# QuDAC_V3.net
KiCad netlist of a schematic drawn in EAGLE
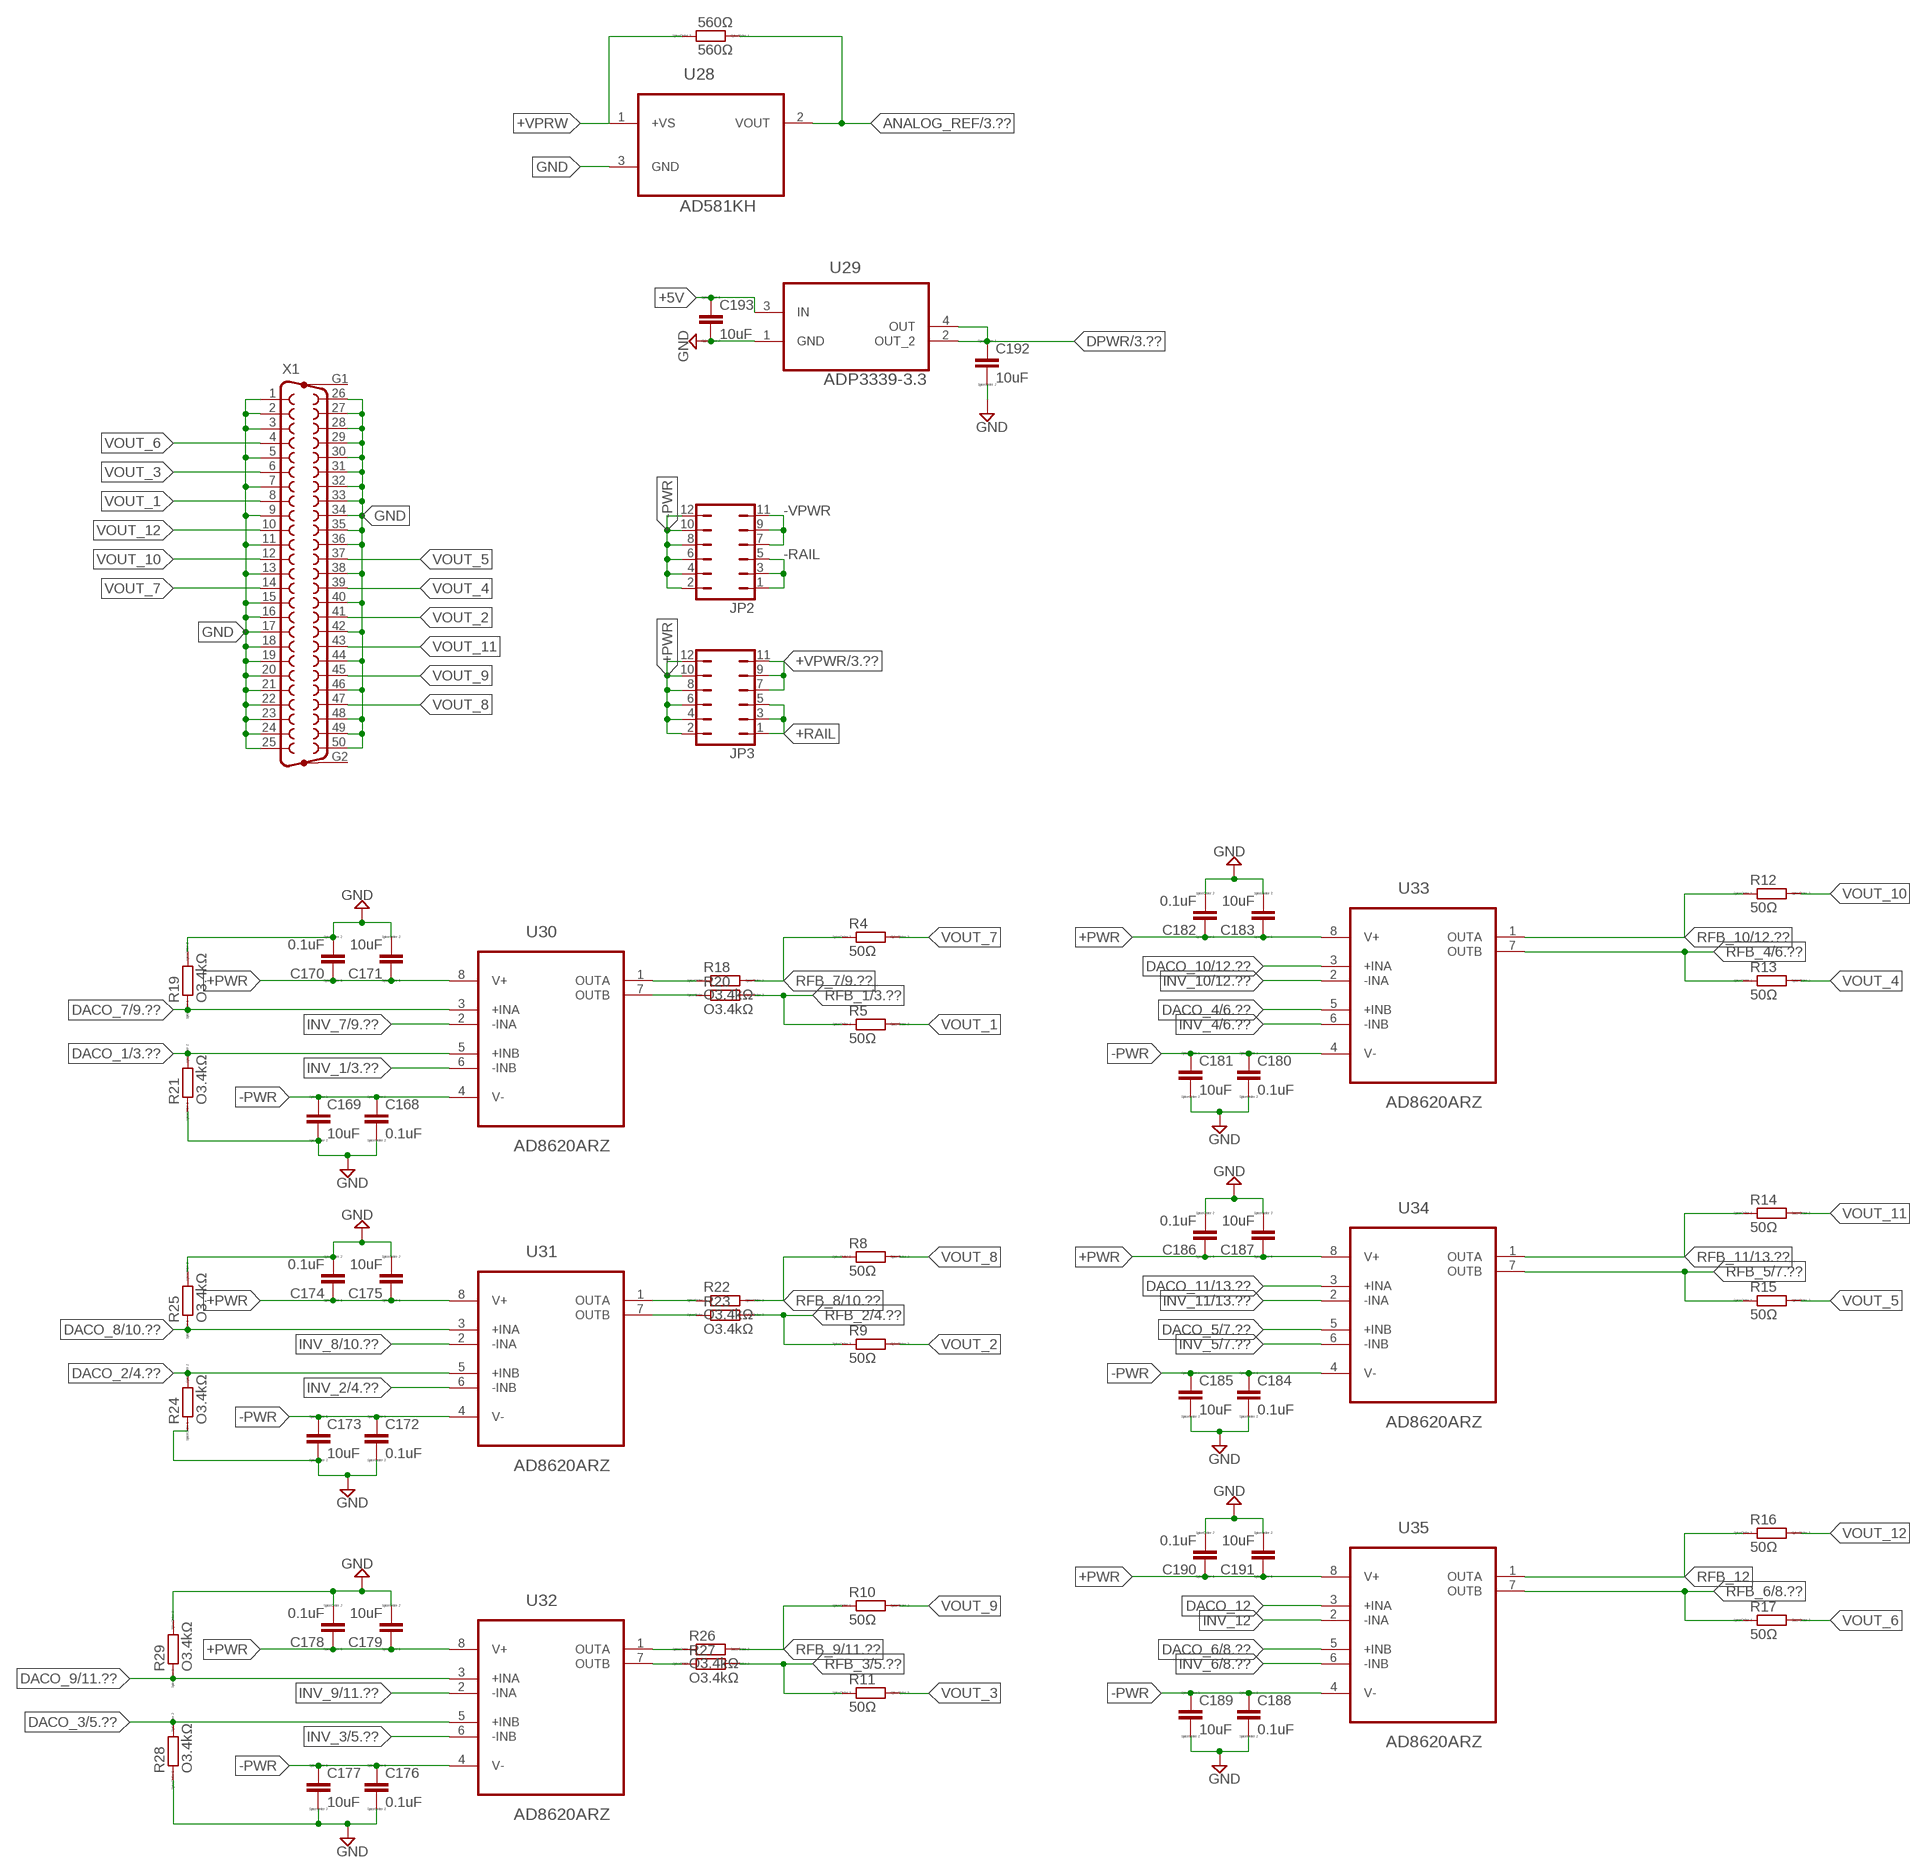
[diagram p0: schematic, sheet 1]
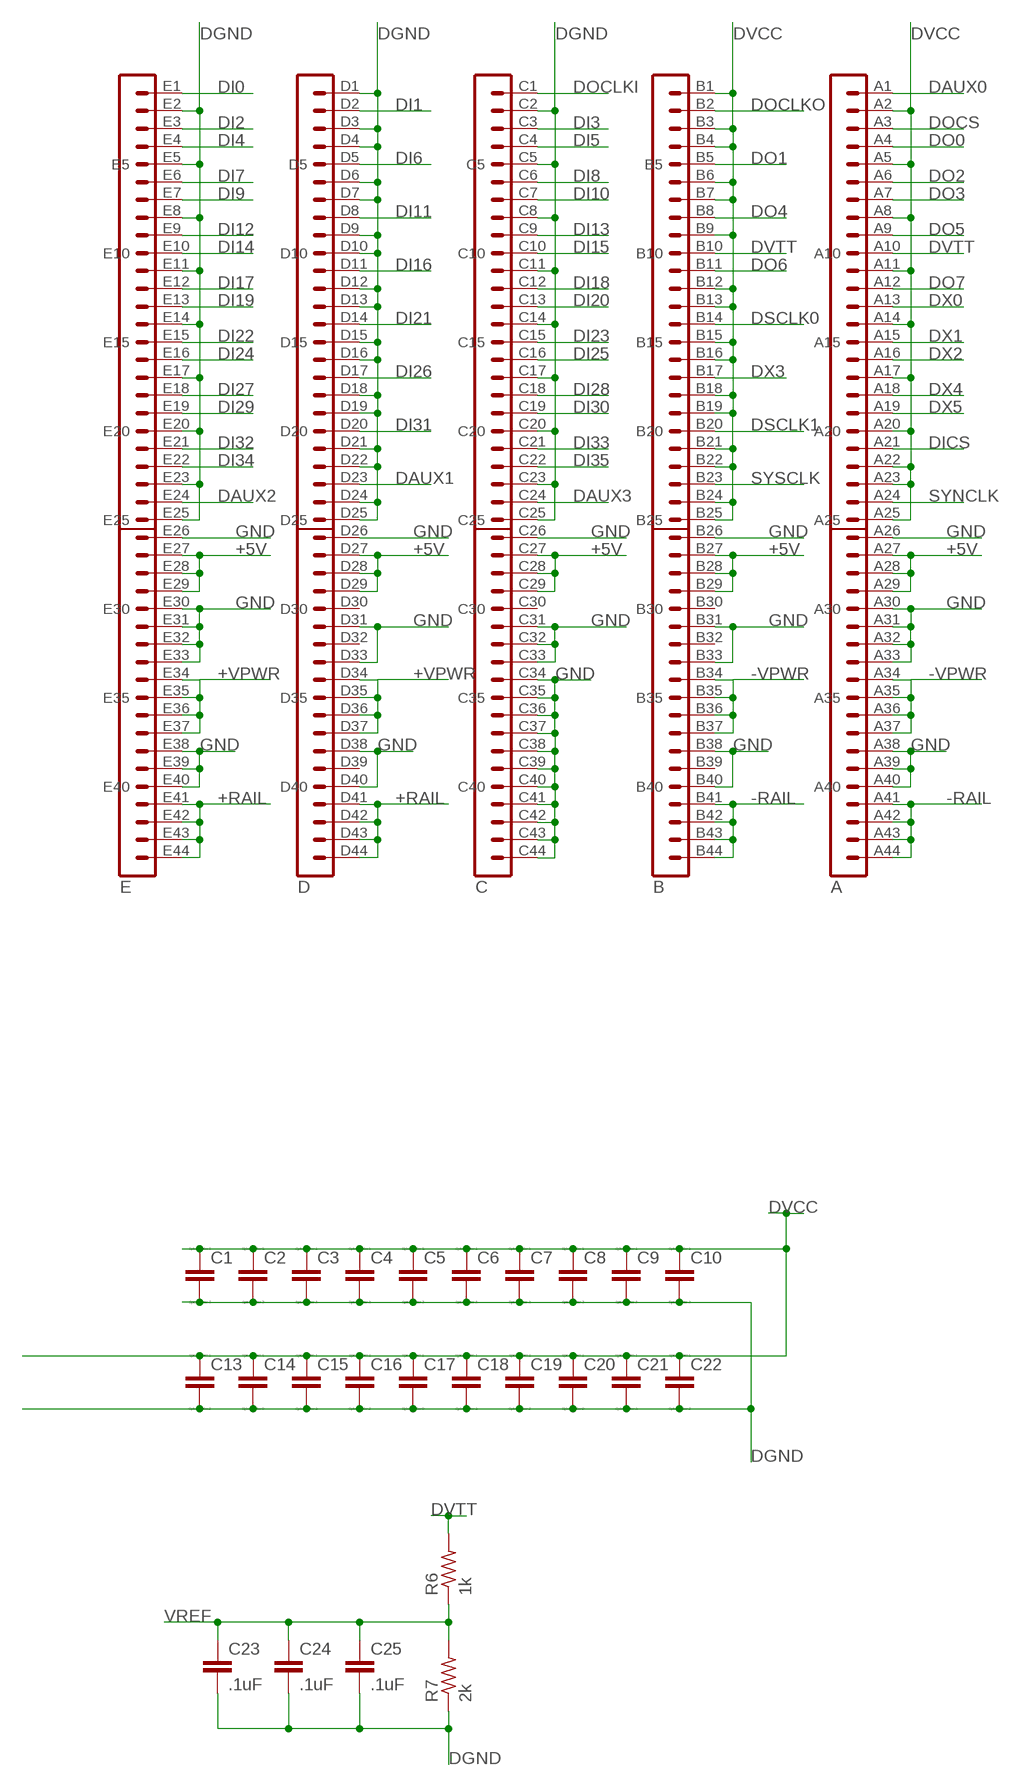
[diagram p1: schematic, sheet 2, part 1 of 2]
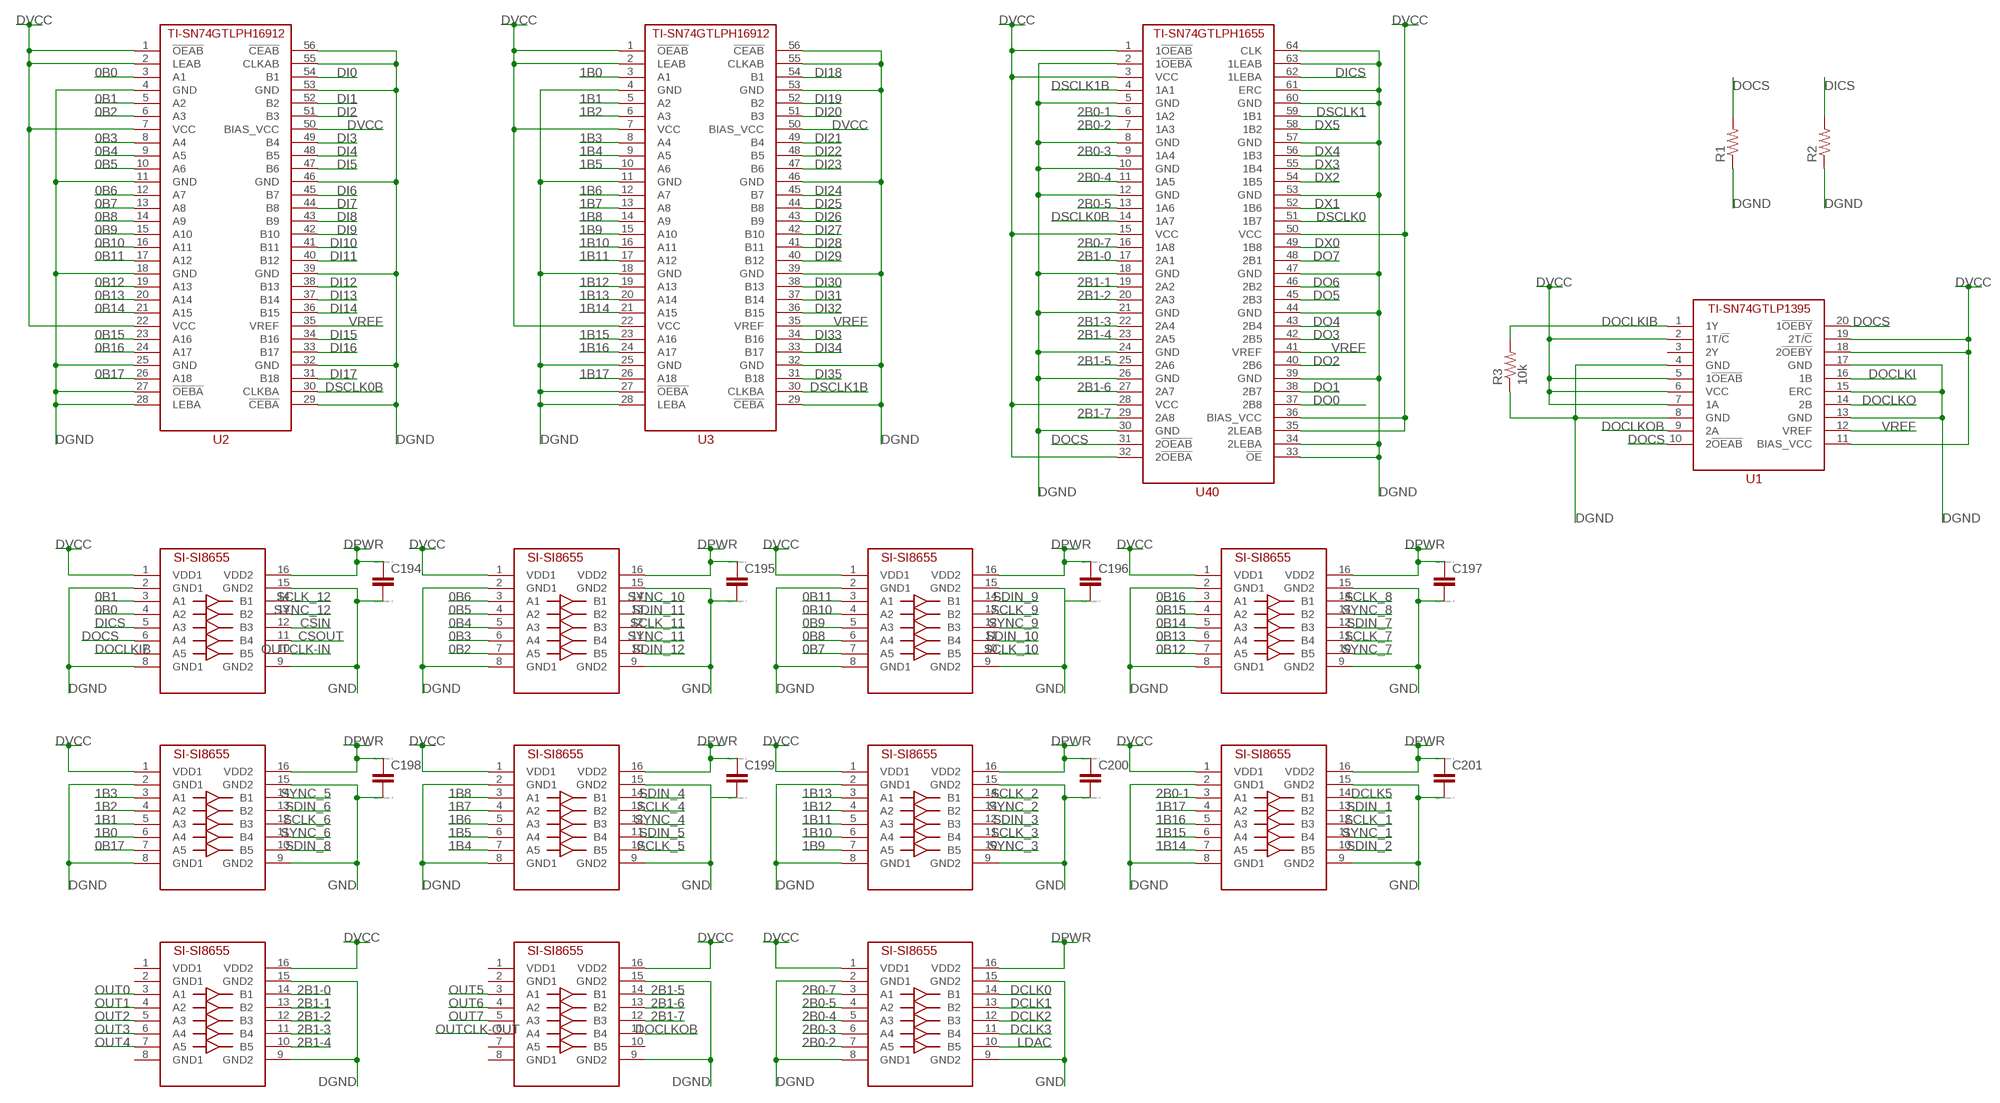
[diagram p2: schematic, sheet 2, part 2 of 2]
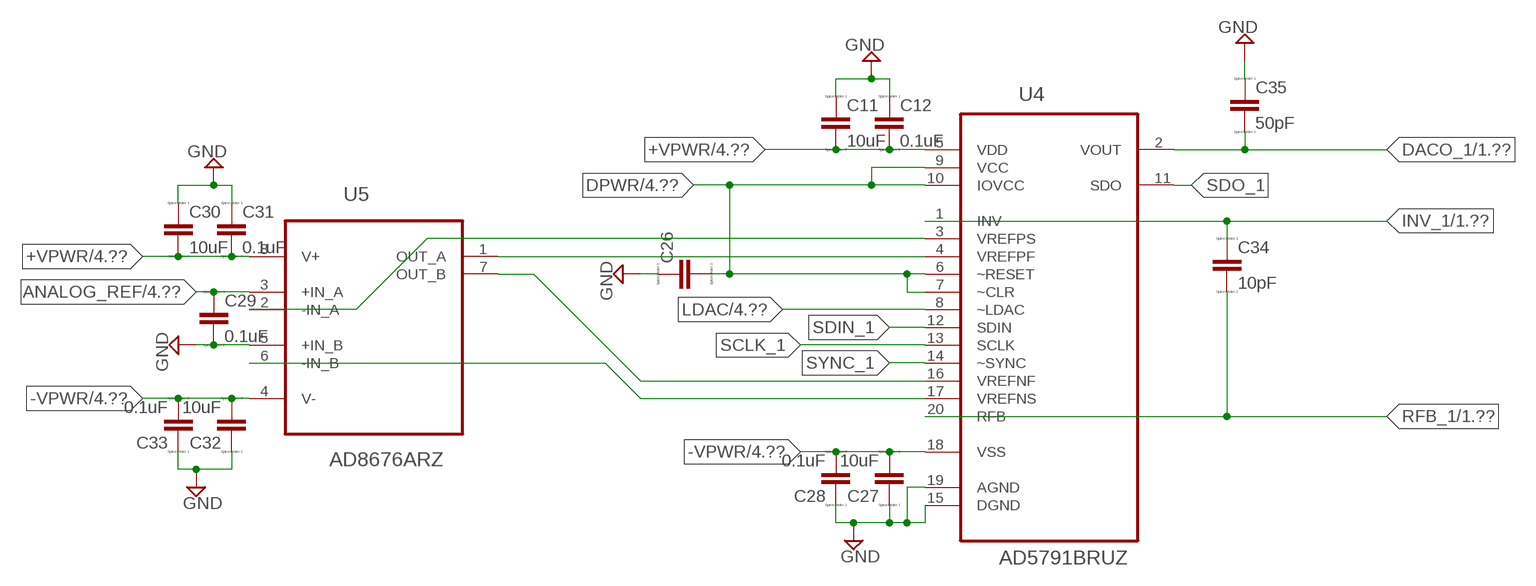
[diagram p3: schematic, sheet 3]
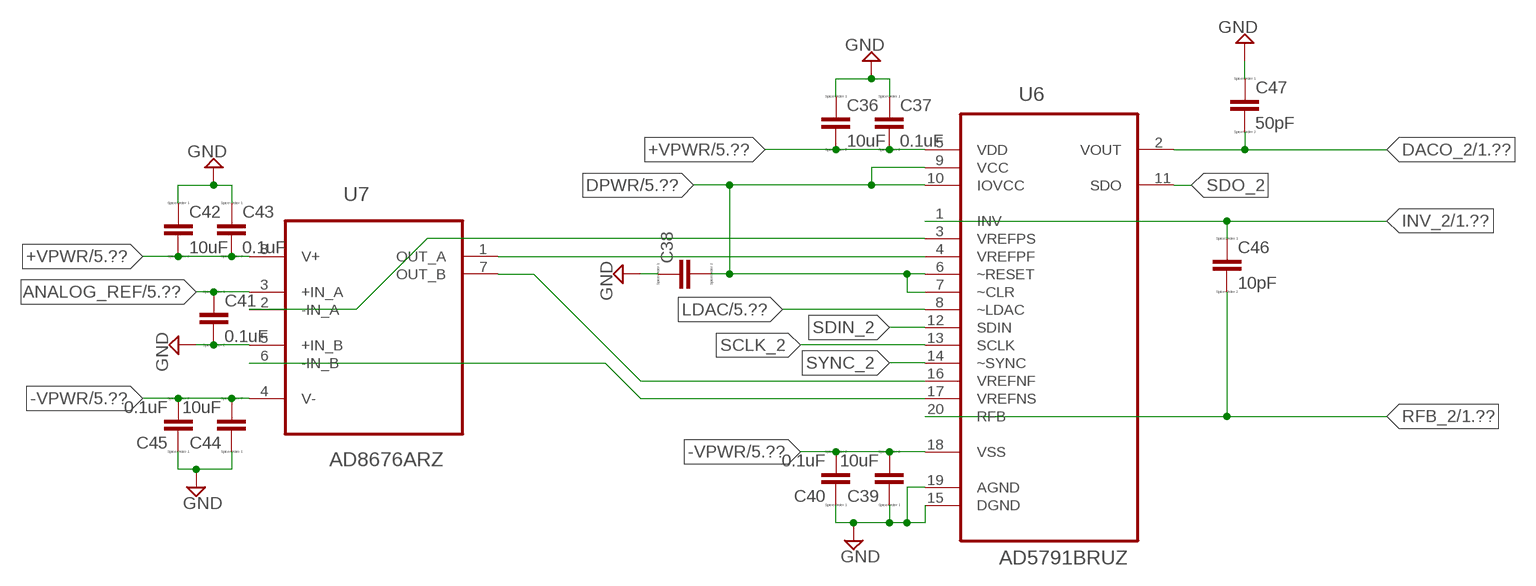
[diagram p4: schematic, sheet 4]
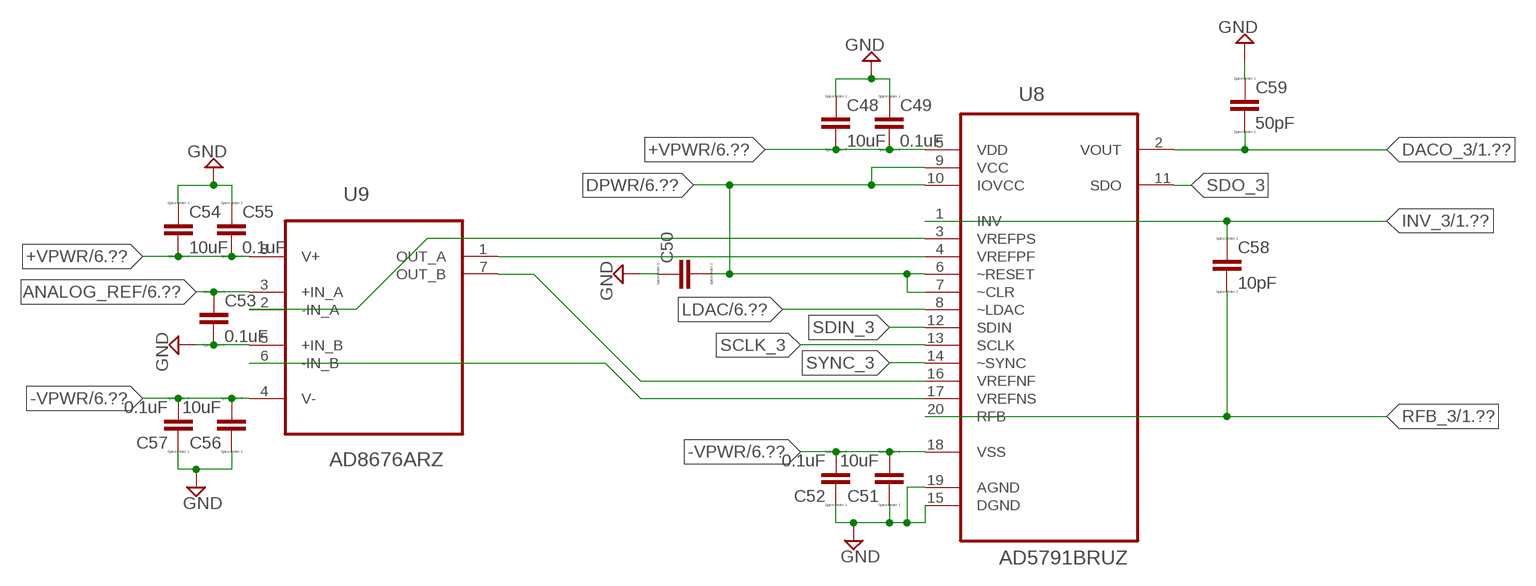
[diagram p5: schematic, sheet 5]
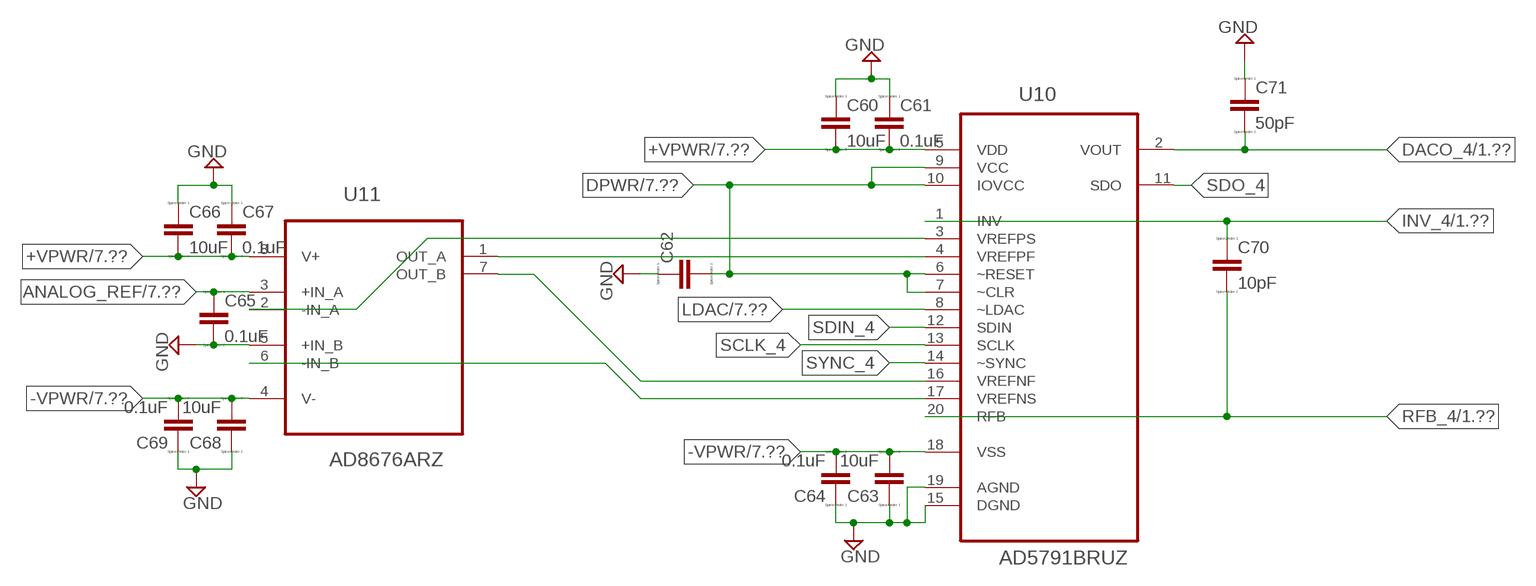
[diagram p6: schematic, sheet 6]
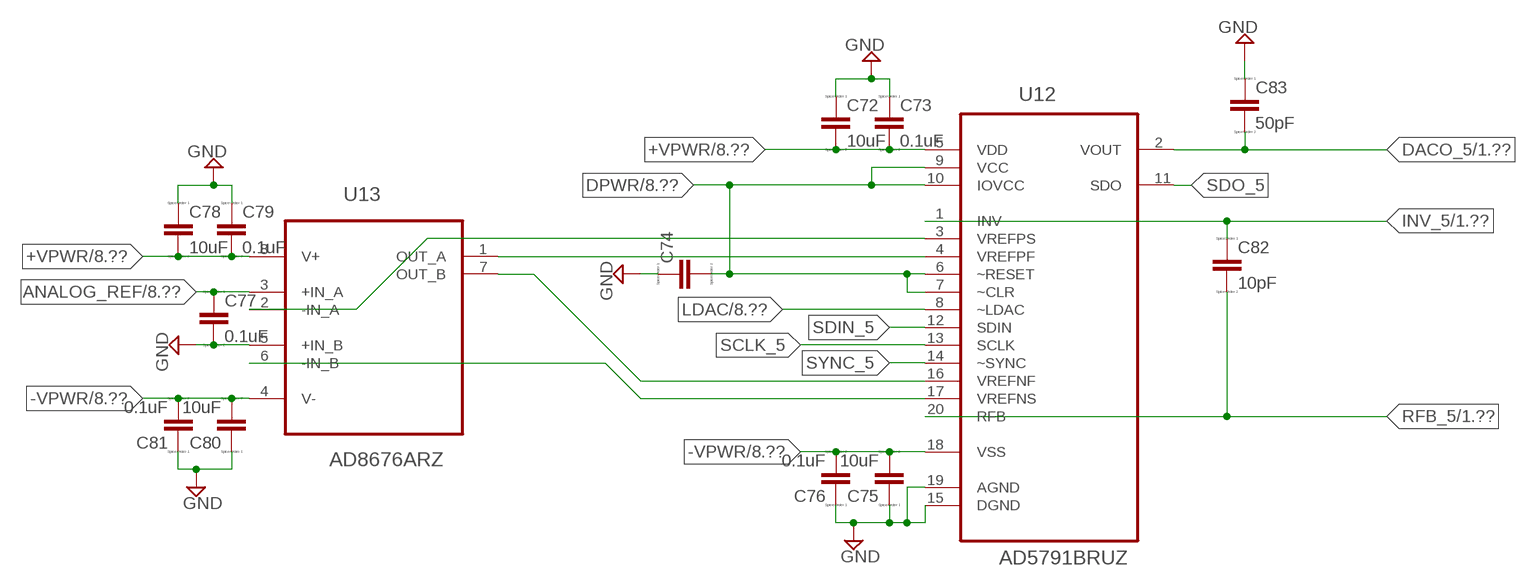
[diagram p7: schematic, sheet 7]
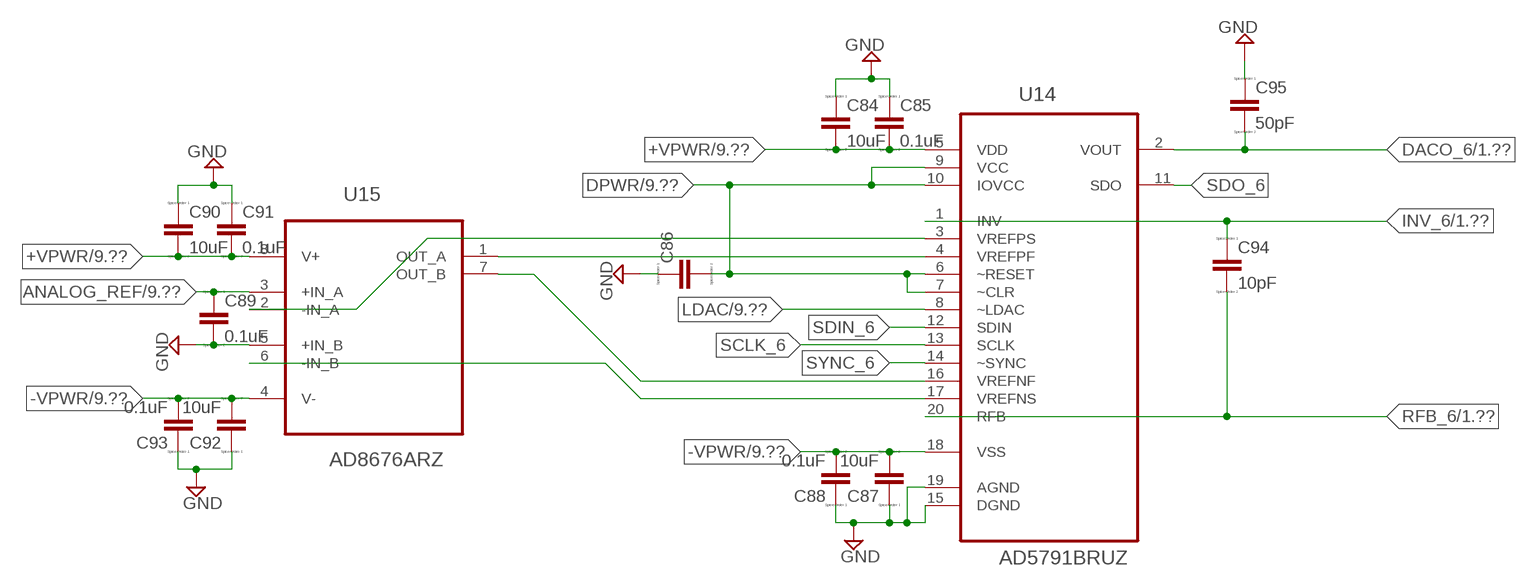
[diagram p8: schematic, sheet 8]
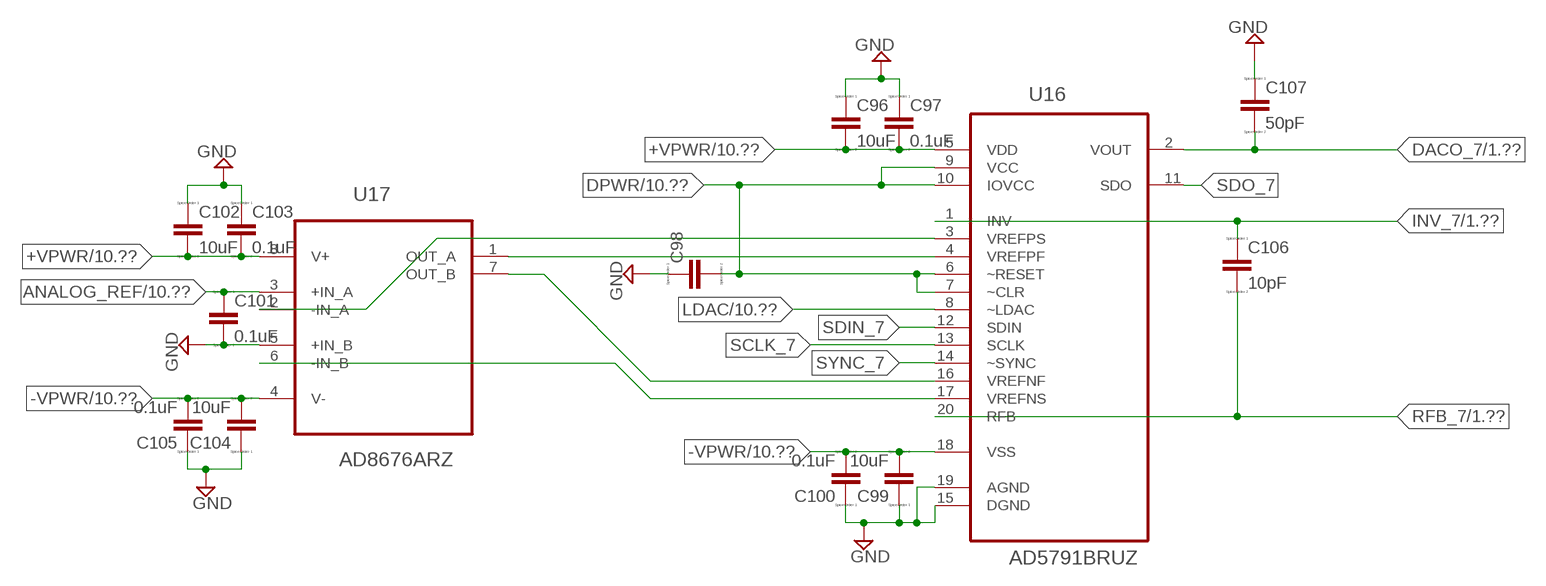
[diagram p9: schematic, sheet 9]
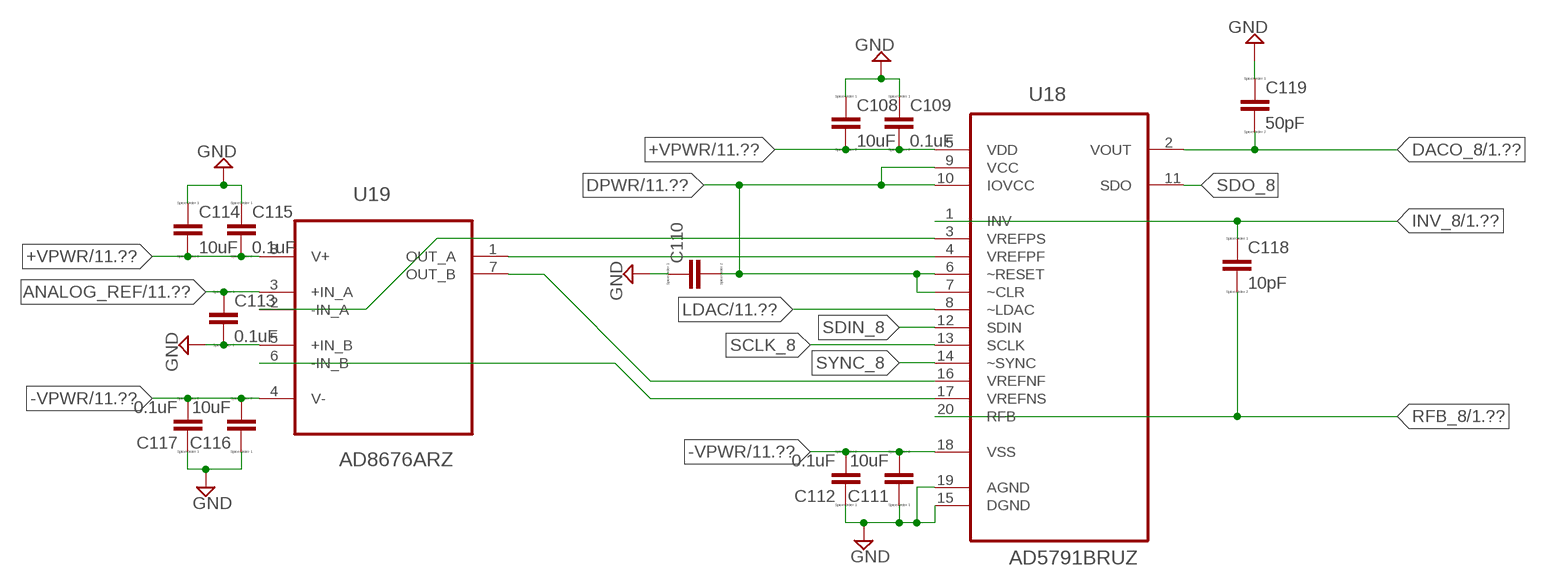
[diagram p10: schematic, sheet 10]
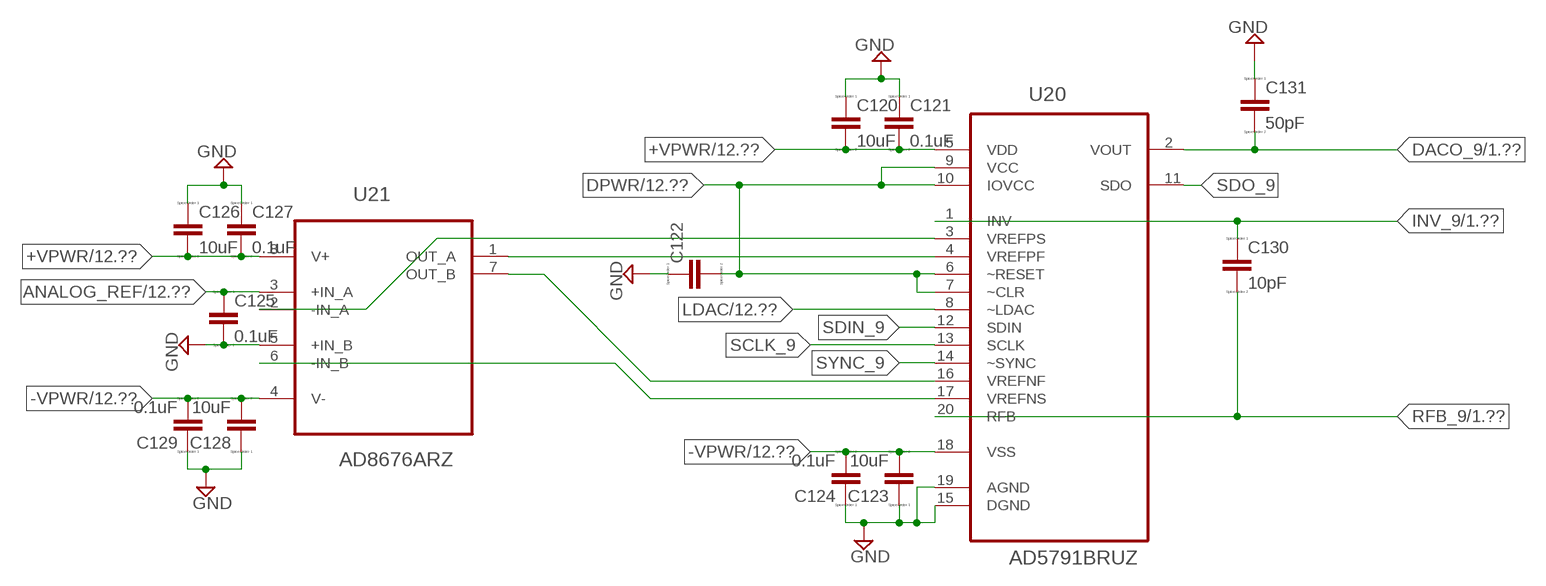
[diagram p11: schematic, sheet 11]
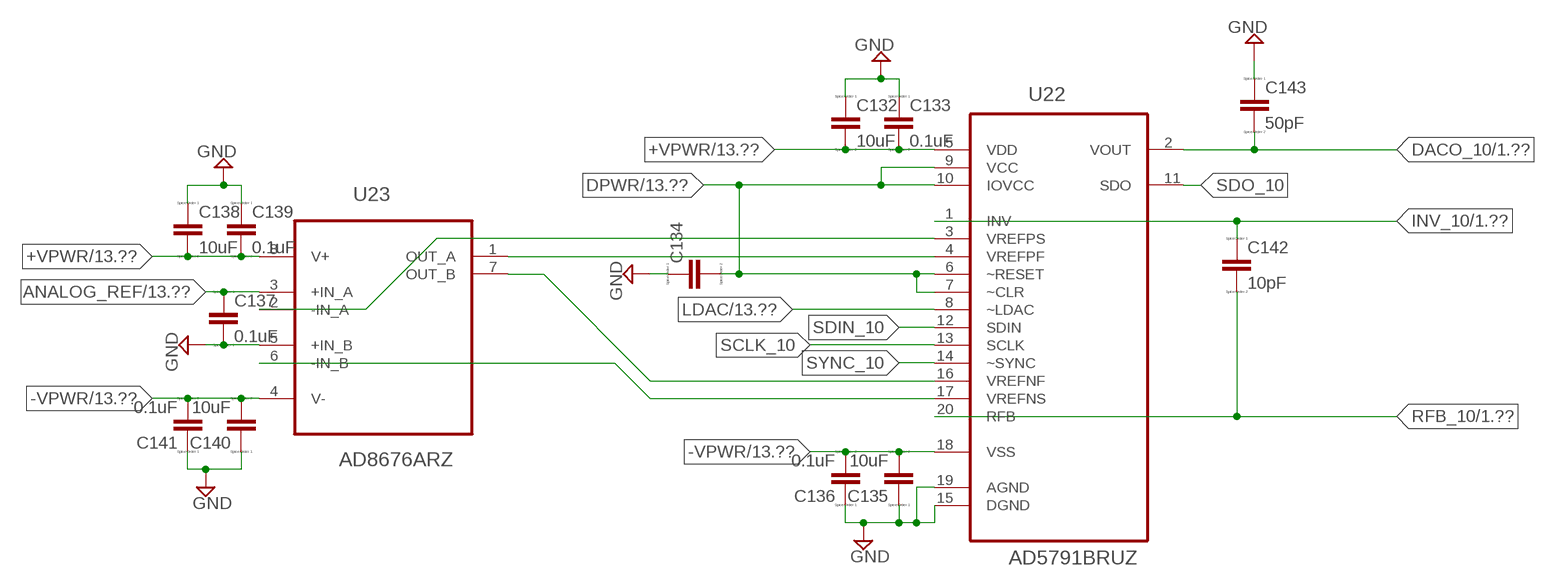
[diagram p12: schematic, sheet 12]
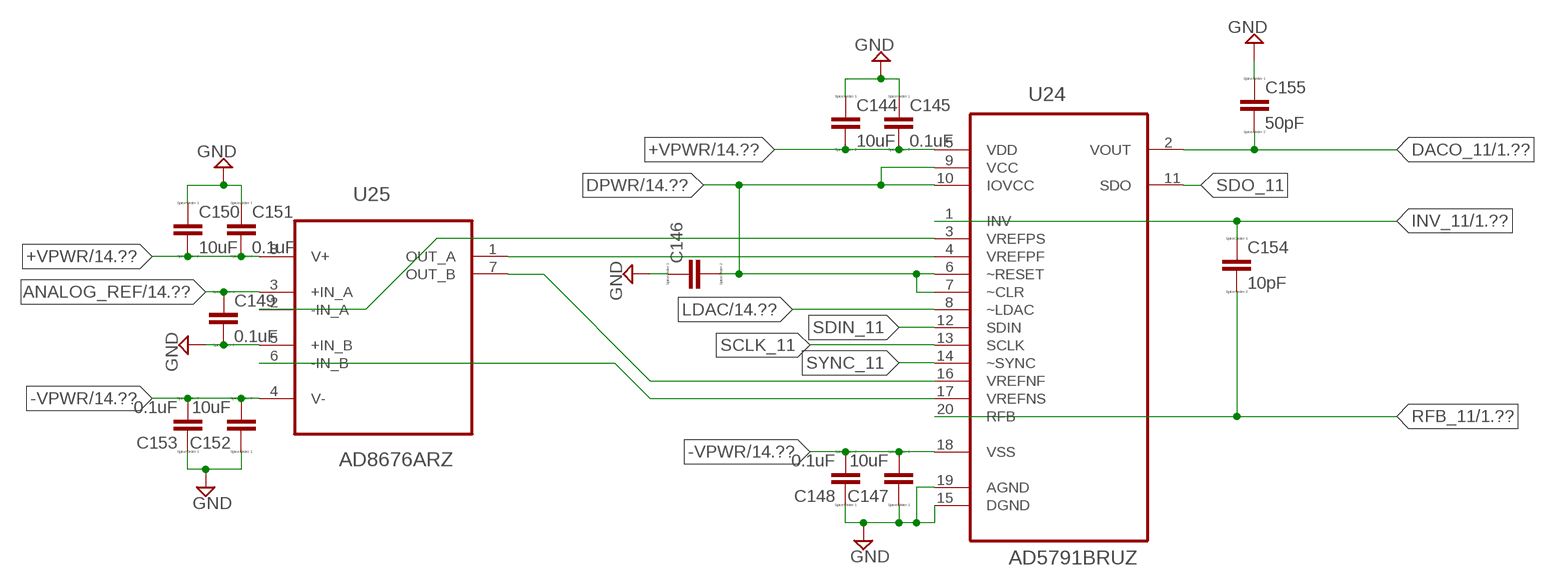
[diagram p13: schematic, sheet 13]
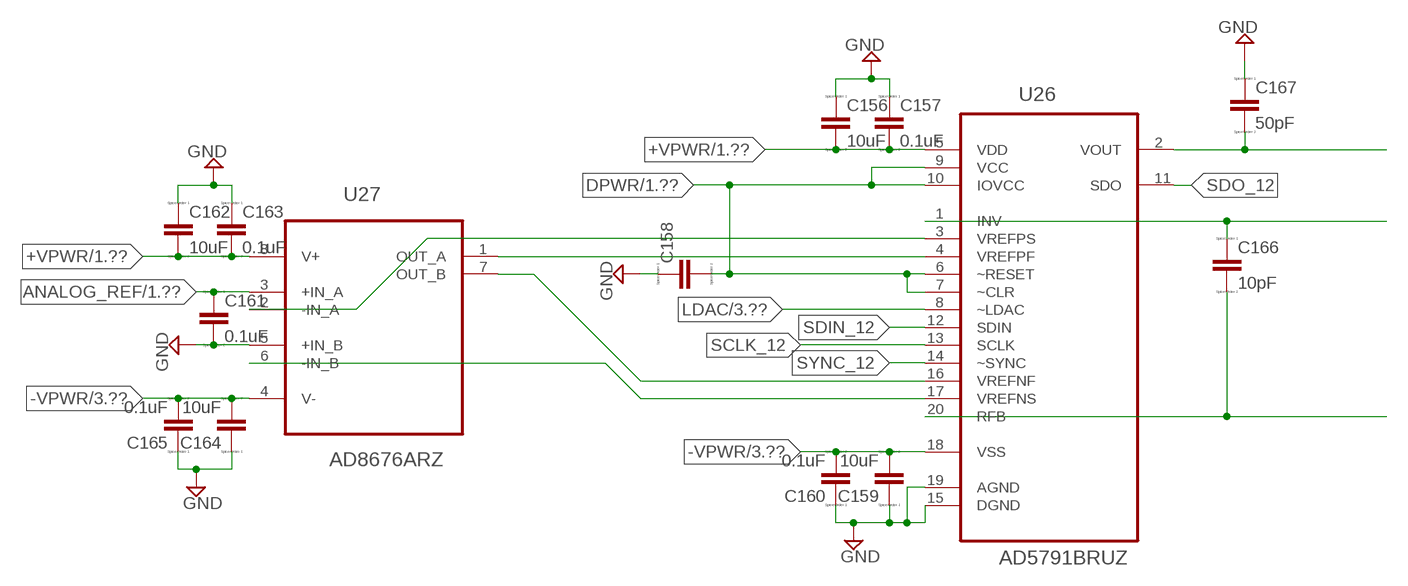
[diagram p14: schematic, sheet 14]

(export (version "E")
  (design (tool "Eeschema 10.0.6"))
  (components
    (comp (ref "560Ω")
      (value "560Ω")
      (footprint "eagle-import:R0603")
      (libsource (lib "eagle-import") (part "RR0603"))
    )
    (comp (ref "C168")
      (value "0.1uF")
      (footprint "eagle-import:C0603")
      (libsource (lib "eagle-import") (part "CC0603"))
    )
    (comp (ref "C169")
      (value "10uF")
      (footprint "eagle-import:C0805")
      (libsource (lib "eagle-import") (part "C"))
    )
    (comp (ref "C170")
      (value "0.1uF")
      (footprint "eagle-import:C0603")
      (libsource (lib "eagle-import") (part "CC0603"))
    )
    (comp (ref "C171")
      (value "10uF")
      (footprint "eagle-import:C0805")
      (libsource (lib "eagle-import") (part "C"))
    )
    (comp (ref "C172")
      (value "0.1uF")
      (footprint "eagle-import:C0603")
      (libsource (lib "eagle-import") (part "CC0603"))
    )
    (comp (ref "C173")
      (value "10uF")
      (footprint "eagle-import:C0805")
      (libsource (lib "eagle-import") (part "C"))
    )
    (comp (ref "C174")
      (value "0.1uF")
      (footprint "eagle-import:C0603")
      (libsource (lib "eagle-import") (part "CC0603"))
    )
    (comp (ref "C175")
      (value "10uF")
      (footprint "eagle-import:C0805")
      (libsource (lib "eagle-import") (part "C"))
    )
    (comp (ref "C176")
      (value "0.1uF")
      (footprint "eagle-import:C0603")
      (libsource (lib "eagle-import") (part "CC0603"))
    )
    (comp (ref "C177")
      (value "10uF")
      (footprint "eagle-import:C0805")
      (libsource (lib "eagle-import") (part "C"))
    )
    (comp (ref "C178")
      (value "0.1uF")
      (footprint "eagle-import:C0603")
      (libsource (lib "eagle-import") (part "CC0603"))
    )
    (comp (ref "C179")
      (value "10uF")
      (footprint "eagle-import:C0805")
      (libsource (lib "eagle-import") (part "C"))
    )
    (comp (ref "C180")
      (value "0.1uF")
      (footprint "eagle-import:C0603")
      (libsource (lib "eagle-import") (part "CC0603"))
    )
    (comp (ref "C181")
      (value "10uF")
      (footprint "eagle-import:C0805")
      (libsource (lib "eagle-import") (part "C"))
    )
    (comp (ref "C182")
      (value "0.1uF")
      (footprint "eagle-import:C0603")
      (libsource (lib "eagle-import") (part "CC0603"))
    )
    (comp (ref "C183")
      (value "10uF")
      (footprint "eagle-import:C0805")
      (libsource (lib "eagle-import") (part "C"))
    )
    (comp (ref "C184")
      (value "0.1uF")
      (footprint "eagle-import:C0603")
      (libsource (lib "eagle-import") (part "CC0603"))
    )
    (comp (ref "C185")
      (value "10uF")
      (footprint "eagle-import:C0805")
      (libsource (lib "eagle-import") (part "C"))
    )
    (comp (ref "C186")
      (value "0.1uF")
      (footprint "eagle-import:C0603")
      (libsource (lib "eagle-import") (part "CC0603"))
    )
    (comp (ref "C187")
      (value "10uF")
      (footprint "eagle-import:C0805")
      (libsource (lib "eagle-import") (part "C"))
    )
    (comp (ref "C188")
      (value "0.1uF")
      (footprint "eagle-import:C0603")
      (libsource (lib "eagle-import") (part "CC0603"))
    )
    (comp (ref "C189")
      (value "10uF")
      (footprint "eagle-import:C0805")
      (libsource (lib "eagle-import") (part "C"))
    )
    (comp (ref "C190")
      (value "0.1uF")
      (footprint "eagle-import:C0603")
      (libsource (lib "eagle-import") (part "CC0603"))
    )
    (comp (ref "C191")
      (value "10uF")
      (footprint "eagle-import:C0805")
      (libsource (lib "eagle-import") (part "C"))
    )
    (comp (ref "C192")
      (value "10uF")
      (footprint "eagle-import:C0805")
      (libsource (lib "eagle-import") (part "C"))
    )
    (comp (ref "C193")
      (value "10uF")
      (footprint "eagle-import:C0805")
      (libsource (lib "eagle-import") (part "C"))
    )
    (comp (ref "JP2")
      (value "JP6Q")
      (footprint "eagle-import:JP6Q")
      (libsource (lib "eagle-import") (part "JP6Q"))
    )
    (comp (ref "JP3")
      (value "JP6Q")
      (footprint "eagle-import:JP6Q")
      (libsource (lib "eagle-import") (part "JP6Q"))
    )
    (comp (ref "R4")
      (value "50Ω")
      (footprint "eagle-import:R0603")
      (libsource (lib "eagle-import") (part "RR0603"))
    )
    (comp (ref "R5")
      (value "50Ω")
      (footprint "eagle-import:R0603")
      (libsource (lib "eagle-import") (part "RR0603"))
    )
    (comp (ref "R8")
      (value "50Ω")
      (footprint "eagle-import:R0603")
      (libsource (lib "eagle-import") (part "RR0603"))
    )
    (comp (ref "R9")
      (value "50Ω")
      (footprint "eagle-import:R0603")
      (libsource (lib "eagle-import") (part "RR0603"))
    )
    (comp (ref "R10")
      (value "50Ω")
      (footprint "eagle-import:R0603")
      (libsource (lib "eagle-import") (part "RR0603"))
    )
    (comp (ref "R11")
      (value "50Ω")
      (footprint "eagle-import:R0603")
      (libsource (lib "eagle-import") (part "RR0603"))
    )
    (comp (ref "R12")
      (value "50Ω")
      (footprint "eagle-import:R0603")
      (libsource (lib "eagle-import") (part "RR0603"))
    )
    (comp (ref "R13")
      (value "50Ω")
      (footprint "eagle-import:R0603")
      (libsource (lib "eagle-import") (part "RR0603"))
    )
    (comp (ref "R14")
      (value "50Ω")
      (footprint "eagle-import:R0603")
      (libsource (lib "eagle-import") (part "RR0603"))
    )
    (comp (ref "R15")
      (value "50Ω")
      (footprint "eagle-import:R0603")
      (libsource (lib "eagle-import") (part "RR0603"))
    )
    (comp (ref "R16")
      (value "50Ω")
      (footprint "eagle-import:R0603")
      (libsource (lib "eagle-import") (part "RR0603"))
    )
    (comp (ref "R17")
      (value "50Ω")
      (footprint "eagle-import:R0603")
      (libsource (lib "eagle-import") (part "RR0603"))
    )
    (comp (ref "R18")
      (value "O3.4kΩ")
      (footprint "eagle-import:R0603")
      (libsource (lib "eagle-import") (part "RR0603"))
    )
    (comp (ref "R19")
      (value "O3.4kΩ")
      (footprint "eagle-import:R0603")
      (libsource (lib "eagle-import") (part "RR0603"))
    )
    (comp (ref "R20")
      (value "O3.4kΩ")
      (footprint "eagle-import:R0603")
      (libsource (lib "eagle-import") (part "RR0603"))
    )
    (comp (ref "R21")
      (value "O3.4kΩ")
      (footprint "eagle-import:R0603")
      (libsource (lib "eagle-import") (part "RR0603"))
    )
    (comp (ref "R22")
      (value "O3.4kΩ")
      (footprint "eagle-import:R0603")
      (libsource (lib "eagle-import") (part "RR0603"))
    )
    (comp (ref "R23")
      (value "O3.4kΩ")
      (footprint "eagle-import:R0603")
      (libsource (lib "eagle-import") (part "RR0603"))
    )
    (comp (ref "R24")
      (value "O3.4kΩ")
      (footprint "eagle-import:R0603")
      (libsource (lib "eagle-import") (part "RR0603"))
    )
    (comp (ref "R25")
      (value "O3.4kΩ")
      (footprint "eagle-import:R0603")
      (libsource (lib "eagle-import") (part "RR0603"))
    )
    (comp (ref "R26")
      (value "O3.4kΩ")
      (footprint "eagle-import:R0603")
      (libsource (lib "eagle-import") (part "RR0603"))
    )
    (comp (ref "R27")
      (value "O3.4kΩ")
      (footprint "eagle-import:R0603")
      (libsource (lib "eagle-import") (part "RR0603"))
    )
    (comp (ref "R28")
      (value "O3.4kΩ")
      (footprint "eagle-import:R0603")
      (libsource (lib "eagle-import") (part "RR0603"))
    )
    (comp (ref "R29")
      (value "O3.4kΩ")
      (footprint "eagle-import:R0603")
      (libsource (lib "eagle-import") (part "RR0603"))
    )
    (comp (ref "U28")
      (value "AD581KH")
      (footprint "eagle-import:TO254P939X470-3P")
      (libsource (lib "eagle-import") (part "AD581KH"))
    )
    (comp (ref "U29")
      (value "ADP3339-3.3")
      (footprint "eagle-import:SOT230P700X180-4N")
      (fields (field (name "MPN") "ADP3339AKCZ-3.3-R7"))
      (libsource (lib "eagle-import") (part "ADP3339AKCZ-3.3-R7"))
    )
    (comp (ref "U30")
      (value "AD8620ARZ")
      (footprint "eagle-import:SOIC127P600X175-8N")
      (libsource (lib "eagle-import") (part "AD8620ARZ"))
    )
    (comp (ref "U31")
      (value "AD8620ARZ")
      (footprint "eagle-import:SOIC127P600X175-8N")
      (libsource (lib "eagle-import") (part "AD8620ARZ"))
    )
    (comp (ref "U32")
      (value "AD8620ARZ")
      (footprint "eagle-import:SOIC127P600X175-8N")
      (libsource (lib "eagle-import") (part "AD8620ARZ"))
    )
    (comp (ref "U33")
      (value "AD8620ARZ")
      (footprint "eagle-import:SOIC127P600X175-8N")
      (libsource (lib "eagle-import") (part "AD8620ARZ"))
    )
    (comp (ref "U34")
      (value "AD8620ARZ")
      (footprint "eagle-import:SOIC127P600X175-8N")
      (libsource (lib "eagle-import") (part "AD8620ARZ"))
    )
    (comp (ref "U35")
      (value "AD8620ARZ")
      (footprint "eagle-import:SOIC127P600X175-8N")
      (libsource (lib "eagle-import") (part "AD8620ARZ"))
    )
    (comp (ref "X1")
      (value "F50HP")
      (footprint "eagle-import:F50HP")
      (libsource (lib "eagle-import") (part "F50HP"))
    )
    (comp (ref "C96")
      (value "10uF")
      (footprint "eagle-import:C0805")
      (libsource (lib "eagle-import") (part "C"))
    )
    (comp (ref "C97")
      (value "0.1uF")
      (footprint "eagle-import:C0603")
      (libsource (lib "eagle-import") (part "CC0603"))
    )
    (comp (ref "C98")
      (value "CC0603")
      (footprint "eagle-import:C0603")
      (libsource (lib "eagle-import") (part "CC0603"))
    )
    (comp (ref "C99")
      (value "10uF")
      (footprint "eagle-import:C0805")
      (libsource (lib "eagle-import") (part "C"))
    )
    (comp (ref "C100")
      (value "0.1uF")
      (footprint "eagle-import:C0603")
      (libsource (lib "eagle-import") (part "CC0603"))
    )
    (comp (ref "C101")
      (value "0.1uF")
      (footprint "eagle-import:C0603")
      (libsource (lib "eagle-import") (part "CC0603"))
    )
    (comp (ref "C102")
      (value "10uF")
      (footprint "eagle-import:C0805")
      (libsource (lib "eagle-import") (part "C"))
    )
    (comp (ref "C103")
      (value "0.1uF")
      (footprint "eagle-import:C0603")
      (libsource (lib "eagle-import") (part "CC0603"))
    )
    (comp (ref "C104")
      (value "10uF")
      (footprint "eagle-import:C0805")
      (libsource (lib "eagle-import") (part "C"))
    )
    (comp (ref "C105")
      (value "0.1uF")
      (footprint "eagle-import:C0603")
      (libsource (lib "eagle-import") (part "CC0603"))
    )
    (comp (ref "C106")
      (value "10pF")
      (footprint "eagle-import:C0603")
      (libsource (lib "eagle-import") (part "CC0603"))
    )
    (comp (ref "C107")
      (value "50pF")
      (footprint "eagle-import:C0603")
      (libsource (lib "eagle-import") (part "CC0603"))
    )
    (comp (ref "U16")
      (value "AD5791BRUZ")
      (footprint "eagle-import:SOP65P640X120-20N")
      (libsource (lib "eagle-import") (part "AD5791BRUZ"))
    )
    (comp (ref "U17")
      (value "AD8676ARZ")
      (footprint "eagle-import:SOIC127P600X175-8N")
      (libsource (lib "eagle-import") (part "AD8676ARZ"))
    )
    (comp (ref "C60")
      (value "10uF")
      (footprint "eagle-import:C0805")
      (libsource (lib "eagle-import") (part "C"))
    )
    (comp (ref "C61")
      (value "0.1uF")
      (footprint "eagle-import:C0603")
      (libsource (lib "eagle-import") (part "CC0603"))
    )
    (comp (ref "C62")
      (value "CC0603")
      (footprint "eagle-import:C0603")
      (libsource (lib "eagle-import") (part "CC0603"))
    )
    (comp (ref "C63")
      (value "10uF")
      (footprint "eagle-import:C0805")
      (libsource (lib "eagle-import") (part "C"))
    )
    (comp (ref "C64")
      (value "0.1uF")
      (footprint "eagle-import:C0603")
      (libsource (lib "eagle-import") (part "CC0603"))
    )
    (comp (ref "C65")
      (value "0.1uF")
      (footprint "eagle-import:C0603")
      (libsource (lib "eagle-import") (part "CC0603"))
    )
    (comp (ref "C66")
      (value "10uF")
      (footprint "eagle-import:C0805")
      (libsource (lib "eagle-import") (part "C"))
    )
    (comp (ref "C67")
      (value "0.1uF")
      (footprint "eagle-import:C0603")
      (libsource (lib "eagle-import") (part "CC0603"))
    )
    (comp (ref "C68")
      (value "10uF")
      (footprint "eagle-import:C0805")
      (libsource (lib "eagle-import") (part "C"))
    )
    (comp (ref "C69")
      (value "0.1uF")
      (footprint "eagle-import:C0603")
      (libsource (lib "eagle-import") (part "CC0603"))
    )
    (comp (ref "C70")
      (value "10pF")
      (footprint "eagle-import:C0603")
      (libsource (lib "eagle-import") (part "CC0603"))
    )
    (comp (ref "C71")
      (value "50pF")
      (footprint "eagle-import:C0603")
      (libsource (lib "eagle-import") (part "CC0603"))
    )
    (comp (ref "U10")
      (value "AD5791BRUZ")
      (footprint "eagle-import:SOP65P640X120-20N")
      (libsource (lib "eagle-import") (part "AD5791BRUZ"))
    )
    (comp (ref "U11")
      (value "AD8676ARZ")
      (footprint "eagle-import:SOIC127P600X175-8N")
      (libsource (lib "eagle-import") (part "AD8676ARZ"))
    )
    (comp (ref "C11")
      (value "10uF")
      (footprint "eagle-import:C0805")
      (libsource (lib "eagle-import") (part "C"))
    )
    (comp (ref "C12")
      (value "0.1uF")
      (footprint "eagle-import:C0603")
      (libsource (lib "eagle-import") (part "CC0603"))
    )
    (comp (ref "C26")
      (value "CC0603")
      (footprint "eagle-import:C0603")
      (libsource (lib "eagle-import") (part "CC0603"))
    )
    (comp (ref "C27")
      (value "10uF")
      (footprint "eagle-import:C0805")
      (libsource (lib "eagle-import") (part "C"))
    )
    (comp (ref "C28")
      (value "0.1uF")
      (footprint "eagle-import:C0603")
      (libsource (lib "eagle-import") (part "CC0603"))
    )
    (comp (ref "C29")
      (value "0.1uF")
      (footprint "eagle-import:C0603")
      (libsource (lib "eagle-import") (part "CC0603"))
    )
    (comp (ref "C30")
      (value "10uF")
      (footprint "eagle-import:C0805")
      (libsource (lib "eagle-import") (part "C"))
    )
    (comp (ref "C31")
      (value "0.1uF")
      (footprint "eagle-import:C0603")
      (libsource (lib "eagle-import") (part "CC0603"))
    )
    (comp (ref "C32")
      (value "10uF")
      (footprint "eagle-import:C0805")
      (libsource (lib "eagle-import") (part "C"))
    )
    (comp (ref "C33")
      (value "0.1uF")
      (footprint "eagle-import:C0603")
      (libsource (lib "eagle-import") (part "CC0603"))
    )
    (comp (ref "C34")
      (value "10pF")
      (footprint "eagle-import:C0603")
      (libsource (lib "eagle-import") (part "CC0603"))
    )
    (comp (ref "C35")
      (value "50pF")
      (footprint "eagle-import:C0603")
      (libsource (lib "eagle-import") (part "CC0603"))
    )
    (comp (ref "U4")
      (value "AD5791BRUZ")
      (footprint "eagle-import:SOP65P640X120-20N")
      (libsource (lib "eagle-import") (part "AD5791BRUZ"))
    )
    (comp (ref "U5")
      (value "AD8676ARZ")
      (footprint "eagle-import:SOIC127P600X175-8N")
      (libsource (lib "eagle-import") (part "AD8676ARZ"))
    )
    (comp (ref "C108")
      (value "10uF")
      (footprint "eagle-import:C0805")
      (libsource (lib "eagle-import") (part "C"))
    )
    (comp (ref "C109")
      (value "0.1uF")
      (footprint "eagle-import:C0603")
      (libsource (lib "eagle-import") (part "CC0603"))
    )
    (comp (ref "C110")
      (value "CC0603")
      (footprint "eagle-import:C0603")
      (libsource (lib "eagle-import") (part "CC0603"))
    )
    (comp (ref "C111")
      (value "10uF")
      (footprint "eagle-import:C0805")
      (libsource (lib "eagle-import") (part "C"))
    )
    (comp (ref "C112")
      (value "0.1uF")
      (footprint "eagle-import:C0603")
      (libsource (lib "eagle-import") (part "CC0603"))
    )
    (comp (ref "C113")
      (value "0.1uF")
      (footprint "eagle-import:C0603")
      (libsource (lib "eagle-import") (part "CC0603"))
    )
    (comp (ref "C114")
      (value "10uF")
      (footprint "eagle-import:C0805")
      (libsource (lib "eagle-import") (part "C"))
    )
    (comp (ref "C115")
      (value "0.1uF")
      (footprint "eagle-import:C0603")
      (libsource (lib "eagle-import") (part "CC0603"))
    )
    (comp (ref "C116")
      (value "10uF")
      (footprint "eagle-import:C0805")
      (libsource (lib "eagle-import") (part "C"))
    )
    (comp (ref "C117")
      (value "0.1uF")
      (footprint "eagle-import:C0603")
      (libsource (lib "eagle-import") (part "CC0603"))
    )
    (comp (ref "C118")
      (value "10pF")
      (footprint "eagle-import:C0603")
      (libsource (lib "eagle-import") (part "CC0603"))
    )
    (comp (ref "C119")
      (value "50pF")
      (footprint "eagle-import:C0603")
      (libsource (lib "eagle-import") (part "CC0603"))
    )
    (comp (ref "U18")
      (value "AD5791BRUZ")
      (footprint "eagle-import:SOP65P640X120-20N")
      (libsource (lib "eagle-import") (part "AD5791BRUZ"))
    )
    (comp (ref "U19")
      (value "AD8676ARZ")
      (footprint "eagle-import:SOIC127P600X175-8N")
      (libsource (lib "eagle-import") (part "AD8676ARZ"))
    )
    (comp (ref "C72")
      (value "10uF")
      (footprint "eagle-import:C0805")
      (libsource (lib "eagle-import") (part "C"))
    )
    (comp (ref "C73")
      (value "0.1uF")
      (footprint "eagle-import:C0603")
      (libsource (lib "eagle-import") (part "CC0603"))
    )
    (comp (ref "C74")
      (value "CC0603")
      (footprint "eagle-import:C0603")
      (libsource (lib "eagle-import") (part "CC0603"))
    )
    (comp (ref "C75")
      (value "10uF")
      (footprint "eagle-import:C0805")
      (libsource (lib "eagle-import") (part "C"))
    )
    (comp (ref "C76")
      (value "0.1uF")
      (footprint "eagle-import:C0603")
      (libsource (lib "eagle-import") (part "CC0603"))
    )
    (comp (ref "C77")
      (value "0.1uF")
      (footprint "eagle-import:C0603")
      (libsource (lib "eagle-import") (part "CC0603"))
    )
    (comp (ref "C78")
      (value "10uF")
      (footprint "eagle-import:C0805")
      (libsource (lib "eagle-import") (part "C"))
    )
    (comp (ref "C79")
      (value "0.1uF")
      (footprint "eagle-import:C0603")
      (libsource (lib "eagle-import") (part "CC0603"))
    )
    (comp (ref "C80")
      (value "10uF")
      (footprint "eagle-import:C0805")
      (libsource (lib "eagle-import") (part "C"))
    )
    (comp (ref "C81")
      (value "0.1uF")
      (footprint "eagle-import:C0603")
      (libsource (lib "eagle-import") (part "CC0603"))
    )
    (comp (ref "C82")
      (value "10pF")
      (footprint "eagle-import:C0603")
      (libsource (lib "eagle-import") (part "CC0603"))
    )
    (comp (ref "C83")
      (value "50pF")
      (footprint "eagle-import:C0603")
      (libsource (lib "eagle-import") (part "CC0603"))
    )
    (comp (ref "U12")
      (value "AD5791BRUZ")
      (footprint "eagle-import:SOP65P640X120-20N")
      (libsource (lib "eagle-import") (part "AD5791BRUZ"))
    )
    (comp (ref "U13")
      (value "AD8676ARZ")
      (footprint "eagle-import:SOIC127P600X175-8N")
      (libsource (lib "eagle-import") (part "AD8676ARZ"))
    )
    (comp (ref "C48")
      (value "10uF")
      (footprint "eagle-import:C0805")
      (libsource (lib "eagle-import") (part "C"))
    )
    (comp (ref "C49")
      (value "0.1uF")
      (footprint "eagle-import:C0603")
      (libsource (lib "eagle-import") (part "CC0603"))
    )
    (comp (ref "C50")
      (value "CC0603")
      (footprint "eagle-import:C0603")
      (libsource (lib "eagle-import") (part "CC0603"))
    )
    (comp (ref "C51")
      (value "10uF")
      (footprint "eagle-import:C0805")
      (libsource (lib "eagle-import") (part "C"))
    )
    (comp (ref "C52")
      (value "0.1uF")
      (footprint "eagle-import:C0603")
      (libsource (lib "eagle-import") (part "CC0603"))
    )
    (comp (ref "C53")
      (value "0.1uF")
      (footprint "eagle-import:C0603")
      (libsource (lib "eagle-import") (part "CC0603"))
    )
    (comp (ref "C54")
      (value "10uF")
      (footprint "eagle-import:C0805")
      (libsource (lib "eagle-import") (part "C"))
    )
    (comp (ref "C55")
      (value "0.1uF")
      (footprint "eagle-import:C0603")
      (libsource (lib "eagle-import") (part "CC0603"))
    )
    (comp (ref "C56")
      (value "10uF")
      (footprint "eagle-import:C0805")
      (libsource (lib "eagle-import") (part "C"))
    )
    (comp (ref "C57")
      (value "0.1uF")
      (footprint "eagle-import:C0603")
      (libsource (lib "eagle-import") (part "CC0603"))
    )
    (comp (ref "C58")
      (value "10pF")
      (footprint "eagle-import:C0603")
      (libsource (lib "eagle-import") (part "CC0603"))
    )
    (comp (ref "C59")
      (value "50pF")
      (footprint "eagle-import:C0603")
      (libsource (lib "eagle-import") (part "CC0603"))
    )
    (comp (ref "U8")
      (value "AD5791BRUZ")
      (footprint "eagle-import:SOP65P640X120-20N")
      (libsource (lib "eagle-import") (part "AD5791BRUZ"))
    )
    (comp (ref "U9")
      (value "AD8676ARZ")
      (footprint "eagle-import:SOIC127P600X175-8N")
      (libsource (lib "eagle-import") (part "AD8676ARZ"))
    )
    (comp (ref "C84")
      (value "10uF")
      (footprint "eagle-import:C0805")
      (libsource (lib "eagle-import") (part "C"))
    )
    (comp (ref "C85")
      (value "0.1uF")
      (footprint "eagle-import:C0603")
      (libsource (lib "eagle-import") (part "CC0603"))
    )
    (comp (ref "C86")
      (value "CC0603")
      (footprint "eagle-import:C0603")
      (libsource (lib "eagle-import") (part "CC0603"))
    )
    (comp (ref "C87")
      (value "10uF")
      (footprint "eagle-import:C0805")
      (libsource (lib "eagle-import") (part "C"))
    )
    (comp (ref "C88")
      (value "0.1uF")
      (footprint "eagle-import:C0603")
      (libsource (lib "eagle-import") (part "CC0603"))
    )
    (comp (ref "C89")
      (value "0.1uF")
      (footprint "eagle-import:C0603")
      (libsource (lib "eagle-import") (part "CC0603"))
    )
    (comp (ref "C90")
      (value "10uF")
      (footprint "eagle-import:C0805")
      (libsource (lib "eagle-import") (part "C"))
    )
    (comp (ref "C91")
      (value "0.1uF")
      (footprint "eagle-import:C0603")
      (libsource (lib "eagle-import") (part "CC0603"))
    )
    (comp (ref "C92")
      (value "10uF")
      (footprint "eagle-import:C0805")
      (libsource (lib "eagle-import") (part "C"))
    )
    (comp (ref "C93")
      (value "0.1uF")
      (footprint "eagle-import:C0603")
      (libsource (lib "eagle-import") (part "CC0603"))
    )
    (comp (ref "C94")
      (value "10pF")
      (footprint "eagle-import:C0603")
      (libsource (lib "eagle-import") (part "CC0603"))
    )
    (comp (ref "C95")
      (value "50pF")
      (footprint "eagle-import:C0603")
      (libsource (lib "eagle-import") (part "CC0603"))
    )
    (comp (ref "U14")
      (value "AD5791BRUZ")
      (footprint "eagle-import:SOP65P640X120-20N")
      (libsource (lib "eagle-import") (part "AD5791BRUZ"))
    )
    (comp (ref "U15")
      (value "AD8676ARZ")
      (footprint "eagle-import:SOIC127P600X175-8N")
      (libsource (lib "eagle-import") (part "AD8676ARZ"))
    )
    (comp (ref "C156")
      (value "10uF")
      (footprint "eagle-import:C0805")
      (libsource (lib "eagle-import") (part "C"))
    )
    (comp (ref "C157")
      (value "0.1uF")
      (footprint "eagle-import:C0603")
      (libsource (lib "eagle-import") (part "CC0603"))
    )
    (comp (ref "C158")
      (value "CC0603")
      (footprint "eagle-import:C0603")
      (libsource (lib "eagle-import") (part "CC0603"))
    )
    (comp (ref "C159")
      (value "10uF")
      (footprint "eagle-import:C0805")
      (libsource (lib "eagle-import") (part "C"))
    )
    (comp (ref "C160")
      (value "0.1uF")
      (footprint "eagle-import:C0603")
      (libsource (lib "eagle-import") (part "CC0603"))
    )
    (comp (ref "C161")
      (value "0.1uF")
      (footprint "eagle-import:C0603")
      (libsource (lib "eagle-import") (part "CC0603"))
    )
    (comp (ref "C162")
      (value "10uF")
      (footprint "eagle-import:C0805")
      (libsource (lib "eagle-import") (part "C"))
    )
    (comp (ref "C163")
      (value "0.1uF")
      (footprint "eagle-import:C0603")
      (libsource (lib "eagle-import") (part "CC0603"))
    )
    (comp (ref "C164")
      (value "10uF")
      (footprint "eagle-import:C0805")
      (libsource (lib "eagle-import") (part "C"))
    )
    (comp (ref "C165")
      (value "0.1uF")
      (footprint "eagle-import:C0603")
      (libsource (lib "eagle-import") (part "CC0603"))
    )
    (comp (ref "C166")
      (value "10pF")
      (footprint "eagle-import:C0603")
      (libsource (lib "eagle-import") (part "CC0603"))
    )
    (comp (ref "C167")
      (value "50pF")
      (footprint "eagle-import:C0603")
      (libsource (lib "eagle-import") (part "CC0603"))
    )
    (comp (ref "U26")
      (value "AD5791BRUZ")
      (footprint "eagle-import:SOP65P640X120-20N")
      (libsource (lib "eagle-import") (part "AD5791BRUZ"))
    )
    (comp (ref "U27")
      (value "AD8676ARZ")
      (footprint "eagle-import:SOIC127P600X175-8N")
      (libsource (lib "eagle-import") (part "AD8676ARZ"))
    )
    (comp (ref "C144")
      (value "10uF")
      (footprint "eagle-import:C0805")
      (libsource (lib "eagle-import") (part "C"))
    )
    (comp (ref "C145")
      (value "0.1uF")
      (footprint "eagle-import:C0603")
      (libsource (lib "eagle-import") (part "CC0603"))
    )
    (comp (ref "C146")
      (value "CC0603")
      (footprint "eagle-import:C0603")
      (libsource (lib "eagle-import") (part "CC0603"))
    )
    (comp (ref "C147")
      (value "10uF")
      (footprint "eagle-import:C0805")
      (libsource (lib "eagle-import") (part "C"))
    )
    (comp (ref "C148")
      (value "0.1uF")
      (footprint "eagle-import:C0603")
      (libsource (lib "eagle-import") (part "CC0603"))
    )
    (comp (ref "C149")
      (value "0.1uF")
      (footprint "eagle-import:C0603")
      (libsource (lib "eagle-import") (part "CC0603"))
    )
    (comp (ref "C150")
      (value "10uF")
      (footprint "eagle-import:C0805")
      (libsource (lib "eagle-import") (part "C"))
    )
    (comp (ref "C151")
      (value "0.1uF")
      (footprint "eagle-import:C0603")
      (libsource (lib "eagle-import") (part "CC0603"))
    )
    (comp (ref "C152")
      (value "10uF")
      (footprint "eagle-import:C0805")
      (libsource (lib "eagle-import") (part "C"))
    )
    (comp (ref "C153")
      (value "0.1uF")
      (footprint "eagle-import:C0603")
      (libsource (lib "eagle-import") (part "CC0603"))
    )
    (comp (ref "C154")
      (value "10pF")
      (footprint "eagle-import:C0603")
      (libsource (lib "eagle-import") (part "CC0603"))
    )
    (comp (ref "C155")
      (value "50pF")
      (footprint "eagle-import:C0603")
      (libsource (lib "eagle-import") (part "CC0603"))
    )
    (comp (ref "U24")
      (value "AD5791BRUZ")
      (footprint "eagle-import:SOP65P640X120-20N")
      (libsource (lib "eagle-import") (part "AD5791BRUZ"))
    )
    (comp (ref "U25")
      (value "AD8676ARZ")
      (footprint "eagle-import:SOIC127P600X175-8N")
      (libsource (lib "eagle-import") (part "AD8676ARZ"))
    )
    (comp (ref "C120")
      (value "10uF")
      (footprint "eagle-import:C0805")
      (libsource (lib "eagle-import") (part "C"))
    )
    (comp (ref "C121")
      (value "0.1uF")
      (footprint "eagle-import:C0603")
      (libsource (lib "eagle-import") (part "CC0603"))
    )
    (comp (ref "C122")
      (value "CC0603")
      (footprint "eagle-import:C0603")
      (libsource (lib "eagle-import") (part "CC0603"))
    )
    (comp (ref "C123")
      (value "10uF")
      (footprint "eagle-import:C0805")
      (libsource (lib "eagle-import") (part "C"))
    )
    (comp (ref "C124")
      (value "0.1uF")
      (footprint "eagle-import:C0603")
      (libsource (lib "eagle-import") (part "CC0603"))
    )
    (comp (ref "C125")
      (value "0.1uF")
      (footprint "eagle-import:C0603")
      (libsource (lib "eagle-import") (part "CC0603"))
    )
    (comp (ref "C126")
      (value "10uF")
      (footprint "eagle-import:C0805")
      (libsource (lib "eagle-import") (part "C"))
    )
    (comp (ref "C127")
      (value "0.1uF")
      (footprint "eagle-import:C0603")
      (libsource (lib "eagle-import") (part "CC0603"))
    )
    (comp (ref "C128")
      (value "10uF")
      (footprint "eagle-import:C0805")
      (libsource (lib "eagle-import") (part "C"))
    )
    (comp (ref "C129")
      (value "0.1uF")
      (footprint "eagle-import:C0603")
      (libsource (lib "eagle-import") (part "CC0603"))
    )
    (comp (ref "C130")
      (value "10pF")
      (footprint "eagle-import:C0603")
      (libsource (lib "eagle-import") (part "CC0603"))
    )
    (comp (ref "C131")
      (value "50pF")
      (footprint "eagle-import:C0603")
      (libsource (lib "eagle-import") (part "CC0603"))
    )
    (comp (ref "U20")
      (value "AD5791BRUZ")
      (footprint "eagle-import:SOP65P640X120-20N")
      (libsource (lib "eagle-import") (part "AD5791BRUZ"))
    )
    (comp (ref "U21")
      (value "AD8676ARZ")
      (footprint "eagle-import:SOIC127P600X175-8N")
      (libsource (lib "eagle-import") (part "AD8676ARZ"))
    )
    (comp (ref "C132")
      (value "10uF")
      (footprint "eagle-import:C0805")
      (libsource (lib "eagle-import") (part "C"))
    )
    (comp (ref "C133")
      (value "0.1uF")
      (footprint "eagle-import:C0603")
      (libsource (lib "eagle-import") (part "CC0603"))
    )
    (comp (ref "C134")
      (value "CC0603")
      (footprint "eagle-import:C0603")
      (libsource (lib "eagle-import") (part "CC0603"))
    )
    (comp (ref "C135")
      (value "10uF")
      (footprint "eagle-import:C0805")
      (libsource (lib "eagle-import") (part "C"))
    )
    (comp (ref "C136")
      (value "0.1uF")
      (footprint "eagle-import:C0603")
      (libsource (lib "eagle-import") (part "CC0603"))
    )
    (comp (ref "C137")
      (value "0.1uF")
      (footprint "eagle-import:C0603")
      (libsource (lib "eagle-import") (part "CC0603"))
    )
    (comp (ref "C138")
      (value "10uF")
      (footprint "eagle-import:C0805")
      (libsource (lib "eagle-import") (part "C"))
    )
    (comp (ref "C139")
      (value "0.1uF")
      (footprint "eagle-import:C0603")
      (libsource (lib "eagle-import") (part "CC0603"))
    )
    (comp (ref "C140")
      (value "10uF")
      (footprint "eagle-import:C0805")
      (libsource (lib "eagle-import") (part "C"))
    )
    (comp (ref "C141")
      (value "0.1uF")
      (footprint "eagle-import:C0603")
      (libsource (lib "eagle-import") (part "CC0603"))
    )
    (comp (ref "C142")
      (value "10pF")
      (footprint "eagle-import:C0603")
      (libsource (lib "eagle-import") (part "CC0603"))
    )
    (comp (ref "C143")
      (value "50pF")
      (footprint "eagle-import:C0603")
      (libsource (lib "eagle-import") (part "CC0603"))
    )
    (comp (ref "U22")
      (value "AD5791BRUZ")
      (footprint "eagle-import:SOP65P640X120-20N")
      (libsource (lib "eagle-import") (part "AD5791BRUZ"))
    )
    (comp (ref "U23")
      (value "AD8676ARZ")
      (footprint "eagle-import:SOIC127P600X175-8N")
      (libsource (lib "eagle-import") (part "AD8676ARZ"))
    )
    (comp (ref "C36")
      (value "10uF")
      (footprint "eagle-import:C0805")
      (libsource (lib "eagle-import") (part "C"))
    )
    (comp (ref "C37")
      (value "0.1uF")
      (footprint "eagle-import:C0603")
      (libsource (lib "eagle-import") (part "CC0603"))
    )
    (comp (ref "C38")
      (value "CC0603")
      (footprint "eagle-import:C0603")
      (libsource (lib "eagle-import") (part "CC0603"))
    )
    (comp (ref "C39")
      (value "10uF")
      (footprint "eagle-import:C0805")
      (libsource (lib "eagle-import") (part "C"))
    )
    (comp (ref "C40")
      (value "0.1uF")
      (footprint "eagle-import:C0603")
      (libsource (lib "eagle-import") (part "CC0603"))
    )
    (comp (ref "C41")
      (value "0.1uF")
      (footprint "eagle-import:C0603")
      (libsource (lib "eagle-import") (part "CC0603"))
    )
    (comp (ref "C42")
      (value "10uF")
      (footprint "eagle-import:C0805")
      (libsource (lib "eagle-import") (part "C"))
    )
    (comp (ref "C43")
      (value "0.1uF")
      (footprint "eagle-import:C0603")
      (libsource (lib "eagle-import") (part "CC0603"))
    )
    (comp (ref "C44")
      (value "10uF")
      (footprint "eagle-import:C0805")
      (libsource (lib "eagle-import") (part "C"))
    )
    (comp (ref "C45")
      (value "0.1uF")
      (footprint "eagle-import:C0603")
      (libsource (lib "eagle-import") (part "CC0603"))
    )
    (comp (ref "C46")
      (value "10pF")
      (footprint "eagle-import:C0603")
      (libsource (lib "eagle-import") (part "CC0603"))
    )
    (comp (ref "C47")
      (value "50pF")
      (footprint "eagle-import:C0603")
      (libsource (lib "eagle-import") (part "CC0603"))
    )
    (comp (ref "U6")
      (value "AD5791BRUZ")
      (footprint "eagle-import:SOP65P640X120-20N")
      (libsource (lib "eagle-import") (part "AD5791BRUZ"))
    )
    (comp (ref "U7")
      (value "AD8676ARZ")
      (footprint "eagle-import:SOIC127P600X175-8N")
      (libsource (lib "eagle-import") (part "AD8676ARZ"))
    )
    (comp (ref "C1")
      (value "CC0603")
      (footprint "eagle-import:C0603")
      (libsource (lib "eagle-import") (part "CC0603"))
    )
    (comp (ref "C2")
      (value "CC0603")
      (footprint "eagle-import:C0603")
      (libsource (lib "eagle-import") (part "CC0603"))
    )
    (comp (ref "C3")
      (value "CC0603")
      (footprint "eagle-import:C0603")
      (libsource (lib "eagle-import") (part "CC0603"))
    )
    (comp (ref "C4")
      (value "CC0603")
      (footprint "eagle-import:C0603")
      (libsource (lib "eagle-import") (part "CC0603"))
    )
    (comp (ref "C5")
      (value "CC0603")
      (footprint "eagle-import:C0603")
      (libsource (lib "eagle-import") (part "CC0603"))
    )
    (comp (ref "C6")
      (value "CC0603")
      (footprint "eagle-import:C0603")
      (libsource (lib "eagle-import") (part "CC0603"))
    )
    (comp (ref "C7")
      (value "CC0603")
      (footprint "eagle-import:C0603")
      (libsource (lib "eagle-import") (part "CC0603"))
    )
    (comp (ref "C8")
      (value "CC0603")
      (footprint "eagle-import:C0603")
      (libsource (lib "eagle-import") (part "CC0603"))
    )
    (comp (ref "C9")
      (value "CC0603")
      (footprint "eagle-import:C0603")
      (libsource (lib "eagle-import") (part "CC0603"))
    )
    (comp (ref "C10")
      (value "CC0603")
      (footprint "eagle-import:C0603")
      (libsource (lib "eagle-import") (part "CC0603"))
    )
    (comp (ref "C13")
      (value "CC0603")
      (footprint "eagle-import:C0603")
      (libsource (lib "eagle-import") (part "CC0603"))
    )
    (comp (ref "C14")
      (value "CC0603")
      (footprint "eagle-import:C0603")
      (libsource (lib "eagle-import") (part "CC0603"))
    )
    (comp (ref "C15")
      (value "CC0603")
      (footprint "eagle-import:C0603")
      (libsource (lib "eagle-import") (part "CC0603"))
    )
    (comp (ref "C16")
      (value "CC0603")
      (footprint "eagle-import:C0603")
      (libsource (lib "eagle-import") (part "CC0603"))
    )
    (comp (ref "C17")
      (value "CC0603")
      (footprint "eagle-import:C0603")
      (libsource (lib "eagle-import") (part "CC0603"))
    )
    (comp (ref "C18")
      (value "CC0603")
      (footprint "eagle-import:C0603")
      (libsource (lib "eagle-import") (part "CC0603"))
    )
    (comp (ref "C19")
      (value "CC0603")
      (footprint "eagle-import:C0603")
      (libsource (lib "eagle-import") (part "CC0603"))
    )
    (comp (ref "C20")
      (value "CC0603")
      (footprint "eagle-import:C0603")
      (libsource (lib "eagle-import") (part "CC0603"))
    )
    (comp (ref "C21")
      (value "CC0603")
      (footprint "eagle-import:C0603")
      (libsource (lib "eagle-import") (part "CC0603"))
    )
    (comp (ref "C22")
      (value "CC0603")
      (footprint "eagle-import:C0603")
      (libsource (lib "eagle-import") (part "CC0603"))
    )
    (comp (ref "C23")
      (value ".1uF")
      (footprint "eagle-import:C0603")
      (libsource (lib "eagle-import") (part "C-EUC0603"))
    )
    (comp (ref "C24")
      (value ".1uF")
      (footprint "eagle-import:C0603")
      (libsource (lib "eagle-import") (part "C-EUC0603"))
    )
    (comp (ref "C25")
      (value ".1uF")
      (footprint "eagle-import:C0603")
      (libsource (lib "eagle-import") (part "C-EUC0603"))
    )
    (comp (ref "C194")
      (value "CC0603")
      (footprint "eagle-import:C0603")
      (libsource (lib "eagle-import") (part "CC0603"))
    )
    (comp (ref "C195")
      (value "CC0603")
      (footprint "eagle-import:C0603")
      (libsource (lib "eagle-import") (part "CC0603"))
    )
    (comp (ref "C196")
      (value "CC0603")
      (footprint "eagle-import:C0603")
      (libsource (lib "eagle-import") (part "CC0603"))
    )
    (comp (ref "C197")
      (value "CC0603")
      (footprint "eagle-import:C0603")
      (libsource (lib "eagle-import") (part "CC0603"))
    )
    (comp (ref "C198")
      (value "CC0603")
      (footprint "eagle-import:C0603")
      (libsource (lib "eagle-import") (part "CC0603"))
    )
    (comp (ref "C199")
      (value "CC0603")
      (footprint "eagle-import:C0603")
      (libsource (lib "eagle-import") (part "CC0603"))
    )
    (comp (ref "C200")
      (value "CC0603")
      (footprint "eagle-import:C0603")
      (libsource (lib "eagle-import") (part "CC0603"))
    )
    (comp (ref "C201")
      (value "CC0603")
      (footprint "eagle-import:C0603")
      (libsource (lib "eagle-import") (part "CC0603"))
    )
    (comp (ref "ISO1")
      (value "SI-SI8655")
      (footprint "eagle-import:QSOP-16")
      (libsource (lib "eagle-import") (part "SI-SI8655"))
    )
    (comp (ref "ISO2")
      (value "SI-SI8655")
      (footprint "eagle-import:QSOP-16")
      (libsource (lib "eagle-import") (part "SI-SI8655"))
    )
    (comp (ref "ISO3")
      (value "SI-SI8655")
      (footprint "eagle-import:QSOP-16")
      (libsource (lib "eagle-import") (part "SI-SI8655"))
    )
    (comp (ref "ISO4")
      (value "SI-SI8655")
      (footprint "eagle-import:QSOP-16")
      (libsource (lib "eagle-import") (part "SI-SI8655"))
    )
    (comp (ref "ISO5")
      (value "SI-SI8655")
      (footprint "eagle-import:QSOP-16")
      (libsource (lib "eagle-import") (part "SI-SI8655"))
    )
    (comp (ref "ISO6")
      (value "SI-SI8655")
      (footprint "eagle-import:QSOP-16")
      (libsource (lib "eagle-import") (part "SI-SI8655"))
    )
    (comp (ref "ISO7")
      (value "SI-SI8655")
      (footprint "eagle-import:QSOP-16")
      (libsource (lib "eagle-import") (part "SI-SI8655"))
    )
    (comp (ref "ISO8")
      (value "SI-SI8655")
      (footprint "eagle-import:QSOP-16")
      (libsource (lib "eagle-import") (part "SI-SI8655"))
    )
    (comp (ref "ISO9")
      (value "SI-SI8655")
      (footprint "eagle-import:QSOP-16")
      (libsource (lib "eagle-import") (part "SI-SI8655"))
    )
    (comp (ref "ISO10")
      (value "SI-SI8655")
      (footprint "eagle-import:QSOP-16")
      (libsource (lib "eagle-import") (part "SI-SI8655"))
    )
    (comp (ref "ISO11")
      (value "SI-SI8655")
      (footprint "eagle-import:QSOP-16")
      (libsource (lib "eagle-import") (part "SI-SI8655"))
    )
    (comp (ref "J1")
      (value "EUROCARD-CPCI-220EUROCARD-B19+AB25-NOFRONTDIM")
      (footprint "eagle-import:EUROCARD-CPCI-B19+1B25-NOFRONTDIM")
      (libsource (lib "eagle-import") (part "EUROCARD-CPCI-220EUROCARD-B19+AB25-NOFRONTDIM"))
    )
    (comp (ref "R1")
      (value "R-US_R0603")
      (footprint "eagle-import:R0603")
      (libsource (lib "eagle-import") (part "R-US_R0603"))
    )
    (comp (ref "R2")
      (value "R-US_R0603")
      (footprint "eagle-import:R0603")
      (libsource (lib "eagle-import") (part "R-US_R0603"))
    )
    (comp (ref "R3")
      (value "10k")
      (footprint "eagle-import:R0603")
      (libsource (lib "eagle-import") (part "R-US_R0603"))
    )
    (comp (ref "R6")
      (value "1k")
      (footprint "eagle-import:R0805")
      (libsource (lib "eagle-import") (part "R-US_R0805"))
    )
    (comp (ref "R7")
      (value "2k")
      (footprint "eagle-import:R0805")
      (libsource (lib "eagle-import") (part "R-US_R0805"))
    )
    (comp (ref "U1")
      (value "TI-SN74GTLP1395")
      (footprint "eagle-import:TSSOP-20")
      (libsource (lib "eagle-import") (part "TI-SN74GTLP1395"))
    )
    (comp (ref "U2")
      (value "TI-SN74GTLPH16912")
      (footprint "eagle-import:TSSOP-56")
      (libsource (lib "eagle-import") (part "TI-SN74GTLPH16912"))
    )
    (comp (ref "U3")
      (value "TI-SN74GTLPH16912")
      (footprint "eagle-import:TSSOP-56")
      (libsource (lib "eagle-import") (part "TI-SN74GTLPH16912"))
    )
    (comp (ref "U40")
      (value "TI-SN74GTLPH1655")
      (footprint "eagle-import:TSSOP-64")
      (libsource (lib "eagle-import") (part "TI-SN74GTLPH1655"))
    )
  )
  (nets
    (net (code "1") (name "+5V") (class "Default")
      (node (ref "C193") (pin "1") (pinfunction "1_1") (pintype "passive"))
      (node (ref "J1") (pin "A27") (pinfunction "A27_A27") (pintype "passive"))
      (node (ref "J1") (pin "A28") (pinfunction "A28_A28") (pintype "passive"))
      (node (ref "J1") (pin "A29") (pinfunction "A29_A29") (pintype "passive"))
      (node (ref "J1") (pin "B27") (pinfunction "B27_B27") (pintype "passive"))
      (node (ref "J1") (pin "B28") (pinfunction "B28_B28") (pintype "passive"))
      (node (ref "J1") (pin "B29") (pinfunction "B29_B29") (pintype "passive"))
      (node (ref "J1") (pin "C27") (pinfunction "C27_C27") (pintype "passive"))
      (node (ref "J1") (pin "C28") (pinfunction "C28_C28") (pintype "passive"))
      (node (ref "J1") (pin "C29") (pinfunction "C29_C29") (pintype "passive"))
      (node (ref "J1") (pin "D27") (pinfunction "D27_D27") (pintype "passive"))
      (node (ref "J1") (pin "D28") (pinfunction "D28_D28") (pintype "passive"))
      (node (ref "J1") (pin "D29") (pinfunction "D29_D29") (pintype "passive"))
      (node (ref "J1") (pin "E27") (pinfunction "E27_E27") (pintype "passive"))
      (node (ref "J1") (pin "E28") (pinfunction "E28_E28") (pintype "passive"))
      (node (ref "J1") (pin "E29") (pinfunction "E29_E29") (pintype "passive"))
      (node (ref "U29") (pin "3") (pinfunction "IN_3") (pintype "input"))
    )
    (net (code "2") (name "+PWR") (class "Default")
      (node (ref "C170") (pin "1") (pinfunction "1_1") (pintype "passive"))
      (node (ref "C171") (pin "1") (pinfunction "1_1") (pintype "passive"))
      (node (ref "C174") (pin "1") (pinfunction "1_1") (pintype "passive"))
      (node (ref "C175") (pin "1") (pinfunction "1_1") (pintype "passive"))
      (node (ref "C178") (pin "1") (pinfunction "1_1") (pintype "passive"))
      (node (ref "C179") (pin "1") (pinfunction "1_1") (pintype "passive"))
      (node (ref "C182") (pin "1") (pinfunction "1_1") (pintype "passive"))
      (node (ref "C183") (pin "1") (pinfunction "1_1") (pintype "passive"))
      (node (ref "C186") (pin "1") (pinfunction "1_1") (pintype "passive"))
      (node (ref "C187") (pin "1") (pinfunction "1_1") (pintype "passive"))
      (node (ref "C190") (pin "1") (pinfunction "1_1") (pintype "passive"))
      (node (ref "C191") (pin "1") (pinfunction "1_1") (pintype "passive"))
      (node (ref "JP3") (pin "10") (pinfunction "10_10") (pintype "passive"))
      (node (ref "JP3") (pin "12") (pinfunction "12_12") (pintype "passive"))
      (node (ref "JP3") (pin "2") (pinfunction "2_2") (pintype "passive"))
      (node (ref "JP3") (pin "4") (pinfunction "4_4") (pintype "passive"))
      (node (ref "JP3") (pin "6") (pinfunction "6_6") (pintype "passive"))
      (node (ref "JP3") (pin "8") (pinfunction "8_8") (pintype "passive"))
      (node (ref "U30") (pin "8") (pinfunction "V+_8") (pintype "power_in"))
      (node (ref "U31") (pin "8") (pinfunction "V+_8") (pintype "power_in"))
      (node (ref "U32") (pin "8") (pinfunction "V+_8") (pintype "power_in"))
      (node (ref "U33") (pin "8") (pinfunction "V+_8") (pintype "power_in"))
      (node (ref "U34") (pin "8") (pinfunction "V+_8") (pintype "power_in"))
      (node (ref "U35") (pin "8") (pinfunction "V+_8") (pintype "power_in"))
    )
    (net (code "3") (name "+RAIL") (class "Default")
      (node (ref "J1") (pin "D41") (pinfunction "D41_D41") (pintype "passive"))
      (node (ref "J1") (pin "D42") (pinfunction "D42_D42") (pintype "passive"))
      (node (ref "J1") (pin "D43") (pinfunction "D43_D43") (pintype "passive"))
      (node (ref "J1") (pin "D44") (pinfunction "D44_D44") (pintype "passive"))
      (node (ref "J1") (pin "E41") (pinfunction "E41_E41") (pintype "passive"))
      (node (ref "J1") (pin "E42") (pinfunction "E42_E42") (pintype "passive"))
      (node (ref "J1") (pin "E43") (pinfunction "E43_E43") (pintype "passive"))
      (node (ref "J1") (pin "E44") (pinfunction "E44_E44") (pintype "passive"))
      (node (ref "JP3") (pin "1") (pinfunction "1_1") (pintype "passive"))
      (node (ref "JP3") (pin "3") (pinfunction "3_3") (pintype "passive"))
      (node (ref "JP3") (pin "5") (pinfunction "5_5") (pintype "passive"))
    )
    (net (code "4") (name "+VPRW") (class "Default")
      (node (ref "560Ω") (pin "2") (pinfunction "2_2") (pintype "passive"))
      (node (ref "U28") (pin "1") (pinfunction "+VS_1") (pintype "power_in"))
    )
    (net (code "5") (name "+VPWR") (class "Default")
      (node (ref "C102") (pin "2") (pinfunction "2_2") (pintype "passive"))
      (node (ref "C103") (pin "2") (pinfunction "2_2") (pintype "passive"))
      (node (ref "C108") (pin "2") (pinfunction "2_2") (pintype "passive"))
      (node (ref "C109") (pin "2") (pinfunction "2_2") (pintype "passive"))
      (node (ref "C11") (pin "2") (pinfunction "2_2") (pintype "passive"))
      (node (ref "C114") (pin "2") (pinfunction "2_2") (pintype "passive"))
      (node (ref "C115") (pin "2") (pinfunction "2_2") (pintype "passive"))
      (node (ref "C12") (pin "2") (pinfunction "2_2") (pintype "passive"))
      (node (ref "C120") (pin "2") (pinfunction "2_2") (pintype "passive"))
      (node (ref "C121") (pin "2") (pinfunction "2_2") (pintype "passive"))
      (node (ref "C126") (pin "2") (pinfunction "2_2") (pintype "passive"))
      (node (ref "C127") (pin "2") (pinfunction "2_2") (pintype "passive"))
      (node (ref "C132") (pin "2") (pinfunction "2_2") (pintype "passive"))
      (node (ref "C133") (pin "2") (pinfunction "2_2") (pintype "passive"))
      (node (ref "C138") (pin "2") (pinfunction "2_2") (pintype "passive"))
      (node (ref "C139") (pin "2") (pinfunction "2_2") (pintype "passive"))
      (node (ref "C144") (pin "2") (pinfunction "2_2") (pintype "passive"))
      (node (ref "C145") (pin "2") (pinfunction "2_2") (pintype "passive"))
      (node (ref "C150") (pin "2") (pinfunction "2_2") (pintype "passive"))
      (node (ref "C151") (pin "2") (pinfunction "2_2") (pintype "passive"))
      (node (ref "C156") (pin "2") (pinfunction "2_2") (pintype "passive"))
      (node (ref "C157") (pin "2") (pinfunction "2_2") (pintype "passive"))
      (node (ref "C162") (pin "2") (pinfunction "2_2") (pintype "passive"))
      (node (ref "C163") (pin "2") (pinfunction "2_2") (pintype "passive"))
      (node (ref "C30") (pin "2") (pinfunction "2_2") (pintype "passive"))
      (node (ref "C31") (pin "2") (pinfunction "2_2") (pintype "passive"))
      (node (ref "C36") (pin "2") (pinfunction "2_2") (pintype "passive"))
      (node (ref "C37") (pin "2") (pinfunction "2_2") (pintype "passive"))
      (node (ref "C42") (pin "2") (pinfunction "2_2") (pintype "passive"))
      (node (ref "C43") (pin "2") (pinfunction "2_2") (pintype "passive"))
      (node (ref "C48") (pin "2") (pinfunction "2_2") (pintype "passive"))
      (node (ref "C49") (pin "2") (pinfunction "2_2") (pintype "passive"))
      (node (ref "C54") (pin "2") (pinfunction "2_2") (pintype "passive"))
      (node (ref "C55") (pin "2") (pinfunction "2_2") (pintype "passive"))
      (node (ref "C60") (pin "2") (pinfunction "2_2") (pintype "passive"))
      (node (ref "C61") (pin "2") (pinfunction "2_2") (pintype "passive"))
      (node (ref "C66") (pin "2") (pinfunction "2_2") (pintype "passive"))
      (node (ref "C67") (pin "2") (pinfunction "2_2") (pintype "passive"))
      (node (ref "C72") (pin "2") (pinfunction "2_2") (pintype "passive"))
      (node (ref "C73") (pin "2") (pinfunction "2_2") (pintype "passive"))
      (node (ref "C78") (pin "2") (pinfunction "2_2") (pintype "passive"))
      (node (ref "C79") (pin "2") (pinfunction "2_2") (pintype "passive"))
      (node (ref "C84") (pin "2") (pinfunction "2_2") (pintype "passive"))
      (node (ref "C85") (pin "2") (pinfunction "2_2") (pintype "passive"))
      (node (ref "C90") (pin "2") (pinfunction "2_2") (pintype "passive"))
      (node (ref "C91") (pin "2") (pinfunction "2_2") (pintype "passive"))
      (node (ref "C96") (pin "2") (pinfunction "2_2") (pintype "passive"))
      (node (ref "C97") (pin "2") (pinfunction "2_2") (pintype "passive"))
      (node (ref "J1") (pin "D34") (pinfunction "D34_D34") (pintype "passive"))
      (node (ref "J1") (pin "D35") (pinfunction "D35_D35") (pintype "passive"))
      (node (ref "J1") (pin "D36") (pinfunction "D36_D36") (pintype "passive"))
      (node (ref "J1") (pin "D37") (pinfunction "D37_D37") (pintype "passive"))
      (node (ref "J1") (pin "E34") (pinfunction "E34_E34") (pintype "passive"))
      (node (ref "J1") (pin "E35") (pinfunction "E35_E35") (pintype "passive"))
      (node (ref "J1") (pin "E36") (pinfunction "E36_E36") (pintype "passive"))
      (node (ref "J1") (pin "E37") (pinfunction "E37_E37") (pintype "passive"))
      (node (ref "JP3") (pin "11") (pinfunction "11_11") (pintype "passive"))
      (node (ref "JP3") (pin "7") (pinfunction "7_7") (pintype "passive"))
      (node (ref "JP3") (pin "9") (pinfunction "9_9") (pintype "passive"))
      (node (ref "U10") (pin "5") (pinfunction "VDD_5") (pintype "power_in"))
      (node (ref "U11") (pin "8") (pinfunction "V+_8") (pintype "power_in"))
      (node (ref "U12") (pin "5") (pinfunction "VDD_5") (pintype "power_in"))
      (node (ref "U13") (pin "8") (pinfunction "V+_8") (pintype "power_in"))
      (node (ref "U14") (pin "5") (pinfunction "VDD_5") (pintype "power_in"))
      (node (ref "U15") (pin "8") (pinfunction "V+_8") (pintype "power_in"))
      (node (ref "U16") (pin "5") (pinfunction "VDD_5") (pintype "power_in"))
      (node (ref "U17") (pin "8") (pinfunction "V+_8") (pintype "power_in"))
      (node (ref "U18") (pin "5") (pinfunction "VDD_5") (pintype "power_in"))
      (node (ref "U19") (pin "8") (pinfunction "V+_8") (pintype "power_in"))
      (node (ref "U20") (pin "5") (pinfunction "VDD_5") (pintype "power_in"))
      (node (ref "U21") (pin "8") (pinfunction "V+_8") (pintype "power_in"))
      (node (ref "U22") (pin "5") (pinfunction "VDD_5") (pintype "power_in"))
      (node (ref "U23") (pin "8") (pinfunction "V+_8") (pintype "power_in"))
      (node (ref "U24") (pin "5") (pinfunction "VDD_5") (pintype "power_in"))
      (node (ref "U25") (pin "8") (pinfunction "V+_8") (pintype "power_in"))
      (node (ref "U26") (pin "5") (pinfunction "VDD_5") (pintype "power_in"))
      (node (ref "U27") (pin "8") (pinfunction "V+_8") (pintype "power_in"))
      (node (ref "U4") (pin "5") (pinfunction "VDD_5") (pintype "power_in"))
      (node (ref "U5") (pin "8") (pinfunction "V+_8") (pintype "power_in"))
      (node (ref "U6") (pin "5") (pinfunction "VDD_5") (pintype "power_in"))
      (node (ref "U7") (pin "8") (pinfunction "V+_8") (pintype "power_in"))
      (node (ref "U8") (pin "5") (pinfunction "VDD_5") (pintype "power_in"))
      (node (ref "U9") (pin "8") (pinfunction "V+_8") (pintype "power_in"))
    )
    (net (code "6") (name "-PWR") (class "Default")
      (node (ref "C168") (pin "1") (pinfunction "1_1") (pintype "passive"))
      (node (ref "C169") (pin "1") (pinfunction "1_1") (pintype "passive"))
      (node (ref "C172") (pin "1") (pinfunction "1_1") (pintype "passive"))
      (node (ref "C173") (pin "1") (pinfunction "1_1") (pintype "passive"))
      (node (ref "C176") (pin "1") (pinfunction "1_1") (pintype "passive"))
      (node (ref "C177") (pin "1") (pinfunction "1_1") (pintype "passive"))
      (node (ref "C180") (pin "1") (pinfunction "1_1") (pintype "passive"))
      (node (ref "C181") (pin "1") (pinfunction "1_1") (pintype "passive"))
      (node (ref "C184") (pin "1") (pinfunction "1_1") (pintype "passive"))
      (node (ref "C185") (pin "1") (pinfunction "1_1") (pintype "passive"))
      (node (ref "C188") (pin "1") (pinfunction "1_1") (pintype "passive"))
      (node (ref "C189") (pin "1") (pinfunction "1_1") (pintype "passive"))
      (node (ref "JP2") (pin "10") (pinfunction "10_10") (pintype "passive"))
      (node (ref "JP2") (pin "12") (pinfunction "12_12") (pintype "passive"))
      (node (ref "JP2") (pin "2") (pinfunction "2_2") (pintype "passive"))
      (node (ref "JP2") (pin "4") (pinfunction "4_4") (pintype "passive"))
      (node (ref "JP2") (pin "6") (pinfunction "6_6") (pintype "passive"))
      (node (ref "JP2") (pin "8") (pinfunction "8_8") (pintype "passive"))
      (node (ref "U30") (pin "4") (pinfunction "V-_4") (pintype "power_in"))
      (node (ref "U31") (pin "4") (pinfunction "V-_4") (pintype "power_in"))
      (node (ref "U32") (pin "4") (pinfunction "V-_4") (pintype "power_in"))
      (node (ref "U33") (pin "4") (pinfunction "V-_4") (pintype "power_in"))
      (node (ref "U34") (pin "4") (pinfunction "V-_4") (pintype "power_in"))
      (node (ref "U35") (pin "4") (pinfunction "V-_4") (pintype "power_in"))
    )
    (net (code "7") (name "-RAIL") (class "Default")
      (node (ref "J1") (pin "A41") (pinfunction "A41_A41") (pintype "passive"))
      (node (ref "J1") (pin "A42") (pinfunction "A42_A42") (pintype "passive"))
      (node (ref "J1") (pin "A43") (pinfunction "A43_A43") (pintype "passive"))
      (node (ref "J1") (pin "A44") (pinfunction "A44_A44") (pintype "passive"))
      (node (ref "J1") (pin "B41") (pinfunction "B41_B41") (pintype "passive"))
      (node (ref "J1") (pin "B42") (pinfunction "B42_B42") (pintype "passive"))
      (node (ref "J1") (pin "B43") (pinfunction "B43_B43") (pintype "passive"))
      (node (ref "J1") (pin "B44") (pinfunction "B44_B44") (pintype "passive"))
      (node (ref "JP2") (pin "1") (pinfunction "1_1") (pintype "passive"))
      (node (ref "JP2") (pin "3") (pinfunction "3_3") (pintype "passive"))
      (node (ref "JP2") (pin "5") (pinfunction "5_5") (pintype "passive"))
    )
    (net (code "8") (name "-VPWR") (class "Default")
      (node (ref "C100") (pin "2") (pinfunction "2_2") (pintype "passive"))
      (node (ref "C104") (pin "2") (pinfunction "2_2") (pintype "passive"))
      (node (ref "C105") (pin "2") (pinfunction "2_2") (pintype "passive"))
      (node (ref "C111") (pin "2") (pinfunction "2_2") (pintype "passive"))
      (node (ref "C112") (pin "2") (pinfunction "2_2") (pintype "passive"))
      (node (ref "C116") (pin "2") (pinfunction "2_2") (pintype "passive"))
      (node (ref "C117") (pin "2") (pinfunction "2_2") (pintype "passive"))
      (node (ref "C123") (pin "2") (pinfunction "2_2") (pintype "passive"))
      (node (ref "C124") (pin "2") (pinfunction "2_2") (pintype "passive"))
      (node (ref "C128") (pin "2") (pinfunction "2_2") (pintype "passive"))
      (node (ref "C129") (pin "2") (pinfunction "2_2") (pintype "passive"))
      (node (ref "C135") (pin "2") (pinfunction "2_2") (pintype "passive"))
      (node (ref "C136") (pin "2") (pinfunction "2_2") (pintype "passive"))
      (node (ref "C140") (pin "2") (pinfunction "2_2") (pintype "passive"))
      (node (ref "C141") (pin "2") (pinfunction "2_2") (pintype "passive"))
      (node (ref "C147") (pin "2") (pinfunction "2_2") (pintype "passive"))
      (node (ref "C148") (pin "2") (pinfunction "2_2") (pintype "passive"))
      (node (ref "C152") (pin "2") (pinfunction "2_2") (pintype "passive"))
      (node (ref "C153") (pin "2") (pinfunction "2_2") (pintype "passive"))
      (node (ref "C159") (pin "2") (pinfunction "2_2") (pintype "passive"))
      (node (ref "C160") (pin "2") (pinfunction "2_2") (pintype "passive"))
      (node (ref "C164") (pin "2") (pinfunction "2_2") (pintype "passive"))
      (node (ref "C165") (pin "2") (pinfunction "2_2") (pintype "passive"))
      (node (ref "C27") (pin "2") (pinfunction "2_2") (pintype "passive"))
      (node (ref "C28") (pin "2") (pinfunction "2_2") (pintype "passive"))
      (node (ref "C32") (pin "2") (pinfunction "2_2") (pintype "passive"))
      (node (ref "C33") (pin "2") (pinfunction "2_2") (pintype "passive"))
      (node (ref "C39") (pin "2") (pinfunction "2_2") (pintype "passive"))
      (node (ref "C40") (pin "2") (pinfunction "2_2") (pintype "passive"))
      (node (ref "C44") (pin "2") (pinfunction "2_2") (pintype "passive"))
      (node (ref "C45") (pin "2") (pinfunction "2_2") (pintype "passive"))
      (node (ref "C51") (pin "2") (pinfunction "2_2") (pintype "passive"))
      (node (ref "C52") (pin "2") (pinfunction "2_2") (pintype "passive"))
      (node (ref "C56") (pin "2") (pinfunction "2_2") (pintype "passive"))
      (node (ref "C57") (pin "2") (pinfunction "2_2") (pintype "passive"))
      (node (ref "C63") (pin "2") (pinfunction "2_2") (pintype "passive"))
      (node (ref "C64") (pin "2") (pinfunction "2_2") (pintype "passive"))
      (node (ref "C68") (pin "2") (pinfunction "2_2") (pintype "passive"))
      (node (ref "C69") (pin "2") (pinfunction "2_2") (pintype "passive"))
      (node (ref "C75") (pin "2") (pinfunction "2_2") (pintype "passive"))
      (node (ref "C76") (pin "2") (pinfunction "2_2") (pintype "passive"))
      (node (ref "C80") (pin "2") (pinfunction "2_2") (pintype "passive"))
      (node (ref "C81") (pin "2") (pinfunction "2_2") (pintype "passive"))
      (node (ref "C87") (pin "2") (pinfunction "2_2") (pintype "passive"))
      (node (ref "C88") (pin "2") (pinfunction "2_2") (pintype "passive"))
      (node (ref "C92") (pin "2") (pinfunction "2_2") (pintype "passive"))
      (node (ref "C93") (pin "2") (pinfunction "2_2") (pintype "passive"))
      (node (ref "C99") (pin "2") (pinfunction "2_2") (pintype "passive"))
      (node (ref "J1") (pin "A34") (pinfunction "A34_A34") (pintype "passive"))
      (node (ref "J1") (pin "A35") (pinfunction "A35_A35") (pintype "passive"))
      (node (ref "J1") (pin "A36") (pinfunction "A36_A36") (pintype "passive"))
      (node (ref "J1") (pin "A37") (pinfunction "A37_A37") (pintype "passive"))
      (node (ref "J1") (pin "B34") (pinfunction "B34_B34") (pintype "passive"))
      (node (ref "J1") (pin "B35") (pinfunction "B35_B35") (pintype "passive"))
      (node (ref "J1") (pin "B36") (pinfunction "B36_B36") (pintype "passive"))
      (node (ref "J1") (pin "B37") (pinfunction "B37_B37") (pintype "passive"))
      (node (ref "JP2") (pin "11") (pinfunction "11_11") (pintype "passive"))
      (node (ref "JP2") (pin "7") (pinfunction "7_7") (pintype "passive"))
      (node (ref "JP2") (pin "9") (pinfunction "9_9") (pintype "passive"))
      (node (ref "U10") (pin "18") (pinfunction "VSS_18") (pintype "power_in"))
      (node (ref "U11") (pin "4") (pinfunction "V-_4") (pintype "power_in"))
      (node (ref "U12") (pin "18") (pinfunction "VSS_18") (pintype "power_in"))
      (node (ref "U13") (pin "4") (pinfunction "V-_4") (pintype "power_in"))
      (node (ref "U14") (pin "18") (pinfunction "VSS_18") (pintype "power_in"))
      (node (ref "U15") (pin "4") (pinfunction "V-_4") (pintype "power_in"))
      (node (ref "U16") (pin "18") (pinfunction "VSS_18") (pintype "power_in"))
      (node (ref "U17") (pin "4") (pinfunction "V-_4") (pintype "power_in"))
      (node (ref "U18") (pin "18") (pinfunction "VSS_18") (pintype "power_in"))
      (node (ref "U19") (pin "4") (pinfunction "V-_4") (pintype "power_in"))
      (node (ref "U20") (pin "18") (pinfunction "VSS_18") (pintype "power_in"))
      (node (ref "U21") (pin "4") (pinfunction "V-_4") (pintype "power_in"))
      (node (ref "U22") (pin "18") (pinfunction "VSS_18") (pintype "power_in"))
      (node (ref "U23") (pin "4") (pinfunction "V-_4") (pintype "power_in"))
      (node (ref "U24") (pin "18") (pinfunction "VSS_18") (pintype "power_in"))
      (node (ref "U25") (pin "4") (pinfunction "V-_4") (pintype "power_in"))
      (node (ref "U26") (pin "18") (pinfunction "VSS_18") (pintype "power_in"))
      (node (ref "U27") (pin "4") (pinfunction "V-_4") (pintype "power_in"))
      (node (ref "U4") (pin "18") (pinfunction "VSS_18") (pintype "power_in"))
      (node (ref "U5") (pin "4") (pinfunction "V-_4") (pintype "power_in"))
      (node (ref "U6") (pin "18") (pinfunction "VSS_18") (pintype "power_in"))
      (node (ref "U7") (pin "4") (pinfunction "V-_4") (pintype "power_in"))
      (node (ref "U8") (pin "18") (pinfunction "VSS_18") (pintype "power_in"))
      (node (ref "U9") (pin "4") (pinfunction "V-_4") (pintype "power_in"))
    )
    (net (code "9") (name "0B0") (class "Default")
      (node (ref "ISO1") (pin "4") (pinfunction "A2_4") (pintype "bidirectional"))
      (node (ref "U2") (pin "3") (pinfunction "A1_3") (pintype "bidirectional"))
    )
    (net (code "10") (name "0B1") (class "Default")
      (node (ref "ISO1") (pin "3") (pinfunction "A1_3") (pintype "bidirectional"))
      (node (ref "U2") (pin "5") (pinfunction "A2_5") (pintype "bidirectional"))
    )
    (net (code "11") (name "0B2") (class "Default")
      (node (ref "ISO2") (pin "7") (pinfunction "A5_7") (pintype "bidirectional"))
      (node (ref "U2") (pin "6") (pinfunction "A3_6") (pintype "bidirectional"))
    )
    (net (code "12") (name "0B3") (class "Default")
      (node (ref "ISO2") (pin "6") (pinfunction "A4_6") (pintype "bidirectional"))
      (node (ref "U2") (pin "8") (pinfunction "A4_8") (pintype "bidirectional"))
    )
    (net (code "13") (name "0B4") (class "Default")
      (node (ref "ISO2") (pin "5") (pinfunction "A3_5") (pintype "bidirectional"))
      (node (ref "U2") (pin "9") (pinfunction "A5_9") (pintype "bidirectional"))
    )
    (net (code "14") (name "0B5") (class "Default")
      (node (ref "ISO2") (pin "4") (pinfunction "A2_4") (pintype "bidirectional"))
      (node (ref "U2") (pin "10") (pinfunction "A6_10") (pintype "bidirectional"))
    )
    (net (code "15") (name "0B6") (class "Default")
      (node (ref "ISO2") (pin "3") (pinfunction "A1_3") (pintype "bidirectional"))
      (node (ref "U2") (pin "12") (pinfunction "A7_12") (pintype "bidirectional"))
    )
    (net (code "16") (name "0B7") (class "Default")
      (node (ref "ISO3") (pin "7") (pinfunction "A5_7") (pintype "bidirectional"))
      (node (ref "U2") (pin "13") (pinfunction "A8_13") (pintype "bidirectional"))
    )
    (net (code "17") (name "0B8") (class "Default")
      (node (ref "ISO3") (pin "6") (pinfunction "A4_6") (pintype "bidirectional"))
      (node (ref "U2") (pin "14") (pinfunction "A9_14") (pintype "bidirectional"))
    )
    (net (code "18") (name "0B9") (class "Default")
      (node (ref "ISO3") (pin "5") (pinfunction "A3_5") (pintype "bidirectional"))
      (node (ref "U2") (pin "15") (pinfunction "A10_15") (pintype "bidirectional"))
    )
    (net (code "19") (name "0B10") (class "Default")
      (node (ref "ISO3") (pin "4") (pinfunction "A2_4") (pintype "bidirectional"))
      (node (ref "U2") (pin "16") (pinfunction "A11_16") (pintype "bidirectional"))
    )
    (net (code "20") (name "0B11") (class "Default")
      (node (ref "ISO3") (pin "3") (pinfunction "A1_3") (pintype "bidirectional"))
      (node (ref "U2") (pin "17") (pinfunction "A12_17") (pintype "bidirectional"))
    )
    (net (code "21") (name "0B12") (class "Default")
      (node (ref "ISO4") (pin "7") (pinfunction "A5_7") (pintype "bidirectional"))
      (node (ref "U2") (pin "19") (pinfunction "A13_19") (pintype "bidirectional"))
    )
    (net (code "22") (name "0B13") (class "Default")
      (node (ref "ISO4") (pin "6") (pinfunction "A4_6") (pintype "bidirectional"))
      (node (ref "U2") (pin "20") (pinfunction "A14_20") (pintype "bidirectional"))
    )
    (net (code "23") (name "0B14") (class "Default")
      (node (ref "ISO4") (pin "5") (pinfunction "A3_5") (pintype "bidirectional"))
      (node (ref "U2") (pin "21") (pinfunction "A15_21") (pintype "bidirectional"))
    )
    (net (code "24") (name "0B15") (class "Default")
      (node (ref "ISO4") (pin "4") (pinfunction "A2_4") (pintype "bidirectional"))
      (node (ref "U2") (pin "23") (pinfunction "A16_23") (pintype "bidirectional"))
    )
    (net (code "25") (name "0B16") (class "Default")
      (node (ref "ISO4") (pin "3") (pinfunction "A1_3") (pintype "bidirectional"))
      (node (ref "U2") (pin "24") (pinfunction "A17_24") (pintype "bidirectional"))
    )
    (net (code "26") (name "0B17") (class "Default")
      (node (ref "ISO5") (pin "7") (pinfunction "A5_7") (pintype "bidirectional"))
      (node (ref "U2") (pin "26") (pinfunction "A18_26") (pintype "bidirectional"))
    )
    (net (code "27") (name "1B0") (class "Default")
      (node (ref "ISO5") (pin "6") (pinfunction "A4_6") (pintype "bidirectional"))
      (node (ref "U3") (pin "3") (pinfunction "A1_3") (pintype "bidirectional"))
    )
    (net (code "28") (name "1B1") (class "Default")
      (node (ref "ISO5") (pin "5") (pinfunction "A3_5") (pintype "bidirectional"))
      (node (ref "U3") (pin "5") (pinfunction "A2_5") (pintype "bidirectional"))
    )
    (net (code "29") (name "1B2") (class "Default")
      (node (ref "ISO5") (pin "4") (pinfunction "A2_4") (pintype "bidirectional"))
      (node (ref "U3") (pin "6") (pinfunction "A3_6") (pintype "bidirectional"))
    )
    (net (code "30") (name "1B3") (class "Default")
      (node (ref "ISO5") (pin "3") (pinfunction "A1_3") (pintype "bidirectional"))
      (node (ref "U3") (pin "8") (pinfunction "A4_8") (pintype "bidirectional"))
    )
    (net (code "31") (name "1B4") (class "Default")
      (node (ref "ISO6") (pin "7") (pinfunction "A5_7") (pintype "bidirectional"))
      (node (ref "U3") (pin "9") (pinfunction "A5_9") (pintype "bidirectional"))
    )
    (net (code "32") (name "1B5") (class "Default")
      (node (ref "ISO6") (pin "6") (pinfunction "A4_6") (pintype "bidirectional"))
      (node (ref "U3") (pin "10") (pinfunction "A6_10") (pintype "bidirectional"))
    )
    (net (code "33") (name "1B6") (class "Default")
      (node (ref "ISO6") (pin "5") (pinfunction "A3_5") (pintype "bidirectional"))
      (node (ref "U3") (pin "12") (pinfunction "A7_12") (pintype "bidirectional"))
    )
    (net (code "34") (name "1B7") (class "Default")
      (node (ref "ISO6") (pin "4") (pinfunction "A2_4") (pintype "bidirectional"))
      (node (ref "U3") (pin "13") (pinfunction "A8_13") (pintype "bidirectional"))
    )
    (net (code "35") (name "1B8") (class "Default")
      (node (ref "ISO6") (pin "3") (pinfunction "A1_3") (pintype "bidirectional"))
      (node (ref "U3") (pin "14") (pinfunction "A9_14") (pintype "bidirectional"))
    )
    (net (code "36") (name "1B9") (class "Default")
      (node (ref "ISO7") (pin "7") (pinfunction "A5_7") (pintype "bidirectional"))
      (node (ref "U3") (pin "15") (pinfunction "A10_15") (pintype "bidirectional"))
    )
    (net (code "37") (name "1B10") (class "Default")
      (node (ref "ISO7") (pin "6") (pinfunction "A4_6") (pintype "bidirectional"))
      (node (ref "U3") (pin "16") (pinfunction "A11_16") (pintype "bidirectional"))
    )
    (net (code "38") (name "1B11") (class "Default")
      (node (ref "ISO7") (pin "5") (pinfunction "A3_5") (pintype "bidirectional"))
      (node (ref "U3") (pin "17") (pinfunction "A12_17") (pintype "bidirectional"))
    )
    (net (code "39") (name "1B12") (class "Default")
      (node (ref "ISO7") (pin "4") (pinfunction "A2_4") (pintype "bidirectional"))
      (node (ref "U3") (pin "19") (pinfunction "A13_19") (pintype "bidirectional"))
    )
    (net (code "40") (name "1B13") (class "Default")
      (node (ref "ISO7") (pin "3") (pinfunction "A1_3") (pintype "bidirectional"))
      (node (ref "U3") (pin "20") (pinfunction "A14_20") (pintype "bidirectional"))
    )
    (net (code "41") (name "1B14") (class "Default")
      (node (ref "ISO8") (pin "7") (pinfunction "A5_7") (pintype "bidirectional"))
      (node (ref "U3") (pin "21") (pinfunction "A15_21") (pintype "bidirectional"))
    )
    (net (code "42") (name "1B15") (class "Default")
      (node (ref "ISO8") (pin "6") (pinfunction "A4_6") (pintype "bidirectional"))
      (node (ref "U3") (pin "23") (pinfunction "A16_23") (pintype "bidirectional"))
    )
    (net (code "43") (name "1B16") (class "Default")
      (node (ref "ISO8") (pin "5") (pinfunction "A3_5") (pintype "bidirectional"))
      (node (ref "U3") (pin "24") (pinfunction "A17_24") (pintype "bidirectional"))
    )
    (net (code "44") (name "1B17") (class "Default")
      (node (ref "ISO8") (pin "4") (pinfunction "A2_4") (pintype "bidirectional"))
      (node (ref "U3") (pin "26") (pinfunction "A18_26") (pintype "bidirectional"))
    )
    (net (code "45") (name "2B0-1") (class "Default")
      (node (ref "ISO8") (pin "3") (pinfunction "A1_3") (pintype "bidirectional"))
      (node (ref "U40") (pin "6") (pinfunction "1A2_6") (pintype "bidirectional"))
    )
    (net (code "46") (name "2B0-2") (class "Default")
      (node (ref "ISO11") (pin "7") (pinfunction "A5_7") (pintype "bidirectional"))
      (node (ref "U40") (pin "7") (pinfunction "1A3_7") (pintype "bidirectional"))
    )
    (net (code "47") (name "2B0-3") (class "Default")
      (node (ref "ISO11") (pin "6") (pinfunction "A4_6") (pintype "bidirectional"))
      (node (ref "U40") (pin "9") (pinfunction "1A4_9") (pintype "bidirectional"))
    )
    (net (code "48") (name "2B0-4") (class "Default")
      (node (ref "ISO11") (pin "5") (pinfunction "A3_5") (pintype "bidirectional"))
      (node (ref "U40") (pin "11") (pinfunction "1A5_11") (pintype "bidirectional"))
    )
    (net (code "49") (name "2B0-5") (class "Default")
      (node (ref "ISO11") (pin "4") (pinfunction "A2_4") (pintype "bidirectional"))
      (node (ref "U40") (pin "13") (pinfunction "1A6_13") (pintype "bidirectional"))
    )
    (net (code "50") (name "2B0-7") (class "Default")
      (node (ref "ISO11") (pin "3") (pinfunction "A1_3") (pintype "bidirectional"))
      (node (ref "U40") (pin "16") (pinfunction "1A8_16") (pintype "bidirectional"))
    )
    (net (code "51") (name "2B1-0") (class "Default")
      (node (ref "ISO9") (pin "14") (pinfunction "B1_14") (pintype "bidirectional"))
      (node (ref "U40") (pin "17") (pinfunction "2A1_17") (pintype "bidirectional"))
    )
    (net (code "52") (name "2B1-1") (class "Default")
      (node (ref "ISO9") (pin "13") (pinfunction "B2_13") (pintype "bidirectional"))
      (node (ref "U40") (pin "19") (pinfunction "2A2_19") (pintype "bidirectional"))
    )
    (net (code "53") (name "2B1-2") (class "Default")
      (node (ref "ISO9") (pin "12") (pinfunction "B3_12") (pintype "bidirectional"))
      (node (ref "U40") (pin "20") (pinfunction "2A3_20") (pintype "bidirectional"))
    )
    (net (code "54") (name "2B1-3") (class "Default")
      (node (ref "ISO9") (pin "11") (pinfunction "B4_11") (pintype "bidirectional"))
      (node (ref "U40") (pin "22") (pinfunction "2A4_22") (pintype "bidirectional"))
    )
    (net (code "55") (name "2B1-4") (class "Default")
      (node (ref "ISO9") (pin "10") (pinfunction "B5_10") (pintype "bidirectional"))
      (node (ref "U40") (pin "23") (pinfunction "2A5_23") (pintype "bidirectional"))
    )
    (net (code "56") (name "2B1-5") (class "Default")
      (node (ref "ISO10") (pin "14") (pinfunction "B1_14") (pintype "bidirectional"))
      (node (ref "U40") (pin "25") (pinfunction "2A6_25") (pintype "bidirectional"))
    )
    (net (code "57") (name "2B1-6") (class "Default")
      (node (ref "ISO10") (pin "13") (pinfunction "B2_13") (pintype "bidirectional"))
      (node (ref "U40") (pin "27") (pinfunction "2A7_27") (pintype "bidirectional"))
    )
    (net (code "58") (name "2B1-7") (class "Default")
      (node (ref "ISO10") (pin "12") (pinfunction "B3_12") (pintype "bidirectional"))
      (node (ref "U40") (pin "29") (pinfunction "2A8_29") (pintype "bidirectional"))
    )
    (net (code "59") (name "ANALOG_REF") (class "Default")
      (node (ref "560Ω") (pin "1") (pinfunction "1_1") (pintype "passive"))
      (node (ref "C101") (pin "1") (pinfunction "1_1") (pintype "passive"))
      (node (ref "C113") (pin "1") (pinfunction "1_1") (pintype "passive"))
      (node (ref "C125") (pin "1") (pinfunction "1_1") (pintype "passive"))
      (node (ref "C137") (pin "1") (pinfunction "1_1") (pintype "passive"))
      (node (ref "C149") (pin "1") (pinfunction "1_1") (pintype "passive"))
      (node (ref "C161") (pin "1") (pinfunction "1_1") (pintype "passive"))
      (node (ref "C29") (pin "1") (pinfunction "1_1") (pintype "passive"))
      (node (ref "C41") (pin "1") (pinfunction "1_1") (pintype "passive"))
      (node (ref "C53") (pin "1") (pinfunction "1_1") (pintype "passive"))
      (node (ref "C65") (pin "1") (pinfunction "1_1") (pintype "passive"))
      (node (ref "C77") (pin "1") (pinfunction "1_1") (pintype "passive"))
      (node (ref "C89") (pin "1") (pinfunction "1_1") (pintype "passive"))
      (node (ref "U11") (pin "3") (pinfunction "+IN_A_3") (pintype "input"))
      (node (ref "U13") (pin "3") (pinfunction "+IN_A_3") (pintype "input"))
      (node (ref "U15") (pin "3") (pinfunction "+IN_A_3") (pintype "input"))
      (node (ref "U17") (pin "3") (pinfunction "+IN_A_3") (pintype "input"))
      (node (ref "U19") (pin "3") (pinfunction "+IN_A_3") (pintype "input"))
      (node (ref "U21") (pin "3") (pinfunction "+IN_A_3") (pintype "input"))
      (node (ref "U23") (pin "3") (pinfunction "+IN_A_3") (pintype "input"))
      (node (ref "U25") (pin "3") (pinfunction "+IN_A_3") (pintype "input"))
      (node (ref "U27") (pin "3") (pinfunction "+IN_A_3") (pintype "input"))
      (node (ref "U28") (pin "2") (pinfunction "VOUT_2") (pintype "output"))
      (node (ref "U5") (pin "3") (pinfunction "+IN_A_3") (pintype "input"))
      (node (ref "U7") (pin "3") (pinfunction "+IN_A_3") (pintype "input"))
      (node (ref "U9") (pin "3") (pinfunction "+IN_A_3") (pintype "input"))
    )
    (net (code "60") (name "CSIN") (class "Default")
      (node (ref "ISO1") (pin "12") (pinfunction "B3_12") (pintype "bidirectional"))
    )
    (net (code "61") (name "CSOUT") (class "Default")
      (node (ref "ISO1") (pin "11") (pinfunction "B4_11") (pintype "bidirectional"))
    )
    (net (code "62") (name "DACO_1") (class "Default")
      (node (ref "C35") (pin "2") (pinfunction "2_2") (pintype "passive"))
      (node (ref "R21") (pin "2") (pinfunction "2_2") (pintype "passive"))
      (node (ref "U30") (pin "5") (pinfunction "+INB_5") (pintype "input"))
      (node (ref "U4") (pin "2") (pinfunction "VOUT_2") (pintype "output"))
    )
    (net (code "63") (name "DACO_2") (class "Default")
      (node (ref "C47") (pin "2") (pinfunction "2_2") (pintype "passive"))
      (node (ref "R24") (pin "2") (pinfunction "2_2") (pintype "passive"))
      (node (ref "U31") (pin "5") (pinfunction "+INB_5") (pintype "input"))
      (node (ref "U6") (pin "2") (pinfunction "VOUT_2") (pintype "output"))
    )
    (net (code "64") (name "DACO_3") (class "Default")
      (node (ref "C59") (pin "2") (pinfunction "2_2") (pintype "passive"))
      (node (ref "R28") (pin "2") (pinfunction "2_2") (pintype "passive"))
      (node (ref "U32") (pin "5") (pinfunction "+INB_5") (pintype "input"))
      (node (ref "U8") (pin "2") (pinfunction "VOUT_2") (pintype "output"))
    )
    (net (code "65") (name "DACO_4") (class "Default")
      (node (ref "C71") (pin "2") (pinfunction "2_2") (pintype "passive"))
      (node (ref "U10") (pin "2") (pinfunction "VOUT_2") (pintype "output"))
      (node (ref "U33") (pin "5") (pinfunction "+INB_5") (pintype "input"))
    )
    (net (code "66") (name "DACO_5") (class "Default")
      (node (ref "C83") (pin "2") (pinfunction "2_2") (pintype "passive"))
      (node (ref "U12") (pin "2") (pinfunction "VOUT_2") (pintype "output"))
      (node (ref "U34") (pin "5") (pinfunction "+INB_5") (pintype "input"))
    )
    (net (code "67") (name "DACO_6") (class "Default")
      (node (ref "C95") (pin "2") (pinfunction "2_2") (pintype "passive"))
      (node (ref "U14") (pin "2") (pinfunction "VOUT_2") (pintype "output"))
      (node (ref "U35") (pin "5") (pinfunction "+INB_5") (pintype "input"))
    )
    (net (code "68") (name "DACO_7") (class "Default")
      (node (ref "C107") (pin "2") (pinfunction "2_2") (pintype "passive"))
      (node (ref "R19") (pin "1") (pinfunction "1_1") (pintype "passive"))
      (node (ref "U16") (pin "2") (pinfunction "VOUT_2") (pintype "output"))
      (node (ref "U30") (pin "3") (pinfunction "+INA_3") (pintype "input"))
    )
    (net (code "69") (name "DACO_8") (class "Default")
      (node (ref "C119") (pin "2") (pinfunction "2_2") (pintype "passive"))
      (node (ref "R25") (pin "1") (pinfunction "1_1") (pintype "passive"))
      (node (ref "U18") (pin "2") (pinfunction "VOUT_2") (pintype "output"))
      (node (ref "U31") (pin "3") (pinfunction "+INA_3") (pintype "input"))
    )
    (net (code "70") (name "DACO_9") (class "Default")
      (node (ref "C131") (pin "2") (pinfunction "2_2") (pintype "passive"))
      (node (ref "R29") (pin "1") (pinfunction "1_1") (pintype "passive"))
      (node (ref "U20") (pin "2") (pinfunction "VOUT_2") (pintype "output"))
      (node (ref "U32") (pin "3") (pinfunction "+INA_3") (pintype "input"))
    )
    (net (code "71") (name "DACO_10") (class "Default")
      (node (ref "C143") (pin "2") (pinfunction "2_2") (pintype "passive"))
      (node (ref "U22") (pin "2") (pinfunction "VOUT_2") (pintype "output"))
      (node (ref "U33") (pin "3") (pinfunction "+INA_3") (pintype "input"))
    )
    (net (code "72") (name "DACO_11") (class "Default")
      (node (ref "C155") (pin "2") (pinfunction "2_2") (pintype "passive"))
      (node (ref "U24") (pin "2") (pinfunction "VOUT_2") (pintype "output"))
      (node (ref "U34") (pin "3") (pinfunction "+INA_3") (pintype "input"))
    )
    (net (code "73") (name "DACO_12") (class "Default")
      (node (ref "C167") (pin "2") (pinfunction "2_2") (pintype "passive"))
      (node (ref "U26") (pin "2") (pinfunction "VOUT_2") (pintype "output"))
      (node (ref "U35") (pin "3") (pinfunction "+INA_3") (pintype "input"))
    )
    (net (code "74") (name "DAUX0") (class "Default")
      (node (ref "J1") (pin "A1") (pinfunction "A1_A1") (pintype "passive"))
    )
    (net (code "75") (name "DAUX1") (class "Default")
      (node (ref "J1") (pin "D23") (pinfunction "D23_D23") (pintype "passive"))
    )
    (net (code "76") (name "DAUX2") (class "Default")
      (node (ref "J1") (pin "E24") (pinfunction "E24_E24") (pintype "passive"))
    )
    (net (code "77") (name "DAUX3") (class "Default")
      (node (ref "J1") (pin "C24") (pinfunction "C24_C24") (pintype "passive"))
    )
    (net (code "78") (name "DCLK0") (class "Default")
      (node (ref "ISO11") (pin "14") (pinfunction "B1_14") (pintype "bidirectional"))
    )
    (net (code "79") (name "DCLK1") (class "Default")
      (node (ref "ISO11") (pin "13") (pinfunction "B2_13") (pintype "bidirectional"))
    )
    (net (code "80") (name "DCLK2") (class "Default")
      (node (ref "ISO11") (pin "12") (pinfunction "B3_12") (pintype "bidirectional"))
    )
    (net (code "81") (name "DCLK3") (class "Default")
      (node (ref "ISO11") (pin "11") (pinfunction "B4_11") (pintype "bidirectional"))
    )
    (net (code "82") (name "DCLK5") (class "Default")
      (node (ref "ISO8") (pin "14") (pinfunction "B1_14") (pintype "bidirectional"))
    )
    (net (code "83") (name "DGND") (class "Default")
      (node (ref "C1") (pin "2") (pinfunction "2_2") (pintype "passive"))
      (node (ref "C10") (pin "2") (pinfunction "2_2") (pintype "passive"))
      (node (ref "C13") (pin "2") (pinfunction "2_2") (pintype "passive"))
      (node (ref "C14") (pin "2") (pinfunction "2_2") (pintype "passive"))
      (node (ref "C15") (pin "2") (pinfunction "2_2") (pintype "passive"))
      (node (ref "C16") (pin "2") (pinfunction "2_2") (pintype "passive"))
      (node (ref "C17") (pin "2") (pinfunction "2_2") (pintype "passive"))
      (node (ref "C18") (pin "2") (pinfunction "2_2") (pintype "passive"))
      (node (ref "C19") (pin "2") (pinfunction "2_2") (pintype "passive"))
      (node (ref "C2") (pin "2") (pinfunction "2_2") (pintype "passive"))
      (node (ref "C20") (pin "2") (pinfunction "2_2") (pintype "passive"))
      (node (ref "C21") (pin "2") (pinfunction "2_2") (pintype "passive"))
      (node (ref "C22") (pin "2") (pinfunction "2_2") (pintype "passive"))
      (node (ref "C23") (pin "2") (pinfunction "2_2") (pintype "passive"))
      (node (ref "C24") (pin "2") (pinfunction "2_2") (pintype "passive"))
      (node (ref "C25") (pin "2") (pinfunction "2_2") (pintype "passive"))
      (node (ref "C3") (pin "2") (pinfunction "2_2") (pintype "passive"))
      (node (ref "C4") (pin "2") (pinfunction "2_2") (pintype "passive"))
      (node (ref "C5") (pin "2") (pinfunction "2_2") (pintype "passive"))
      (node (ref "C6") (pin "2") (pinfunction "2_2") (pintype "passive"))
      (node (ref "C7") (pin "2") (pinfunction "2_2") (pintype "passive"))
      (node (ref "C8") (pin "2") (pinfunction "2_2") (pintype "passive"))
      (node (ref "C9") (pin "2") (pinfunction "2_2") (pintype "passive"))
      (node (ref "ISO1") (pin "2") (pinfunction "GND1_2") (pintype "bidirectional"))
      (node (ref "ISO1") (pin "8") (pinfunction "GND1_8") (pintype "bidirectional"))
      (node (ref "ISO10") (pin "15") (pinfunction "GND2_15") (pintype "bidirectional"))
      (node (ref "ISO10") (pin "9") (pinfunction "GND2_9") (pintype "bidirectional"))
      (node (ref "ISO11") (pin "2") (pinfunction "GND1_2") (pintype "bidirectional"))
      (node (ref "ISO11") (pin "8") (pinfunction "GND1_8") (pintype "bidirectional"))
      (node (ref "ISO2") (pin "2") (pinfunction "GND1_2") (pintype "bidirectional"))
      (node (ref "ISO2") (pin "8") (pinfunction "GND1_8") (pintype "bidirectional"))
      (node (ref "ISO3") (pin "2") (pinfunction "GND1_2") (pintype "bidirectional"))
      (node (ref "ISO3") (pin "8") (pinfunction "GND1_8") (pintype "bidirectional"))
      (node (ref "ISO4") (pin "2") (pinfunction "GND1_2") (pintype "bidirectional"))
      (node (ref "ISO4") (pin "8") (pinfunction "GND1_8") (pintype "bidirectional"))
      (node (ref "ISO5") (pin "2") (pinfunction "GND1_2") (pintype "bidirectional"))
      (node (ref "ISO5") (pin "8") (pinfunction "GND1_8") (pintype "bidirectional"))
      (node (ref "ISO6") (pin "2") (pinfunction "GND1_2") (pintype "bidirectional"))
      (node (ref "ISO6") (pin "8") (pinfunction "GND1_8") (pintype "bidirectional"))
      (node (ref "ISO7") (pin "2") (pinfunction "GND1_2") (pintype "bidirectional"))
      (node (ref "ISO7") (pin "8") (pinfunction "GND1_8") (pintype "bidirectional"))
      (node (ref "ISO8") (pin "2") (pinfunction "GND1_2") (pintype "bidirectional"))
      (node (ref "ISO8") (pin "8") (pinfunction "GND1_8") (pintype "bidirectional"))
      (node (ref "ISO9") (pin "15") (pinfunction "GND2_15") (pintype "bidirectional"))
      (node (ref "ISO9") (pin "9") (pinfunction "GND2_9") (pintype "bidirectional"))
      (node (ref "J1") (pin "C11") (pinfunction "C11_C11") (pintype "passive"))
      (node (ref "J1") (pin "C14") (pinfunction "C14_C14") (pintype "passive"))
      (node (ref "J1") (pin "C17") (pinfunction "C17_C17") (pintype "passive"))
      (node (ref "J1") (pin "C2") (pinfunction "C2_C2") (pintype "passive"))
      (node (ref "J1") (pin "C20") (pinfunction "C20_C20") (pintype "passive"))
      (node (ref "J1") (pin "C23") (pinfunction "C23_C23") (pintype "passive"))
      (node (ref "J1") (pin "C25") (pinfunction "C25_C25") (pintype "passive"))
      (node (ref "J1") (pin "C5") (pinfunction "C5_C5") (pintype "passive"))
      (node (ref "J1") (pin "C8") (pinfunction "C8_C8") (pintype "passive"))
      (node (ref "J1") (pin "D1") (pinfunction "D1_D1") (pintype "passive"))
      (node (ref "J1") (pin "D10") (pinfunction "D10_D10") (pintype "passive"))
      (node (ref "J1") (pin "D12") (pinfunction "D12_D12") (pintype "passive"))
      (node (ref "J1") (pin "D13") (pinfunction "D13_D13") (pintype "passive"))
      (node (ref "J1") (pin "D15") (pinfunction "D15_D15") (pintype "passive"))
      (node (ref "J1") (pin "D16") (pinfunction "D16_D16") (pintype "passive"))
      (node (ref "J1") (pin "D18") (pinfunction "D18_D18") (pintype "passive"))
      (node (ref "J1") (pin "D19") (pinfunction "D19_D19") (pintype "passive"))
      (node (ref "J1") (pin "D21") (pinfunction "D21_D21") (pintype "passive"))
      (node (ref "J1") (pin "D22") (pinfunction "D22_D22") (pintype "passive"))
      (node (ref "J1") (pin "D24") (pinfunction "D24_D24") (pintype "passive"))
      (node (ref "J1") (pin "D25") (pinfunction "D25_D25") (pintype "passive"))
      (node (ref "J1") (pin "D3") (pinfunction "D3_D3") (pintype "passive"))
      (node (ref "J1") (pin "D4") (pinfunction "D4_D4") (pintype "passive"))
      (node (ref "J1") (pin "D6") (pinfunction "D6_D6") (pintype "passive"))
      (node (ref "J1") (pin "D7") (pinfunction "D7_D7") (pintype "passive"))
      (node (ref "J1") (pin "D9") (pinfunction "D9_D9") (pintype "passive"))
      (node (ref "J1") (pin "E11") (pinfunction "E11_E11") (pintype "passive"))
      (node (ref "J1") (pin "E14") (pinfunction "E14_E14") (pintype "passive"))
      (node (ref "J1") (pin "E17") (pinfunction "E17_E17") (pintype "passive"))
      (node (ref "J1") (pin "E2") (pinfunction "E2_E2") (pintype "passive"))
      (node (ref "J1") (pin "E20") (pinfunction "E20_E20") (pintype "passive"))
      (node (ref "J1") (pin "E23") (pinfunction "E23_E23") (pintype "passive"))
      (node (ref "J1") (pin "E25") (pinfunction "E25_E25") (pintype "passive"))
      (node (ref "J1") (pin "E5") (pinfunction "E5_E5") (pintype "passive"))
      (node (ref "J1") (pin "E8") (pinfunction "E8_E8") (pintype "passive"))
      (node (ref "R1") (pin "1") (pinfunction "1_1") (pintype "passive"))
      (node (ref "R2") (pin "1") (pinfunction "1_1") (pintype "passive"))
      (node (ref "R3") (pin "1") (pinfunction "1_1") (pintype "passive"))
      (node (ref "R7") (pin "1") (pinfunction "1_1") (pintype "passive"))
      (node (ref "U1") (pin "13") (pinfunction "GND_13") (pintype "bidirectional"))
      (node (ref "U1") (pin "15") (pinfunction "ERC_15") (pintype "bidirectional"))
      (node (ref "U1") (pin "17") (pinfunction "GND_17") (pintype "bidirectional"))
      (node (ref "U1") (pin "4") (pinfunction "GND_4") (pintype "bidirectional"))
      (node (ref "U1") (pin "8") (pinfunction "GND_8") (pintype "bidirectional"))
      (node (ref "U2") (pin "11") (pinfunction "GND_11") (pintype "bidirectional"))
      (node (ref "U2") (pin "18") (pinfunction "GND_18") (pintype "bidirectional"))
      (node (ref "U2") (pin "25") (pinfunction "GND_25") (pintype "bidirectional"))
      (node (ref "U2") (pin "27") (pinfunction "~{OEBA}_27") (pintype "bidirectional"))
      (node (ref "U2") (pin "28") (pinfunction "LEBA_28") (pintype "bidirectional"))
      (node (ref "U2") (pin "29") (pinfunction "~{CEBA}_29") (pintype "bidirectional"))
      (node (ref "U2") (pin "32") (pinfunction "GND_32") (pintype "bidirectional"))
      (node (ref "U2") (pin "39") (pinfunction "GND_39") (pintype "bidirectional"))
      (node (ref "U2") (pin "4") (pinfunction "GND_4") (pintype "bidirectional"))
      (node (ref "U2") (pin "46") (pinfunction "GND_46") (pintype "bidirectional"))
      (node (ref "U2") (pin "53") (pinfunction "GND_53") (pintype "bidirectional"))
      (node (ref "U2") (pin "55") (pinfunction "CLKAB_55") (pintype "bidirectional"))
      (node (ref "U2") (pin "56") (pinfunction "~{CEAB}_56") (pintype "bidirectional"))
      (node (ref "U3") (pin "11") (pinfunction "GND_11") (pintype "bidirectional"))
      (node (ref "U3") (pin "18") (pinfunction "GND_18") (pintype "bidirectional"))
      (node (ref "U3") (pin "25") (pinfunction "GND_25") (pintype "bidirectional"))
      (node (ref "U3") (pin "27") (pinfunction "~{OEBA}_27") (pintype "bidirectional"))
      (node (ref "U3") (pin "28") (pinfunction "LEBA_28") (pintype "bidirectional"))
      (node (ref "U3") (pin "29") (pinfunction "~{CEBA}_29") (pintype "bidirectional"))
      (node (ref "U3") (pin "32") (pinfunction "GND_32") (pintype "bidirectional"))
      (node (ref "U3") (pin "39") (pinfunction "GND_39") (pintype "bidirectional"))
      (node (ref "U3") (pin "4") (pinfunction "GND_4") (pintype "bidirectional"))
      (node (ref "U3") (pin "46") (pinfunction "GND_46") (pintype "bidirectional"))
      (node (ref "U3") (pin "53") (pinfunction "GND_53") (pintype "bidirectional"))
      (node (ref "U3") (pin "55") (pinfunction "CLKAB_55") (pintype "bidirectional"))
      (node (ref "U3") (pin "56") (pinfunction "~{CEAB}_56") (pintype "bidirectional"))
      (node (ref "U40") (pin "10") (pinfunction "GND_10") (pintype "bidirectional"))
      (node (ref "U40") (pin "12") (pinfunction "GND_12") (pintype "bidirectional"))
      (node (ref "U40") (pin "18") (pinfunction "GND_18") (pintype "bidirectional"))
      (node (ref "U40") (pin "2") (pinfunction "1~{OEBA}_2") (pintype "bidirectional"))
      (node (ref "U40") (pin "21") (pinfunction "GND_21") (pintype "bidirectional"))
      (node (ref "U40") (pin "24") (pinfunction "GND_24") (pintype "bidirectional"))
      (node (ref "U40") (pin "26") (pinfunction "GND_26") (pintype "bidirectional"))
      (node (ref "U40") (pin "30") (pinfunction "GND_30") (pintype "bidirectional"))
      (node (ref "U40") (pin "33") (pinfunction "~{OE}_33") (pintype "bidirectional"))
      (node (ref "U40") (pin "34") (pinfunction "2LEBA_34") (pintype "bidirectional"))
      (node (ref "U40") (pin "39") (pinfunction "GND_39") (pintype "bidirectional"))
      (node (ref "U40") (pin "44") (pinfunction "GND_44") (pintype "bidirectional"))
      (node (ref "U40") (pin "47") (pinfunction "GND_47") (pintype "bidirectional"))
      (node (ref "U40") (pin "5") (pinfunction "GND_5") (pintype "bidirectional"))
      (node (ref "U40") (pin "53") (pinfunction "GND_53") (pintype "bidirectional"))
      (node (ref "U40") (pin "57") (pinfunction "GND_57") (pintype "bidirectional"))
      (node (ref "U40") (pin "60") (pinfunction "GND_60") (pintype "bidirectional"))
      (node (ref "U40") (pin "61") (pinfunction "ERC_61") (pintype "bidirectional"))
      (node (ref "U40") (pin "63") (pinfunction "1LEAB_63") (pintype "bidirectional"))
      (node (ref "U40") (pin "64") (pinfunction "CLK_64") (pintype "bidirectional"))
      (node (ref "U40") (pin "8") (pinfunction "GND_8") (pintype "bidirectional"))
    )
    (net (code "84") (name "DI0") (class "Default")
      (node (ref "J1") (pin "E1") (pinfunction "E1_E1") (pintype "passive"))
      (node (ref "U2") (pin "54") (pinfunction "B1_54") (pintype "bidirectional"))
    )
    (net (code "85") (name "DI1") (class "Default")
      (node (ref "J1") (pin "D2") (pinfunction "D2_D2") (pintype "passive"))
      (node (ref "U2") (pin "52") (pinfunction "B2_52") (pintype "bidirectional"))
    )
    (net (code "86") (name "DI2") (class "Default")
      (node (ref "J1") (pin "E3") (pinfunction "E3_E3") (pintype "passive"))
      (node (ref "U2") (pin "51") (pinfunction "B3_51") (pintype "bidirectional"))
    )
    (net (code "87") (name "DI3") (class "Default")
      (node (ref "J1") (pin "C3") (pinfunction "C3_C3") (pintype "passive"))
      (node (ref "U2") (pin "49") (pinfunction "B4_49") (pintype "bidirectional"))
    )
    (net (code "88") (name "DI4") (class "Default")
      (node (ref "J1") (pin "E4") (pinfunction "E4_E4") (pintype "passive"))
      (node (ref "U2") (pin "48") (pinfunction "B5_48") (pintype "bidirectional"))
    )
    (net (code "89") (name "DI5") (class "Default")
      (node (ref "J1") (pin "C4") (pinfunction "C4_C4") (pintype "passive"))
      (node (ref "U2") (pin "47") (pinfunction "B6_47") (pintype "bidirectional"))
    )
    (net (code "90") (name "DI6") (class "Default")
      (node (ref "J1") (pin "D5") (pinfunction "D5_D5") (pintype "passive"))
      (node (ref "U2") (pin "45") (pinfunction "B7_45") (pintype "bidirectional"))
    )
    (net (code "91") (name "DI7") (class "Default")
      (node (ref "J1") (pin "E6") (pinfunction "E6_E6") (pintype "passive"))
      (node (ref "U2") (pin "44") (pinfunction "B8_44") (pintype "bidirectional"))
    )
    (net (code "92") (name "DI8") (class "Default")
      (node (ref "J1") (pin "C6") (pinfunction "C6_C6") (pintype "passive"))
      (node (ref "U2") (pin "43") (pinfunction "B9_43") (pintype "bidirectional"))
    )
    (net (code "93") (name "DI9") (class "Default")
      (node (ref "J1") (pin "E7") (pinfunction "E7_E7") (pintype "passive"))
      (node (ref "U2") (pin "42") (pinfunction "B10_42") (pintype "bidirectional"))
    )
    (net (code "94") (name "DI10") (class "Default")
      (node (ref "J1") (pin "C7") (pinfunction "C7_C7") (pintype "passive"))
      (node (ref "U2") (pin "41") (pinfunction "B11_41") (pintype "bidirectional"))
    )
    (net (code "95") (name "DI11") (class "Default")
      (node (ref "J1") (pin "D8") (pinfunction "D8_D8") (pintype "passive"))
      (node (ref "U2") (pin "40") (pinfunction "B12_40") (pintype "bidirectional"))
    )
    (net (code "96") (name "DI12") (class "Default")
      (node (ref "J1") (pin "E9") (pinfunction "E9_E9") (pintype "passive"))
      (node (ref "U2") (pin "38") (pinfunction "B13_38") (pintype "bidirectional"))
    )
    (net (code "97") (name "DI13") (class "Default")
      (node (ref "J1") (pin "C9") (pinfunction "C9_C9") (pintype "passive"))
      (node (ref "U2") (pin "37") (pinfunction "B14_37") (pintype "bidirectional"))
    )
    (net (code "98") (name "DI14") (class "Default")
      (node (ref "J1") (pin "E10") (pinfunction "E10_E10") (pintype "passive"))
      (node (ref "U2") (pin "36") (pinfunction "B15_36") (pintype "bidirectional"))
    )
    (net (code "99") (name "DI15") (class "Default")
      (node (ref "J1") (pin "C10") (pinfunction "C10_C10") (pintype "passive"))
      (node (ref "U2") (pin "34") (pinfunction "B16_34") (pintype "bidirectional"))
    )
    (net (code "100") (name "DI16") (class "Default")
      (node (ref "J1") (pin "D11") (pinfunction "D11_D11") (pintype "passive"))
      (node (ref "U2") (pin "33") (pinfunction "B17_33") (pintype "bidirectional"))
    )
    (net (code "101") (name "DI17") (class "Default")
      (node (ref "J1") (pin "E12") (pinfunction "E12_E12") (pintype "passive"))
      (node (ref "U2") (pin "31") (pinfunction "B18_31") (pintype "bidirectional"))
    )
    (net (code "102") (name "DI18") (class "Default")
      (node (ref "J1") (pin "C12") (pinfunction "C12_C12") (pintype "passive"))
      (node (ref "U3") (pin "54") (pinfunction "B1_54") (pintype "bidirectional"))
    )
    (net (code "103") (name "DI19") (class "Default")
      (node (ref "J1") (pin "E13") (pinfunction "E13_E13") (pintype "passive"))
      (node (ref "U3") (pin "52") (pinfunction "B2_52") (pintype "bidirectional"))
    )
    (net (code "104") (name "DI20") (class "Default")
      (node (ref "J1") (pin "C13") (pinfunction "C13_C13") (pintype "passive"))
      (node (ref "U3") (pin "51") (pinfunction "B3_51") (pintype "bidirectional"))
    )
    (net (code "105") (name "DI21") (class "Default")
      (node (ref "J1") (pin "D14") (pinfunction "D14_D14") (pintype "passive"))
      (node (ref "U3") (pin "49") (pinfunction "B4_49") (pintype "bidirectional"))
    )
    (net (code "106") (name "DI22") (class "Default")
      (node (ref "J1") (pin "E15") (pinfunction "E15_E15") (pintype "passive"))
      (node (ref "U3") (pin "48") (pinfunction "B5_48") (pintype "bidirectional"))
    )
    (net (code "107") (name "DI23") (class "Default")
      (node (ref "J1") (pin "C15") (pinfunction "C15_C15") (pintype "passive"))
      (node (ref "U3") (pin "47") (pinfunction "B6_47") (pintype "bidirectional"))
    )
    (net (code "108") (name "DI24") (class "Default")
      (node (ref "J1") (pin "E16") (pinfunction "E16_E16") (pintype "passive"))
      (node (ref "U3") (pin "45") (pinfunction "B7_45") (pintype "bidirectional"))
    )
    (net (code "109") (name "DI25") (class "Default")
      (node (ref "J1") (pin "C16") (pinfunction "C16_C16") (pintype "passive"))
      (node (ref "U3") (pin "44") (pinfunction "B8_44") (pintype "bidirectional"))
    )
    (net (code "110") (name "DI26") (class "Default")
      (node (ref "J1") (pin "D17") (pinfunction "D17_D17") (pintype "passive"))
      (node (ref "U3") (pin "43") (pinfunction "B9_43") (pintype "bidirectional"))
    )
    (net (code "111") (name "DI27") (class "Default")
      (node (ref "J1") (pin "E18") (pinfunction "E18_E18") (pintype "passive"))
      (node (ref "U3") (pin "42") (pinfunction "B10_42") (pintype "bidirectional"))
    )
    (net (code "112") (name "DI28") (class "Default")
      (node (ref "J1") (pin "C18") (pinfunction "C18_C18") (pintype "passive"))
      (node (ref "U3") (pin "41") (pinfunction "B11_41") (pintype "bidirectional"))
    )
    (net (code "113") (name "DI29") (class "Default")
      (node (ref "J1") (pin "E19") (pinfunction "E19_E19") (pintype "passive"))
      (node (ref "U3") (pin "40") (pinfunction "B12_40") (pintype "bidirectional"))
    )
    (net (code "114") (name "DI30") (class "Default")
      (node (ref "J1") (pin "C19") (pinfunction "C19_C19") (pintype "passive"))
      (node (ref "U3") (pin "38") (pinfunction "B13_38") (pintype "bidirectional"))
    )
    (net (code "115") (name "DI31") (class "Default")
      (node (ref "J1") (pin "D20") (pinfunction "D20_D20") (pintype "passive"))
      (node (ref "U3") (pin "37") (pinfunction "B14_37") (pintype "bidirectional"))
    )
    (net (code "116") (name "DI32") (class "Default")
      (node (ref "J1") (pin "E21") (pinfunction "E21_E21") (pintype "passive"))
      (node (ref "U3") (pin "36") (pinfunction "B15_36") (pintype "bidirectional"))
    )
    (net (code "117") (name "DI33") (class "Default")
      (node (ref "J1") (pin "C21") (pinfunction "C21_C21") (pintype "passive"))
      (node (ref "U3") (pin "34") (pinfunction "B16_34") (pintype "bidirectional"))
    )
    (net (code "118") (name "DI34") (class "Default")
      (node (ref "J1") (pin "E22") (pinfunction "E22_E22") (pintype "passive"))
      (node (ref "U3") (pin "33") (pinfunction "B17_33") (pintype "bidirectional"))
    )
    (net (code "119") (name "DI35") (class "Default")
      (node (ref "J1") (pin "C22") (pinfunction "C22_C22") (pintype "passive"))
      (node (ref "U3") (pin "31") (pinfunction "B18_31") (pintype "bidirectional"))
    )
    (net (code "120") (name "DICS") (class "Default")
      (node (ref "ISO1") (pin "5") (pinfunction "A3_5") (pintype "bidirectional"))
      (node (ref "J1") (pin "A21") (pinfunction "A21_A21") (pintype "passive"))
      (node (ref "R2") (pin "2") (pinfunction "2_2") (pintype "passive"))
      (node (ref "U40") (pin "62") (pinfunction "1LEBA_62") (pintype "bidirectional"))
    )
    (net (code "121") (name "DO0") (class "Default")
      (node (ref "J1") (pin "A4") (pinfunction "A4_A4") (pintype "passive"))
      (node (ref "U40") (pin "37") (pinfunction "2B8_37") (pintype "bidirectional"))
    )
    (net (code "122") (name "DO1") (class "Default")
      (node (ref "J1") (pin "B5") (pinfunction "B5_B5") (pintype "passive"))
      (node (ref "U40") (pin "38") (pinfunction "2B7_38") (pintype "bidirectional"))
    )
    (net (code "123") (name "DO2") (class "Default")
      (node (ref "J1") (pin "A6") (pinfunction "A6_A6") (pintype "passive"))
      (node (ref "U40") (pin "40") (pinfunction "2B6_40") (pintype "bidirectional"))
    )
    (net (code "124") (name "DO3") (class "Default")
      (node (ref "J1") (pin "A7") (pinfunction "A7_A7") (pintype "passive"))
      (node (ref "U40") (pin "42") (pinfunction "2B5_42") (pintype "bidirectional"))
    )
    (net (code "125") (name "DO4") (class "Default")
      (node (ref "J1") (pin "B8") (pinfunction "B8_B8") (pintype "passive"))
      (node (ref "U40") (pin "43") (pinfunction "2B4_43") (pintype "bidirectional"))
    )
    (net (code "126") (name "DO5") (class "Default")
      (node (ref "J1") (pin "A9") (pinfunction "A9_A9") (pintype "passive"))
      (node (ref "U40") (pin "45") (pinfunction "2B3_45") (pintype "bidirectional"))
    )
    (net (code "127") (name "DO6") (class "Default")
      (node (ref "J1") (pin "B11") (pinfunction "B11_B11") (pintype "passive"))
      (node (ref "U40") (pin "46") (pinfunction "2B2_46") (pintype "bidirectional"))
    )
    (net (code "128") (name "DO7") (class "Default")
      (node (ref "J1") (pin "A12") (pinfunction "A12_A12") (pintype "passive"))
      (node (ref "U40") (pin "48") (pinfunction "2B1_48") (pintype "bidirectional"))
    )
    (net (code "129") (name "DOCLKI") (class "Default")
      (node (ref "J1") (pin "C1") (pinfunction "C1_C1") (pintype "passive"))
      (node (ref "U1") (pin "16") (pinfunction "1B_16") (pintype "bidirectional"))
    )
    (net (code "130") (name "DOCLKIB") (class "Default")
      (node (ref "ISO1") (pin "7") (pinfunction "A5_7") (pintype "bidirectional"))
      (node (ref "R3") (pin "2") (pinfunction "2_2") (pintype "passive"))
      (node (ref "U1") (pin "1") (pinfunction "1Y_1") (pintype "bidirectional"))
    )
    (net (code "131") (name "DOCLKO") (class "Default")
      (node (ref "J1") (pin "B2") (pinfunction "B2_B2") (pintype "passive"))
      (node (ref "U1") (pin "14") (pinfunction "2B_14") (pintype "bidirectional"))
    )
    (net (code "132") (name "DOCLKOB") (class "Default")
      (node (ref "ISO10") (pin "11") (pinfunction "B4_11") (pintype "bidirectional"))
      (node (ref "U1") (pin "9") (pinfunction "2A_9") (pintype "bidirectional"))
    )
    (net (code "133") (name "DOCS") (class "Default")
      (node (ref "ISO1") (pin "6") (pinfunction "A4_6") (pintype "bidirectional"))
      (node (ref "J1") (pin "A3") (pinfunction "A3_A3") (pintype "passive"))
      (node (ref "R1") (pin "2") (pinfunction "2_2") (pintype "passive"))
      (node (ref "U1") (pin "10") (pinfunction "2~{OEAB}_10") (pintype "bidirectional"))
      (node (ref "U1") (pin "20") (pinfunction "1~{OEBY}_20") (pintype "bidirectional"))
      (node (ref "U40") (pin "31") (pinfunction "2~{OEAB}_31") (pintype "bidirectional"))
    )
    (net (code "134") (name "DPWR") (class "Default")
      (node (ref "C110") (pin "2") (pinfunction "2_2") (pintype "passive"))
      (node (ref "C122") (pin "2") (pinfunction "2_2") (pintype "passive"))
      (node (ref "C134") (pin "2") (pinfunction "2_2") (pintype "passive"))
      (node (ref "C146") (pin "2") (pinfunction "2_2") (pintype "passive"))
      (node (ref "C158") (pin "2") (pinfunction "2_2") (pintype "passive"))
      (node (ref "C192") (pin "1") (pinfunction "1_1") (pintype "passive"))
      (node (ref "C194") (pin "1") (pinfunction "1_1") (pintype "passive"))
      (node (ref "C195") (pin "1") (pinfunction "1_1") (pintype "passive"))
      (node (ref "C196") (pin "1") (pinfunction "1_1") (pintype "passive"))
      (node (ref "C197") (pin "1") (pinfunction "1_1") (pintype "passive"))
      (node (ref "C198") (pin "1") (pinfunction "1_1") (pintype "passive"))
      (node (ref "C199") (pin "1") (pinfunction "1_1") (pintype "passive"))
      (node (ref "C200") (pin "1") (pinfunction "1_1") (pintype "passive"))
      (node (ref "C201") (pin "1") (pinfunction "1_1") (pintype "passive"))
      (node (ref "C26") (pin "2") (pinfunction "2_2") (pintype "passive"))
      (node (ref "C38") (pin "2") (pinfunction "2_2") (pintype "passive"))
      (node (ref "C50") (pin "2") (pinfunction "2_2") (pintype "passive"))
      (node (ref "C62") (pin "2") (pinfunction "2_2") (pintype "passive"))
      (node (ref "C74") (pin "2") (pinfunction "2_2") (pintype "passive"))
      (node (ref "C86") (pin "2") (pinfunction "2_2") (pintype "passive"))
      (node (ref "C98") (pin "2") (pinfunction "2_2") (pintype "passive"))
      (node (ref "ISO1") (pin "16") (pinfunction "VDD2_16") (pintype "bidirectional"))
      (node (ref "ISO11") (pin "16") (pinfunction "VDD2_16") (pintype "bidirectional"))
      (node (ref "ISO2") (pin "16") (pinfunction "VDD2_16") (pintype "bidirectional"))
      (node (ref "ISO3") (pin "16") (pinfunction "VDD2_16") (pintype "bidirectional"))
      (node (ref "ISO4") (pin "16") (pinfunction "VDD2_16") (pintype "bidirectional"))
      (node (ref "ISO5") (pin "16") (pinfunction "VDD2_16") (pintype "bidirectional"))
      (node (ref "ISO6") (pin "16") (pinfunction "VDD2_16") (pintype "bidirectional"))
      (node (ref "ISO7") (pin "16") (pinfunction "VDD2_16") (pintype "bidirectional"))
      (node (ref "ISO8") (pin "16") (pinfunction "VDD2_16") (pintype "bidirectional"))
      (node (ref "U10") (pin "10") (pinfunction "IOVCC_10") (pintype "power_in"))
      (node (ref "U10") (pin "6") (pinfunction "~{RESET}_6") (pintype "input"))
      (node (ref "U10") (pin "7") (pinfunction "~{CLR}_7") (pintype "input"))
      (node (ref "U10") (pin "9") (pinfunction "VCC_9") (pintype "power_in"))
      (node (ref "U12") (pin "10") (pinfunction "IOVCC_10") (pintype "power_in"))
      (node (ref "U12") (pin "6") (pinfunction "~{RESET}_6") (pintype "input"))
      (node (ref "U12") (pin "7") (pinfunction "~{CLR}_7") (pintype "input"))
      (node (ref "U12") (pin "9") (pinfunction "VCC_9") (pintype "power_in"))
      (node (ref "U14") (pin "10") (pinfunction "IOVCC_10") (pintype "power_in"))
      (node (ref "U14") (pin "6") (pinfunction "~{RESET}_6") (pintype "input"))
      (node (ref "U14") (pin "7") (pinfunction "~{CLR}_7") (pintype "input"))
      (node (ref "U14") (pin "9") (pinfunction "VCC_9") (pintype "power_in"))
      (node (ref "U16") (pin "10") (pinfunction "IOVCC_10") (pintype "power_in"))
      (node (ref "U16") (pin "6") (pinfunction "~{RESET}_6") (pintype "input"))
      (node (ref "U16") (pin "7") (pinfunction "~{CLR}_7") (pintype "input"))
      (node (ref "U16") (pin "9") (pinfunction "VCC_9") (pintype "power_in"))
      (node (ref "U18") (pin "10") (pinfunction "IOVCC_10") (pintype "power_in"))
      (node (ref "U18") (pin "6") (pinfunction "~{RESET}_6") (pintype "input"))
      (node (ref "U18") (pin "7") (pinfunction "~{CLR}_7") (pintype "input"))
      (node (ref "U18") (pin "9") (pinfunction "VCC_9") (pintype "power_in"))
      (node (ref "U20") (pin "10") (pinfunction "IOVCC_10") (pintype "power_in"))
      (node (ref "U20") (pin "6") (pinfunction "~{RESET}_6") (pintype "input"))
      (node (ref "U20") (pin "7") (pinfunction "~{CLR}_7") (pintype "input"))
      (node (ref "U20") (pin "9") (pinfunction "VCC_9") (pintype "power_in"))
      (node (ref "U22") (pin "10") (pinfunction "IOVCC_10") (pintype "power_in"))
      (node (ref "U22") (pin "6") (pinfunction "~{RESET}_6") (pintype "input"))
      (node (ref "U22") (pin "7") (pinfunction "~{CLR}_7") (pintype "input"))
      (node (ref "U22") (pin "9") (pinfunction "VCC_9") (pintype "power_in"))
      (node (ref "U24") (pin "10") (pinfunction "IOVCC_10") (pintype "power_in"))
      (node (ref "U24") (pin "6") (pinfunction "~{RESET}_6") (pintype "input"))
      (node (ref "U24") (pin "7") (pinfunction "~{CLR}_7") (pintype "input"))
      (node (ref "U24") (pin "9") (pinfunction "VCC_9") (pintype "power_in"))
      (node (ref "U26") (pin "10") (pinfunction "IOVCC_10") (pintype "power_in"))
      (node (ref "U26") (pin "6") (pinfunction "~{RESET}_6") (pintype "input"))
      (node (ref "U26") (pin "7") (pinfunction "~{CLR}_7") (pintype "input"))
      (node (ref "U26") (pin "9") (pinfunction "VCC_9") (pintype "power_in"))
      (node (ref "U29") (pin "2") (pinfunction "OUT_2_2") (pintype "output"))
      (node (ref "U29") (pin "4") (pinfunction "OUT_4") (pintype "output"))
      (node (ref "U4") (pin "10") (pinfunction "IOVCC_10") (pintype "power_in"))
      (node (ref "U4") (pin "6") (pinfunction "~{RESET}_6") (pintype "input"))
      (node (ref "U4") (pin "7") (pinfunction "~{CLR}_7") (pintype "input"))
      (node (ref "U4") (pin "9") (pinfunction "VCC_9") (pintype "power_in"))
      (node (ref "U6") (pin "10") (pinfunction "IOVCC_10") (pintype "power_in"))
      (node (ref "U6") (pin "6") (pinfunction "~{RESET}_6") (pintype "input"))
      (node (ref "U6") (pin "7") (pinfunction "~{CLR}_7") (pintype "input"))
      (node (ref "U6") (pin "9") (pinfunction "VCC_9") (pintype "power_in"))
      (node (ref "U8") (pin "10") (pinfunction "IOVCC_10") (pintype "power_in"))
      (node (ref "U8") (pin "6") (pinfunction "~{RESET}_6") (pintype "input"))
      (node (ref "U8") (pin "7") (pinfunction "~{CLR}_7") (pintype "input"))
      (node (ref "U8") (pin "9") (pinfunction "VCC_9") (pintype "power_in"))
    )
    (net (code "135") (name "DSCLK0") (class "Default")
      (node (ref "J1") (pin "B14") (pinfunction "B14_B14") (pintype "passive"))
      (node (ref "U40") (pin "51") (pinfunction "1B7_51") (pintype "bidirectional"))
    )
    (net (code "136") (name "DSCLK0B") (class "Default")
      (node (ref "U2") (pin "30") (pinfunction "CLKBA_30") (pintype "bidirectional"))
      (node (ref "U40") (pin "14") (pinfunction "1A7_14") (pintype "bidirectional"))
    )
    (net (code "137") (name "DSCLK1") (class "Default")
      (node (ref "J1") (pin "B20") (pinfunction "B20_B20") (pintype "passive"))
      (node (ref "U40") (pin "59") (pinfunction "1B1_59") (pintype "bidirectional"))
    )
    (net (code "138") (name "DSCLK1B") (class "Default")
      (node (ref "U3") (pin "30") (pinfunction "CLKBA_30") (pintype "bidirectional"))
      (node (ref "U40") (pin "4") (pinfunction "1A1_4") (pintype "bidirectional"))
    )
    (net (code "139") (name "DVCC") (class "Default")
      (node (ref "C1") (pin "1") (pinfunction "1_1") (pintype "passive"))
      (node (ref "C10") (pin "1") (pinfunction "1_1") (pintype "passive"))
      (node (ref "C13") (pin "1") (pinfunction "1_1") (pintype "passive"))
      (node (ref "C14") (pin "1") (pinfunction "1_1") (pintype "passive"))
      (node (ref "C15") (pin "1") (pinfunction "1_1") (pintype "passive"))
      (node (ref "C16") (pin "1") (pinfunction "1_1") (pintype "passive"))
      (node (ref "C17") (pin "1") (pinfunction "1_1") (pintype "passive"))
      (node (ref "C18") (pin "1") (pinfunction "1_1") (pintype "passive"))
      (node (ref "C19") (pin "1") (pinfunction "1_1") (pintype "passive"))
      (node (ref "C2") (pin "1") (pinfunction "1_1") (pintype "passive"))
      (node (ref "C20") (pin "1") (pinfunction "1_1") (pintype "passive"))
      (node (ref "C21") (pin "1") (pinfunction "1_1") (pintype "passive"))
      (node (ref "C22") (pin "1") (pinfunction "1_1") (pintype "passive"))
      (node (ref "C3") (pin "1") (pinfunction "1_1") (pintype "passive"))
      (node (ref "C4") (pin "1") (pinfunction "1_1") (pintype "passive"))
      (node (ref "C5") (pin "1") (pinfunction "1_1") (pintype "passive"))
      (node (ref "C6") (pin "1") (pinfunction "1_1") (pintype "passive"))
      (node (ref "C7") (pin "1") (pinfunction "1_1") (pintype "passive"))
      (node (ref "C8") (pin "1") (pinfunction "1_1") (pintype "passive"))
      (node (ref "C9") (pin "1") (pinfunction "1_1") (pintype "passive"))
      (node (ref "ISO1") (pin "1") (pinfunction "VDD1_1") (pintype "bidirectional"))
      (node (ref "ISO10") (pin "16") (pinfunction "VDD2_16") (pintype "bidirectional"))
      (node (ref "ISO11") (pin "1") (pinfunction "VDD1_1") (pintype "bidirectional"))
      (node (ref "ISO2") (pin "1") (pinfunction "VDD1_1") (pintype "bidirectional"))
      (node (ref "ISO3") (pin "1") (pinfunction "VDD1_1") (pintype "bidirectional"))
      (node (ref "ISO4") (pin "1") (pinfunction "VDD1_1") (pintype "bidirectional"))
      (node (ref "ISO5") (pin "1") (pinfunction "VDD1_1") (pintype "bidirectional"))
      (node (ref "ISO6") (pin "1") (pinfunction "VDD1_1") (pintype "bidirectional"))
      (node (ref "ISO7") (pin "1") (pinfunction "VDD1_1") (pintype "bidirectional"))
      (node (ref "ISO8") (pin "1") (pinfunction "VDD1_1") (pintype "bidirectional"))
      (node (ref "ISO9") (pin "16") (pinfunction "VDD2_16") (pintype "bidirectional"))
      (node (ref "J1") (pin "A11") (pinfunction "A11_A11") (pintype "passive"))
      (node (ref "J1") (pin "A14") (pinfunction "A14_A14") (pintype "passive"))
      (node (ref "J1") (pin "A17") (pinfunction "A17_A17") (pintype "passive"))
      (node (ref "J1") (pin "A2") (pinfunction "A2_A2") (pintype "passive"))
      (node (ref "J1") (pin "A20") (pinfunction "A20_A20") (pintype "passive"))
      (node (ref "J1") (pin "A22") (pinfunction "A22_A22") (pintype "passive"))
      (node (ref "J1") (pin "A23") (pinfunction "A23_A23") (pintype "passive"))
      (node (ref "J1") (pin "A25") (pinfunction "A25_A25") (pintype "passive"))
      (node (ref "J1") (pin "A5") (pinfunction "A5_A5") (pintype "passive"))
      (node (ref "J1") (pin "A8") (pinfunction "A8_A8") (pintype "passive"))
      (node (ref "J1") (pin "B1") (pinfunction "B1_B1") (pintype "passive"))
      (node (ref "J1") (pin "B12") (pinfunction "B12_B12") (pintype "passive"))
      (node (ref "J1") (pin "B13") (pinfunction "B13_B13") (pintype "passive"))
      (node (ref "J1") (pin "B15") (pinfunction "B15_B15") (pintype "passive"))
      (node (ref "J1") (pin "B16") (pinfunction "B16_B16") (pintype "passive"))
      (node (ref "J1") (pin "B18") (pinfunction "B18_B18") (pintype "passive"))
      (node (ref "J1") (pin "B19") (pinfunction "B19_B19") (pintype "passive"))
      (node (ref "J1") (pin "B21") (pinfunction "B21_B21") (pintype "passive"))
      (node (ref "J1") (pin "B22") (pinfunction "B22_B22") (pintype "passive"))
      (node (ref "J1") (pin "B24") (pinfunction "B24_B24") (pintype "passive"))
      (node (ref "J1") (pin "B25") (pinfunction "B25_B25") (pintype "passive"))
      (node (ref "J1") (pin "B3") (pinfunction "B3_B3") (pintype "passive"))
      (node (ref "J1") (pin "B4") (pinfunction "B4_B4") (pintype "passive"))
      (node (ref "J1") (pin "B6") (pinfunction "B6_B6") (pintype "passive"))
      (node (ref "J1") (pin "B7") (pinfunction "B7_B7") (pintype "passive"))
      (node (ref "J1") (pin "B9") (pinfunction "B9_B9") (pintype "passive"))
      (node (ref "U1") (pin "11") (pinfunction "BIAS_VCC_11") (pintype "bidirectional"))
      (node (ref "U1") (pin "18") (pinfunction "2~{OEBY}_18") (pintype "bidirectional"))
      (node (ref "U1") (pin "19") (pinfunction "2T/~{C}_19") (pintype "bidirectional"))
      (node (ref "U1") (pin "2") (pinfunction "1T/~{C}_2") (pintype "bidirectional"))
      (node (ref "U1") (pin "5") (pinfunction "1~{OEAB}_5") (pintype "bidirectional"))
      (node (ref "U1") (pin "6") (pinfunction "VCC_6") (pintype "bidirectional"))
      (node (ref "U1") (pin "7") (pinfunction "1A_7") (pintype "bidirectional"))
      (node (ref "U2") (pin "1") (pinfunction "~{OEAB}_1") (pintype "bidirectional"))
      (node (ref "U2") (pin "2") (pinfunction "LEAB_2") (pintype "bidirectional"))
      (node (ref "U2") (pin "22") (pinfunction "VCC_22") (pintype "bidirectional"))
      (node (ref "U2") (pin "50") (pinfunction "BIAS_VCC_50") (pintype "bidirectional"))
      (node (ref "U2") (pin "7") (pinfunction "VCC_7") (pintype "bidirectional"))
      (node (ref "U3") (pin "1") (pinfunction "~{OEAB}_1") (pintype "bidirectional"))
      (node (ref "U3") (pin "2") (pinfunction "LEAB_2") (pintype "bidirectional"))
      (node (ref "U3") (pin "22") (pinfunction "VCC_22") (pintype "bidirectional"))
      (node (ref "U3") (pin "50") (pinfunction "BIAS_VCC_50") (pintype "bidirectional"))
      (node (ref "U3") (pin "7") (pinfunction "VCC_7") (pintype "bidirectional"))
      (node (ref "U40") (pin "1") (pinfunction "1~{OEAB}_1") (pintype "bidirectional"))
      (node (ref "U40") (pin "15") (pinfunction "VCC_15") (pintype "bidirectional"))
      (node (ref "U40") (pin "28") (pinfunction "VCC_28") (pintype "bidirectional"))
      (node (ref "U40") (pin "3") (pinfunction "VCC_3") (pintype "bidirectional"))
      (node (ref "U40") (pin "32") (pinfunction "2~{OEBA}_32") (pintype "bidirectional"))
      (node (ref "U40") (pin "35") (pinfunction "2LEAB_35") (pintype "bidirectional"))
      (node (ref "U40") (pin "36") (pinfunction "BIAS_VCC_36") (pintype "bidirectional"))
      (node (ref "U40") (pin "50") (pinfunction "VCC_50") (pintype "bidirectional"))
    )
    (net (code "140") (name "DVTT") (class "Default")
      (node (ref "J1") (pin "A10") (pinfunction "A10_A10") (pintype "passive"))
      (node (ref "J1") (pin "B10") (pinfunction "B10_B10") (pintype "passive"))
      (node (ref "R6") (pin "2") (pinfunction "2_2") (pintype "passive"))
    )
    (net (code "141") (name "DX0") (class "Default")
      (node (ref "J1") (pin "A13") (pinfunction "A13_A13") (pintype "passive"))
      (node (ref "U40") (pin "49") (pinfunction "1B8_49") (pintype "bidirectional"))
    )
    (net (code "142") (name "DX1") (class "Default")
      (node (ref "J1") (pin "A15") (pinfunction "A15_A15") (pintype "passive"))
      (node (ref "U40") (pin "52") (pinfunction "1B6_52") (pintype "bidirectional"))
    )
    (net (code "143") (name "DX2") (class "Default")
      (node (ref "J1") (pin "A16") (pinfunction "A16_A16") (pintype "passive"))
      (node (ref "U40") (pin "54") (pinfunction "1B5_54") (pintype "bidirectional"))
    )
    (net (code "144") (name "DX3") (class "Default")
      (node (ref "J1") (pin "B17") (pinfunction "B17_B17") (pintype "passive"))
      (node (ref "U40") (pin "55") (pinfunction "1B4_55") (pintype "bidirectional"))
    )
    (net (code "145") (name "DX4") (class "Default")
      (node (ref "J1") (pin "A18") (pinfunction "A18_A18") (pintype "passive"))
      (node (ref "U40") (pin "56") (pinfunction "1B3_56") (pintype "bidirectional"))
    )
    (net (code "146") (name "DX5") (class "Default")
      (node (ref "J1") (pin "A19") (pinfunction "A19_A19") (pintype "passive"))
      (node (ref "U40") (pin "58") (pinfunction "1B2_58") (pintype "bidirectional"))
    )
    (net (code "147") (name "GND") (class "Default")
      (node (ref "C100") (pin "1") (pinfunction "1_1") (pintype "passive"))
      (node (ref "C101") (pin "2") (pinfunction "2_2") (pintype "passive"))
      (node (ref "C102") (pin "1") (pinfunction "1_1") (pintype "passive"))
      (node (ref "C103") (pin "1") (pinfunction "1_1") (pintype "passive"))
      (node (ref "C104") (pin "1") (pinfunction "1_1") (pintype "passive"))
      (node (ref "C105") (pin "1") (pinfunction "1_1") (pintype "passive"))
      (node (ref "C107") (pin "1") (pinfunction "1_1") (pintype "passive"))
      (node (ref "C108") (pin "1") (pinfunction "1_1") (pintype "passive"))
      (node (ref "C109") (pin "1") (pinfunction "1_1") (pintype "passive"))
      (node (ref "C11") (pin "1") (pinfunction "1_1") (pintype "passive"))
      (node (ref "C110") (pin "1") (pinfunction "1_1") (pintype "passive"))
      (node (ref "C111") (pin "1") (pinfunction "1_1") (pintype "passive"))
      (node (ref "C112") (pin "1") (pinfunction "1_1") (pintype "passive"))
      (node (ref "C113") (pin "2") (pinfunction "2_2") (pintype "passive"))
      (node (ref "C114") (pin "1") (pinfunction "1_1") (pintype "passive"))
      (node (ref "C115") (pin "1") (pinfunction "1_1") (pintype "passive"))
      (node (ref "C116") (pin "1") (pinfunction "1_1") (pintype "passive"))
      (node (ref "C117") (pin "1") (pinfunction "1_1") (pintype "passive"))
      (node (ref "C119") (pin "1") (pinfunction "1_1") (pintype "passive"))
      (node (ref "C12") (pin "1") (pinfunction "1_1") (pintype "passive"))
      (node (ref "C120") (pin "1") (pinfunction "1_1") (pintype "passive"))
      (node (ref "C121") (pin "1") (pinfunction "1_1") (pintype "passive"))
      (node (ref "C122") (pin "1") (pinfunction "1_1") (pintype "passive"))
      (node (ref "C123") (pin "1") (pinfunction "1_1") (pintype "passive"))
      (node (ref "C124") (pin "1") (pinfunction "1_1") (pintype "passive"))
      (node (ref "C125") (pin "2") (pinfunction "2_2") (pintype "passive"))
      (node (ref "C126") (pin "1") (pinfunction "1_1") (pintype "passive"))
      (node (ref "C127") (pin "1") (pinfunction "1_1") (pintype "passive"))
      (node (ref "C128") (pin "1") (pinfunction "1_1") (pintype "passive"))
      (node (ref "C129") (pin "1") (pinfunction "1_1") (pintype "passive"))
      (node (ref "C131") (pin "1") (pinfunction "1_1") (pintype "passive"))
      (node (ref "C132") (pin "1") (pinfunction "1_1") (pintype "passive"))
      (node (ref "C133") (pin "1") (pinfunction "1_1") (pintype "passive"))
      (node (ref "C134") (pin "1") (pinfunction "1_1") (pintype "passive"))
      (node (ref "C135") (pin "1") (pinfunction "1_1") (pintype "passive"))
      (node (ref "C136") (pin "1") (pinfunction "1_1") (pintype "passive"))
      (node (ref "C137") (pin "2") (pinfunction "2_2") (pintype "passive"))
      (node (ref "C138") (pin "1") (pinfunction "1_1") (pintype "passive"))
      (node (ref "C139") (pin "1") (pinfunction "1_1") (pintype "passive"))
      (node (ref "C140") (pin "1") (pinfunction "1_1") (pintype "passive"))
      (node (ref "C141") (pin "1") (pinfunction "1_1") (pintype "passive"))
      (node (ref "C143") (pin "1") (pinfunction "1_1") (pintype "passive"))
      (node (ref "C144") (pin "1") (pinfunction "1_1") (pintype "passive"))
      (node (ref "C145") (pin "1") (pinfunction "1_1") (pintype "passive"))
      (node (ref "C146") (pin "1") (pinfunction "1_1") (pintype "passive"))
      (node (ref "C147") (pin "1") (pinfunction "1_1") (pintype "passive"))
      (node (ref "C148") (pin "1") (pinfunction "1_1") (pintype "passive"))
      (node (ref "C149") (pin "2") (pinfunction "2_2") (pintype "passive"))
      (node (ref "C150") (pin "1") (pinfunction "1_1") (pintype "passive"))
      (node (ref "C151") (pin "1") (pinfunction "1_1") (pintype "passive"))
      (node (ref "C152") (pin "1") (pinfunction "1_1") (pintype "passive"))
      (node (ref "C153") (pin "1") (pinfunction "1_1") (pintype "passive"))
      (node (ref "C155") (pin "1") (pinfunction "1_1") (pintype "passive"))
      (node (ref "C156") (pin "1") (pinfunction "1_1") (pintype "passive"))
      (node (ref "C157") (pin "1") (pinfunction "1_1") (pintype "passive"))
      (node (ref "C158") (pin "1") (pinfunction "1_1") (pintype "passive"))
      (node (ref "C159") (pin "1") (pinfunction "1_1") (pintype "passive"))
      (node (ref "C160") (pin "1") (pinfunction "1_1") (pintype "passive"))
      (node (ref "C161") (pin "2") (pinfunction "2_2") (pintype "passive"))
      (node (ref "C162") (pin "1") (pinfunction "1_1") (pintype "passive"))
      (node (ref "C163") (pin "1") (pinfunction "1_1") (pintype "passive"))
      (node (ref "C164") (pin "1") (pinfunction "1_1") (pintype "passive"))
      (node (ref "C165") (pin "1") (pinfunction "1_1") (pintype "passive"))
      (node (ref "C167") (pin "1") (pinfunction "1_1") (pintype "passive"))
      (node (ref "C168") (pin "2") (pinfunction "2_2") (pintype "passive"))
      (node (ref "C169") (pin "2") (pinfunction "2_2") (pintype "passive"))
      (node (ref "C170") (pin "2") (pinfunction "2_2") (pintype "passive"))
      (node (ref "C171") (pin "2") (pinfunction "2_2") (pintype "passive"))
      (node (ref "C172") (pin "2") (pinfunction "2_2") (pintype "passive"))
      (node (ref "C173") (pin "2") (pinfunction "2_2") (pintype "passive"))
      (node (ref "C174") (pin "2") (pinfunction "2_2") (pintype "passive"))
      (node (ref "C175") (pin "2") (pinfunction "2_2") (pintype "passive"))
      (node (ref "C176") (pin "2") (pinfunction "2_2") (pintype "passive"))
      (node (ref "C177") (pin "2") (pinfunction "2_2") (pintype "passive"))
      (node (ref "C178") (pin "2") (pinfunction "2_2") (pintype "passive"))
      (node (ref "C179") (pin "2") (pinfunction "2_2") (pintype "passive"))
      (node (ref "C180") (pin "2") (pinfunction "2_2") (pintype "passive"))
      (node (ref "C181") (pin "2") (pinfunction "2_2") (pintype "passive"))
      (node (ref "C182") (pin "2") (pinfunction "2_2") (pintype "passive"))
      (node (ref "C183") (pin "2") (pinfunction "2_2") (pintype "passive"))
      (node (ref "C184") (pin "2") (pinfunction "2_2") (pintype "passive"))
      (node (ref "C185") (pin "2") (pinfunction "2_2") (pintype "passive"))
      (node (ref "C186") (pin "2") (pinfunction "2_2") (pintype "passive"))
      (node (ref "C187") (pin "2") (pinfunction "2_2") (pintype "passive"))
      (node (ref "C188") (pin "2") (pinfunction "2_2") (pintype "passive"))
      (node (ref "C189") (pin "2") (pinfunction "2_2") (pintype "passive"))
      (node (ref "C190") (pin "2") (pinfunction "2_2") (pintype "passive"))
      (node (ref "C191") (pin "2") (pinfunction "2_2") (pintype "passive"))
      (node (ref "C192") (pin "2") (pinfunction "2_2") (pintype "passive"))
      (node (ref "C193") (pin "2") (pinfunction "2_2") (pintype "passive"))
      (node (ref "C194") (pin "2") (pinfunction "2_2") (pintype "passive"))
      (node (ref "C195") (pin "2") (pinfunction "2_2") (pintype "passive"))
      (node (ref "C196") (pin "2") (pinfunction "2_2") (pintype "passive"))
      (node (ref "C197") (pin "2") (pinfunction "2_2") (pintype "passive"))
      (node (ref "C198") (pin "2") (pinfunction "2_2") (pintype "passive"))
      (node (ref "C199") (pin "2") (pinfunction "2_2") (pintype "passive"))
      (node (ref "C200") (pin "2") (pinfunction "2_2") (pintype "passive"))
      (node (ref "C201") (pin "2") (pinfunction "2_2") (pintype "passive"))
      (node (ref "C26") (pin "1") (pinfunction "1_1") (pintype "passive"))
      (node (ref "C27") (pin "1") (pinfunction "1_1") (pintype "passive"))
      (node (ref "C28") (pin "1") (pinfunction "1_1") (pintype "passive"))
      (node (ref "C29") (pin "2") (pinfunction "2_2") (pintype "passive"))
      (node (ref "C30") (pin "1") (pinfunction "1_1") (pintype "passive"))
      (node (ref "C31") (pin "1") (pinfunction "1_1") (pintype "passive"))
      (node (ref "C32") (pin "1") (pinfunction "1_1") (pintype "passive"))
      (node (ref "C33") (pin "1") (pinfunction "1_1") (pintype "passive"))
      (node (ref "C35") (pin "1") (pinfunction "1_1") (pintype "passive"))
      (node (ref "C36") (pin "1") (pinfunction "1_1") (pintype "passive"))
      (node (ref "C37") (pin "1") (pinfunction "1_1") (pintype "passive"))
      (node (ref "C38") (pin "1") (pinfunction "1_1") (pintype "passive"))
      (node (ref "C39") (pin "1") (pinfunction "1_1") (pintype "passive"))
      (node (ref "C40") (pin "1") (pinfunction "1_1") (pintype "passive"))
      (node (ref "C41") (pin "2") (pinfunction "2_2") (pintype "passive"))
      (node (ref "C42") (pin "1") (pinfunction "1_1") (pintype "passive"))
      (node (ref "C43") (pin "1") (pinfunction "1_1") (pintype "passive"))
      (node (ref "C44") (pin "1") (pinfunction "1_1") (pintype "passive"))
      (node (ref "C45") (pin "1") (pinfunction "1_1") (pintype "passive"))
      (node (ref "C47") (pin "1") (pinfunction "1_1") (pintype "passive"))
      (node (ref "C48") (pin "1") (pinfunction "1_1") (pintype "passive"))
      (node (ref "C49") (pin "1") (pinfunction "1_1") (pintype "passive"))
      (node (ref "C50") (pin "1") (pinfunction "1_1") (pintype "passive"))
      (node (ref "C51") (pin "1") (pinfunction "1_1") (pintype "passive"))
      (node (ref "C52") (pin "1") (pinfunction "1_1") (pintype "passive"))
      (node (ref "C53") (pin "2") (pinfunction "2_2") (pintype "passive"))
      (node (ref "C54") (pin "1") (pinfunction "1_1") (pintype "passive"))
      (node (ref "C55") (pin "1") (pinfunction "1_1") (pintype "passive"))
      (node (ref "C56") (pin "1") (pinfunction "1_1") (pintype "passive"))
      (node (ref "C57") (pin "1") (pinfunction "1_1") (pintype "passive"))
      (node (ref "C59") (pin "1") (pinfunction "1_1") (pintype "passive"))
      (node (ref "C60") (pin "1") (pinfunction "1_1") (pintype "passive"))
      (node (ref "C61") (pin "1") (pinfunction "1_1") (pintype "passive"))
      (node (ref "C62") (pin "1") (pinfunction "1_1") (pintype "passive"))
      (node (ref "C63") (pin "1") (pinfunction "1_1") (pintype "passive"))
      (node (ref "C64") (pin "1") (pinfunction "1_1") (pintype "passive"))
      (node (ref "C65") (pin "2") (pinfunction "2_2") (pintype "passive"))
      (node (ref "C66") (pin "1") (pinfunction "1_1") (pintype "passive"))
      (node (ref "C67") (pin "1") (pinfunction "1_1") (pintype "passive"))
      (node (ref "C68") (pin "1") (pinfunction "1_1") (pintype "passive"))
      (node (ref "C69") (pin "1") (pinfunction "1_1") (pintype "passive"))
      (node (ref "C71") (pin "1") (pinfunction "1_1") (pintype "passive"))
      (node (ref "C72") (pin "1") (pinfunction "1_1") (pintype "passive"))
      (node (ref "C73") (pin "1") (pinfunction "1_1") (pintype "passive"))
      (node (ref "C74") (pin "1") (pinfunction "1_1") (pintype "passive"))
      (node (ref "C75") (pin "1") (pinfunction "1_1") (pintype "passive"))
      (node (ref "C76") (pin "1") (pinfunction "1_1") (pintype "passive"))
      (node (ref "C77") (pin "2") (pinfunction "2_2") (pintype "passive"))
      (node (ref "C78") (pin "1") (pinfunction "1_1") (pintype "passive"))
      (node (ref "C79") (pin "1") (pinfunction "1_1") (pintype "passive"))
      (node (ref "C80") (pin "1") (pinfunction "1_1") (pintype "passive"))
      (node (ref "C81") (pin "1") (pinfunction "1_1") (pintype "passive"))
      (node (ref "C83") (pin "1") (pinfunction "1_1") (pintype "passive"))
      (node (ref "C84") (pin "1") (pinfunction "1_1") (pintype "passive"))
      (node (ref "C85") (pin "1") (pinfunction "1_1") (pintype "passive"))
      (node (ref "C86") (pin "1") (pinfunction "1_1") (pintype "passive"))
      (node (ref "C87") (pin "1") (pinfunction "1_1") (pintype "passive"))
      (node (ref "C88") (pin "1") (pinfunction "1_1") (pintype "passive"))
      (node (ref "C89") (pin "2") (pinfunction "2_2") (pintype "passive"))
      (node (ref "C90") (pin "1") (pinfunction "1_1") (pintype "passive"))
      (node (ref "C91") (pin "1") (pinfunction "1_1") (pintype "passive"))
      (node (ref "C92") (pin "1") (pinfunction "1_1") (pintype "passive"))
      (node (ref "C93") (pin "1") (pinfunction "1_1") (pintype "passive"))
      (node (ref "C95") (pin "1") (pinfunction "1_1") (pintype "passive"))
      (node (ref "C96") (pin "1") (pinfunction "1_1") (pintype "passive"))
      (node (ref "C97") (pin "1") (pinfunction "1_1") (pintype "passive"))
      (node (ref "C98") (pin "1") (pinfunction "1_1") (pintype "passive"))
      (node (ref "C99") (pin "1") (pinfunction "1_1") (pintype "passive"))
      (node (ref "ISO1") (pin "15") (pinfunction "GND2_15") (pintype "bidirectional"))
      (node (ref "ISO1") (pin "9") (pinfunction "GND2_9") (pintype "bidirectional"))
      (node (ref "ISO11") (pin "15") (pinfunction "GND2_15") (pintype "bidirectional"))
      (node (ref "ISO11") (pin "9") (pinfunction "GND2_9") (pintype "bidirectional"))
      (node (ref "ISO2") (pin "15") (pinfunction "GND2_15") (pintype "bidirectional"))
      (node (ref "ISO2") (pin "9") (pinfunction "GND2_9") (pintype "bidirectional"))
      (node (ref "ISO3") (pin "15") (pinfunction "GND2_15") (pintype "bidirectional"))
      (node (ref "ISO3") (pin "9") (pinfunction "GND2_9") (pintype "bidirectional"))
      (node (ref "ISO4") (pin "15") (pinfunction "GND2_15") (pintype "bidirectional"))
      (node (ref "ISO4") (pin "9") (pinfunction "GND2_9") (pintype "bidirectional"))
      (node (ref "ISO5") (pin "15") (pinfunction "GND2_15") (pintype "bidirectional"))
      (node (ref "ISO5") (pin "9") (pinfunction "GND2_9") (pintype "bidirectional"))
      (node (ref "ISO6") (pin "15") (pinfunction "GND2_15") (pintype "bidirectional"))
      (node (ref "ISO6") (pin "9") (pinfunction "GND2_9") (pintype "bidirectional"))
      (node (ref "ISO7") (pin "15") (pinfunction "GND2_15") (pintype "bidirectional"))
      (node (ref "ISO7") (pin "9") (pinfunction "GND2_9") (pintype "bidirectional"))
      (node (ref "ISO8") (pin "15") (pinfunction "GND2_15") (pintype "bidirectional"))
      (node (ref "ISO8") (pin "9") (pinfunction "GND2_9") (pintype "bidirectional"))
      (node (ref "J1") (pin "A26") (pinfunction "A26_A26") (pintype "passive"))
      (node (ref "J1") (pin "A30") (pinfunction "A30_A30") (pintype "passive"))
      (node (ref "J1") (pin "A31") (pinfunction "A31_A31") (pintype "passive"))
      (node (ref "J1") (pin "A32") (pinfunction "A32_A32") (pintype "passive"))
      (node (ref "J1") (pin "A33") (pinfunction "A33_A33") (pintype "passive"))
      (node (ref "J1") (pin "A38") (pinfunction "A38_A38") (pintype "passive"))
      (node (ref "J1") (pin "A39") (pinfunction "A39_A39") (pintype "passive"))
      (node (ref "J1") (pin "A40") (pinfunction "A40_A40") (pintype "passive"))
      (node (ref "J1") (pin "B26") (pinfunction "B26_B26") (pintype "passive"))
      (node (ref "J1") (pin "B31") (pinfunction "B31_B31") (pintype "passive"))
      (node (ref "J1") (pin "B33") (pinfunction "B33_B33") (pintype "passive"))
      (node (ref "J1") (pin "B38") (pinfunction "B38_B38") (pintype "passive"))
      (node (ref "J1") (pin "B40") (pinfunction "B40_B40") (pintype "passive"))
      (node (ref "J1") (pin "C26") (pinfunction "C26_C26") (pintype "passive"))
      (node (ref "J1") (pin "C31") (pinfunction "C31_C31") (pintype "passive"))
      (node (ref "J1") (pin "C32") (pinfunction "C32_C32") (pintype "passive"))
      (node (ref "J1") (pin "C33") (pinfunction "C33_C33") (pintype "passive"))
      (node (ref "J1") (pin "C34") (pinfunction "C34_C34") (pintype "passive"))
      (node (ref "J1") (pin "C35") (pinfunction "C35_C35") (pintype "passive"))
      (node (ref "J1") (pin "C36") (pinfunction "C36_C36") (pintype "passive"))
      (node (ref "J1") (pin "C37") (pinfunction "C37_C37") (pintype "passive"))
      (node (ref "J1") (pin "C38") (pinfunction "C38_C38") (pintype "passive"))
      (node (ref "J1") (pin "C39") (pinfunction "C39_C39") (pintype "passive"))
      (node (ref "J1") (pin "C40") (pinfunction "C40_C40") (pintype "passive"))
      (node (ref "J1") (pin "C41") (pinfunction "C41_C41") (pintype "passive"))
      (node (ref "J1") (pin "C42") (pinfunction "C42_C42") (pintype "passive"))
      (node (ref "J1") (pin "C43") (pinfunction "C43_C43") (pintype "passive"))
      (node (ref "J1") (pin "C44") (pinfunction "C44_C44") (pintype "passive"))
      (node (ref "J1") (pin "D26") (pinfunction "D26_D26") (pintype "passive"))
      (node (ref "J1") (pin "D31") (pinfunction "D31_D31") (pintype "passive"))
      (node (ref "J1") (pin "D33") (pinfunction "D33_D33") (pintype "passive"))
      (node (ref "J1") (pin "D38") (pinfunction "D38_D38") (pintype "passive"))
      (node (ref "J1") (pin "D40") (pinfunction "D40_D40") (pintype "passive"))
      (node (ref "J1") (pin "E26") (pinfunction "E26_E26") (pintype "passive"))
      (node (ref "J1") (pin "E30") (pinfunction "E30_E30") (pintype "passive"))
      (node (ref "J1") (pin "E31") (pinfunction "E31_E31") (pintype "passive"))
      (node (ref "J1") (pin "E32") (pinfunction "E32_E32") (pintype "passive"))
      (node (ref "J1") (pin "E33") (pinfunction "E33_E33") (pintype "passive"))
      (node (ref "J1") (pin "E38") (pinfunction "E38_E38") (pintype "passive"))
      (node (ref "J1") (pin "E39") (pinfunction "E39_E39") (pintype "passive"))
      (node (ref "J1") (pin "E40") (pinfunction "E40_E40") (pintype "passive"))
      (node (ref "R19") (pin "2") (pinfunction "2_2") (pintype "passive"))
      (node (ref "R21") (pin "1") (pinfunction "1_1") (pintype "passive"))
      (node (ref "R24") (pin "1") (pinfunction "1_1") (pintype "passive"))
      (node (ref "R25") (pin "2") (pinfunction "2_2") (pintype "passive"))
      (node (ref "R28") (pin "1") (pinfunction "1_1") (pintype "passive"))
      (node (ref "R29") (pin "2") (pinfunction "2_2") (pintype "passive"))
      (node (ref "U10") (pin "15") (pinfunction "DGND_15") (pintype "passive"))
      (node (ref "U10") (pin "19") (pinfunction "AGND_19") (pintype "passive"))
      (node (ref "U11") (pin "5") (pinfunction "+IN_B_5") (pintype "input"))
      (node (ref "U12") (pin "15") (pinfunction "DGND_15") (pintype "passive"))
      (node (ref "U12") (pin "19") (pinfunction "AGND_19") (pintype "passive"))
      (node (ref "U13") (pin "5") (pinfunction "+IN_B_5") (pintype "input"))
      (node (ref "U14") (pin "15") (pinfunction "DGND_15") (pintype "passive"))
      (node (ref "U14") (pin "19") (pinfunction "AGND_19") (pintype "passive"))
      (node (ref "U15") (pin "5") (pinfunction "+IN_B_5") (pintype "input"))
      (node (ref "U16") (pin "15") (pinfunction "DGND_15") (pintype "passive"))
      (node (ref "U16") (pin "19") (pinfunction "AGND_19") (pintype "passive"))
      (node (ref "U17") (pin "5") (pinfunction "+IN_B_5") (pintype "input"))
      (node (ref "U18") (pin "15") (pinfunction "DGND_15") (pintype "passive"))
      (node (ref "U18") (pin "19") (pinfunction "AGND_19") (pintype "passive"))
      (node (ref "U19") (pin "5") (pinfunction "+IN_B_5") (pintype "input"))
      (node (ref "U20") (pin "15") (pinfunction "DGND_15") (pintype "passive"))
      (node (ref "U20") (pin "19") (pinfunction "AGND_19") (pintype "passive"))
      (node (ref "U21") (pin "5") (pinfunction "+IN_B_5") (pintype "input"))
      (node (ref "U22") (pin "15") (pinfunction "DGND_15") (pintype "passive"))
      (node (ref "U22") (pin "19") (pinfunction "AGND_19") (pintype "passive"))
      (node (ref "U23") (pin "5") (pinfunction "+IN_B_5") (pintype "input"))
      (node (ref "U24") (pin "15") (pinfunction "DGND_15") (pintype "passive"))
      (node (ref "U24") (pin "19") (pinfunction "AGND_19") (pintype "passive"))
      (node (ref "U25") (pin "5") (pinfunction "+IN_B_5") (pintype "input"))
      (node (ref "U26") (pin "15") (pinfunction "DGND_15") (pintype "passive"))
      (node (ref "U26") (pin "19") (pinfunction "AGND_19") (pintype "passive"))
      (node (ref "U27") (pin "5") (pinfunction "+IN_B_5") (pintype "input"))
      (node (ref "U28") (pin "3") (pinfunction "GND_3") (pintype "passive"))
      (node (ref "U29") (pin "1") (pinfunction "GND_1") (pintype "passive"))
      (node (ref "U4") (pin "15") (pinfunction "DGND_15") (pintype "passive"))
      (node (ref "U4") (pin "19") (pinfunction "AGND_19") (pintype "passive"))
      (node (ref "U5") (pin "5") (pinfunction "+IN_B_5") (pintype "input"))
      (node (ref "U6") (pin "15") (pinfunction "DGND_15") (pintype "passive"))
      (node (ref "U6") (pin "19") (pinfunction "AGND_19") (pintype "passive"))
      (node (ref "U7") (pin "5") (pinfunction "+IN_B_5") (pintype "input"))
      (node (ref "U8") (pin "15") (pinfunction "DGND_15") (pintype "passive"))
      (node (ref "U8") (pin "19") (pinfunction "AGND_19") (pintype "passive"))
      (node (ref "U9") (pin "5") (pinfunction "+IN_B_5") (pintype "input"))
      (node (ref "X1") (pin "1") (pinfunction "1_1") (pintype "passive"))
      (node (ref "X1") (pin "11") (pinfunction "11_11") (pintype "passive"))
      (node (ref "X1") (pin "13") (pinfunction "13_13") (pintype "passive"))
      (node (ref "X1") (pin "15") (pinfunction "15_15") (pintype "passive"))
      (node (ref "X1") (pin "16") (pinfunction "16_16") (pintype "passive"))
      (node (ref "X1") (pin "17") (pinfunction "17_17") (pintype "passive"))
      (node (ref "X1") (pin "18") (pinfunction "18_18") (pintype "passive"))
      (node (ref "X1") (pin "19") (pinfunction "19_19") (pintype "passive"))
      (node (ref "X1") (pin "2") (pinfunction "2_2") (pintype "passive"))
      (node (ref "X1") (pin "20") (pinfunction "20_20") (pintype "passive"))
      (node (ref "X1") (pin "21") (pinfunction "21_21") (pintype "passive"))
      (node (ref "X1") (pin "22") (pinfunction "22_22") (pintype "passive"))
      (node (ref "X1") (pin "23") (pinfunction "23_23") (pintype "passive"))
      (node (ref "X1") (pin "24") (pinfunction "24_24") (pintype "passive"))
      (node (ref "X1") (pin "25") (pinfunction "25_25") (pintype "passive"))
      (node (ref "X1") (pin "26") (pinfunction "26_26") (pintype "passive"))
      (node (ref "X1") (pin "27") (pinfunction "27_27") (pintype "passive"))
      (node (ref "X1") (pin "28") (pinfunction "28_28") (pintype "passive"))
      (node (ref "X1") (pin "29") (pinfunction "29_29") (pintype "passive"))
      (node (ref "X1") (pin "3") (pinfunction "3_3") (pintype "passive"))
      (node (ref "X1") (pin "30") (pinfunction "30_30") (pintype "passive"))
      (node (ref "X1") (pin "31") (pinfunction "31_31") (pintype "passive"))
      (node (ref "X1") (pin "32") (pinfunction "32_32") (pintype "passive"))
      (node (ref "X1") (pin "33") (pinfunction "33_33") (pintype "passive"))
      (node (ref "X1") (pin "34") (pinfunction "34_34") (pintype "passive"))
      (node (ref "X1") (pin "35") (pinfunction "35_35") (pintype "passive"))
      (node (ref "X1") (pin "36") (pinfunction "36_36") (pintype "passive"))
      (node (ref "X1") (pin "38") (pinfunction "38_38") (pintype "passive"))
      (node (ref "X1") (pin "40") (pinfunction "40_40") (pintype "passive"))
      (node (ref "X1") (pin "42") (pinfunction "42_42") (pintype "passive"))
      (node (ref "X1") (pin "44") (pinfunction "44_44") (pintype "passive"))
      (node (ref "X1") (pin "46") (pinfunction "46_46") (pintype "passive"))
      (node (ref "X1") (pin "48") (pinfunction "48_48") (pintype "passive"))
      (node (ref "X1") (pin "49") (pinfunction "49_49") (pintype "passive"))
      (node (ref "X1") (pin "5") (pinfunction "5_5") (pintype "passive"))
      (node (ref "X1") (pin "50") (pinfunction "50_50") (pintype "passive"))
      (node (ref "X1") (pin "7") (pinfunction "7_7") (pintype "passive"))
      (node (ref "X1") (pin "9") (pinfunction "9_9") (pintype "passive"))
    )
    (net (code "148") (name "INV_1") (class "Default")
      (node (ref "C34") (pin "1") (pinfunction "1_1") (pintype "passive"))
      (node (ref "U30") (pin "6") (pinfunction "-INB_6") (pintype "input"))
      (node (ref "U4") (pin "1") (pinfunction "INV_1") (pintype "input"))
    )
    (net (code "149") (name "INV_2") (class "Default")
      (node (ref "C46") (pin "1") (pinfunction "1_1") (pintype "passive"))
      (node (ref "U31") (pin "6") (pinfunction "-INB_6") (pintype "input"))
      (node (ref "U6") (pin "1") (pinfunction "INV_1") (pintype "input"))
    )
    (net (code "150") (name "INV_3") (class "Default")
      (node (ref "C58") (pin "1") (pinfunction "1_1") (pintype "passive"))
      (node (ref "U32") (pin "6") (pinfunction "-INB_6") (pintype "input"))
      (node (ref "U8") (pin "1") (pinfunction "INV_1") (pintype "input"))
    )
    (net (code "151") (name "INV_4") (class "Default")
      (node (ref "C70") (pin "1") (pinfunction "1_1") (pintype "passive"))
      (node (ref "U10") (pin "1") (pinfunction "INV_1") (pintype "input"))
      (node (ref "U33") (pin "6") (pinfunction "-INB_6") (pintype "input"))
    )
    (net (code "152") (name "INV_5") (class "Default")
      (node (ref "C82") (pin "1") (pinfunction "1_1") (pintype "passive"))
      (node (ref "U12") (pin "1") (pinfunction "INV_1") (pintype "input"))
      (node (ref "U34") (pin "6") (pinfunction "-INB_6") (pintype "input"))
    )
    (net (code "153") (name "INV_6") (class "Default")
      (node (ref "C94") (pin "1") (pinfunction "1_1") (pintype "passive"))
      (node (ref "U14") (pin "1") (pinfunction "INV_1") (pintype "input"))
      (node (ref "U35") (pin "6") (pinfunction "-INB_6") (pintype "input"))
    )
    (net (code "154") (name "INV_7") (class "Default")
      (node (ref "C106") (pin "1") (pinfunction "1_1") (pintype "passive"))
      (node (ref "U16") (pin "1") (pinfunction "INV_1") (pintype "input"))
      (node (ref "U30") (pin "2") (pinfunction "-INA_2") (pintype "input"))
    )
    (net (code "155") (name "INV_8") (class "Default")
      (node (ref "C118") (pin "1") (pinfunction "1_1") (pintype "passive"))
      (node (ref "U18") (pin "1") (pinfunction "INV_1") (pintype "input"))
      (node (ref "U31") (pin "2") (pinfunction "-INA_2") (pintype "input"))
    )
    (net (code "156") (name "INV_9") (class "Default")
      (node (ref "C130") (pin "1") (pinfunction "1_1") (pintype "passive"))
      (node (ref "U20") (pin "1") (pinfunction "INV_1") (pintype "input"))
      (node (ref "U32") (pin "2") (pinfunction "-INA_2") (pintype "input"))
    )
    (net (code "157") (name "INV_10") (class "Default")
      (node (ref "C142") (pin "1") (pinfunction "1_1") (pintype "passive"))
      (node (ref "U22") (pin "1") (pinfunction "INV_1") (pintype "input"))
      (node (ref "U33") (pin "2") (pinfunction "-INA_2") (pintype "input"))
    )
    (net (code "158") (name "INV_11") (class "Default")
      (node (ref "C154") (pin "1") (pinfunction "1_1") (pintype "passive"))
      (node (ref "U24") (pin "1") (pinfunction "INV_1") (pintype "input"))
      (node (ref "U34") (pin "2") (pinfunction "-INA_2") (pintype "input"))
    )
    (net (code "159") (name "INV_12") (class "Default")
      (node (ref "C166") (pin "1") (pinfunction "1_1") (pintype "passive"))
      (node (ref "U26") (pin "1") (pinfunction "INV_1") (pintype "input"))
      (node (ref "U35") (pin "2") (pinfunction "-INA_2") (pintype "input"))
    )
    (net (code "160") (name "LDAC") (class "Default")
      (node (ref "ISO11") (pin "10") (pinfunction "B5_10") (pintype "bidirectional"))
      (node (ref "U10") (pin "8") (pinfunction "~{LDAC}_8") (pintype "input"))
      (node (ref "U12") (pin "8") (pinfunction "~{LDAC}_8") (pintype "input"))
      (node (ref "U14") (pin "8") (pinfunction "~{LDAC}_8") (pintype "input"))
      (node (ref "U16") (pin "8") (pinfunction "~{LDAC}_8") (pintype "input"))
      (node (ref "U18") (pin "8") (pinfunction "~{LDAC}_8") (pintype "input"))
      (node (ref "U20") (pin "8") (pinfunction "~{LDAC}_8") (pintype "input"))
      (node (ref "U22") (pin "8") (pinfunction "~{LDAC}_8") (pintype "input"))
      (node (ref "U24") (pin "8") (pinfunction "~{LDAC}_8") (pintype "input"))
      (node (ref "U26") (pin "8") (pinfunction "~{LDAC}_8") (pintype "input"))
      (node (ref "U4") (pin "8") (pinfunction "~{LDAC}_8") (pintype "input"))
      (node (ref "U6") (pin "8") (pinfunction "~{LDAC}_8") (pintype "input"))
      (node (ref "U8") (pin "8") (pinfunction "~{LDAC}_8") (pintype "input"))
    )
    (net (code "161") (name "Net-(U4-VREFNF)") (class "Default")
      (node (ref "U4") (pin "16") (pinfunction "VREFNF_16") (pintype "input"))
      (node (ref "U5") (pin "7") (pinfunction "OUT_B_7") (pintype "output"))
    )
    (net (code "162") (name "Net-(U4-VREFNS)") (class "Default")
      (node (ref "U4") (pin "17") (pinfunction "VREFNS_17") (pintype "input"))
      (node (ref "U5") (pin "6") (pinfunction "-IN_B_6") (pintype "input"))
    )
    (net (code "163") (name "Net-(U4-VREFPF)") (class "Default")
      (node (ref "U4") (pin "4") (pinfunction "VREFPF_4") (pintype "input"))
      (node (ref "U5") (pin "1") (pinfunction "OUT_A_1") (pintype "output"))
    )
    (net (code "164") (name "Net-(U4-VREFPS)") (class "Default")
      (node (ref "U4") (pin "3") (pinfunction "VREFPS_3") (pintype "input"))
      (node (ref "U5") (pin "2") (pinfunction "-IN_A_2") (pintype "input"))
    )
    (net (code "165") (name "Net-(U6-VREFNF)") (class "Default")
      (node (ref "U6") (pin "16") (pinfunction "VREFNF_16") (pintype "input"))
      (node (ref "U7") (pin "7") (pinfunction "OUT_B_7") (pintype "output"))
    )
    (net (code "166") (name "Net-(U6-VREFNS)") (class "Default")
      (node (ref "U6") (pin "17") (pinfunction "VREFNS_17") (pintype "input"))
      (node (ref "U7") (pin "6") (pinfunction "-IN_B_6") (pintype "input"))
    )
    (net (code "167") (name "Net-(U6-VREFPF)") (class "Default")
      (node (ref "U6") (pin "4") (pinfunction "VREFPF_4") (pintype "input"))
      (node (ref "U7") (pin "1") (pinfunction "OUT_A_1") (pintype "output"))
    )
    (net (code "168") (name "Net-(U6-VREFPS)") (class "Default")
      (node (ref "U6") (pin "3") (pinfunction "VREFPS_3") (pintype "input"))
      (node (ref "U7") (pin "2") (pinfunction "-IN_A_2") (pintype "input"))
    )
    (net (code "169") (name "Net-(U8-VREFNF)") (class "Default")
      (node (ref "U8") (pin "16") (pinfunction "VREFNF_16") (pintype "input"))
      (node (ref "U9") (pin "7") (pinfunction "OUT_B_7") (pintype "output"))
    )
    (net (code "170") (name "Net-(U8-VREFNS)") (class "Default")
      (node (ref "U8") (pin "17") (pinfunction "VREFNS_17") (pintype "input"))
      (node (ref "U9") (pin "6") (pinfunction "-IN_B_6") (pintype "input"))
    )
    (net (code "171") (name "Net-(U8-VREFPF)") (class "Default")
      (node (ref "U8") (pin "4") (pinfunction "VREFPF_4") (pintype "input"))
      (node (ref "U9") (pin "1") (pinfunction "OUT_A_1") (pintype "output"))
    )
    (net (code "172") (name "Net-(U8-VREFPS)") (class "Default")
      (node (ref "U8") (pin "3") (pinfunction "VREFPS_3") (pintype "input"))
      (node (ref "U9") (pin "2") (pinfunction "-IN_A_2") (pintype "input"))
    )
    (net (code "173") (name "Net-(U10-VREFNF)") (class "Default")
      (node (ref "U10") (pin "16") (pinfunction "VREFNF_16") (pintype "input"))
      (node (ref "U11") (pin "7") (pinfunction "OUT_B_7") (pintype "output"))
    )
    (net (code "174") (name "Net-(U10-VREFNS)") (class "Default")
      (node (ref "U10") (pin "17") (pinfunction "VREFNS_17") (pintype "input"))
      (node (ref "U11") (pin "6") (pinfunction "-IN_B_6") (pintype "input"))
    )
    (net (code "175") (name "Net-(U10-VREFPF)") (class "Default")
      (node (ref "U10") (pin "4") (pinfunction "VREFPF_4") (pintype "input"))
      (node (ref "U11") (pin "1") (pinfunction "OUT_A_1") (pintype "output"))
    )
    (net (code "176") (name "Net-(U10-VREFPS)") (class "Default")
      (node (ref "U10") (pin "3") (pinfunction "VREFPS_3") (pintype "input"))
      (node (ref "U11") (pin "2") (pinfunction "-IN_A_2") (pintype "input"))
    )
    (net (code "177") (name "Net-(U12-VREFNF)") (class "Default")
      (node (ref "U12") (pin "16") (pinfunction "VREFNF_16") (pintype "input"))
      (node (ref "U13") (pin "7") (pinfunction "OUT_B_7") (pintype "output"))
    )
    (net (code "178") (name "Net-(U12-VREFNS)") (class "Default")
      (node (ref "U12") (pin "17") (pinfunction "VREFNS_17") (pintype "input"))
      (node (ref "U13") (pin "6") (pinfunction "-IN_B_6") (pintype "input"))
    )
    (net (code "179") (name "Net-(U12-VREFPF)") (class "Default")
      (node (ref "U12") (pin "4") (pinfunction "VREFPF_4") (pintype "input"))
      (node (ref "U13") (pin "1") (pinfunction "OUT_A_1") (pintype "output"))
    )
    (net (code "180") (name "Net-(U12-VREFPS)") (class "Default")
      (node (ref "U12") (pin "3") (pinfunction "VREFPS_3") (pintype "input"))
      (node (ref "U13") (pin "2") (pinfunction "-IN_A_2") (pintype "input"))
    )
    (net (code "181") (name "Net-(U14-VREFNF)") (class "Default")
      (node (ref "U14") (pin "16") (pinfunction "VREFNF_16") (pintype "input"))
      (node (ref "U15") (pin "7") (pinfunction "OUT_B_7") (pintype "output"))
    )
    (net (code "182") (name "Net-(U14-VREFNS)") (class "Default")
      (node (ref "U14") (pin "17") (pinfunction "VREFNS_17") (pintype "input"))
      (node (ref "U15") (pin "6") (pinfunction "-IN_B_6") (pintype "input"))
    )
    (net (code "183") (name "Net-(U14-VREFPF)") (class "Default")
      (node (ref "U14") (pin "4") (pinfunction "VREFPF_4") (pintype "input"))
      (node (ref "U15") (pin "1") (pinfunction "OUT_A_1") (pintype "output"))
    )
    (net (code "184") (name "Net-(U14-VREFPS)") (class "Default")
      (node (ref "U14") (pin "3") (pinfunction "VREFPS_3") (pintype "input"))
      (node (ref "U15") (pin "2") (pinfunction "-IN_A_2") (pintype "input"))
    )
    (net (code "185") (name "Net-(U16-VREFNF)") (class "Default")
      (node (ref "U16") (pin "16") (pinfunction "VREFNF_16") (pintype "input"))
      (node (ref "U17") (pin "7") (pinfunction "OUT_B_7") (pintype "output"))
    )
    (net (code "186") (name "Net-(U16-VREFNS)") (class "Default")
      (node (ref "U16") (pin "17") (pinfunction "VREFNS_17") (pintype "input"))
      (node (ref "U17") (pin "6") (pinfunction "-IN_B_6") (pintype "input"))
    )
    (net (code "187") (name "Net-(U16-VREFPF)") (class "Default")
      (node (ref "U16") (pin "4") (pinfunction "VREFPF_4") (pintype "input"))
      (node (ref "U17") (pin "1") (pinfunction "OUT_A_1") (pintype "output"))
    )
    (net (code "188") (name "Net-(U16-VREFPS)") (class "Default")
      (node (ref "U16") (pin "3") (pinfunction "VREFPS_3") (pintype "input"))
      (node (ref "U17") (pin "2") (pinfunction "-IN_A_2") (pintype "input"))
    )
    (net (code "189") (name "Net-(U18-VREFNF)") (class "Default")
      (node (ref "U18") (pin "16") (pinfunction "VREFNF_16") (pintype "input"))
      (node (ref "U19") (pin "7") (pinfunction "OUT_B_7") (pintype "output"))
    )
    (net (code "190") (name "Net-(U18-VREFNS)") (class "Default")
      (node (ref "U18") (pin "17") (pinfunction "VREFNS_17") (pintype "input"))
      (node (ref "U19") (pin "6") (pinfunction "-IN_B_6") (pintype "input"))
    )
    (net (code "191") (name "Net-(U18-VREFPF)") (class "Default")
      (node (ref "U18") (pin "4") (pinfunction "VREFPF_4") (pintype "input"))
      (node (ref "U19") (pin "1") (pinfunction "OUT_A_1") (pintype "output"))
    )
    (net (code "192") (name "Net-(U18-VREFPS)") (class "Default")
      (node (ref "U18") (pin "3") (pinfunction "VREFPS_3") (pintype "input"))
      (node (ref "U19") (pin "2") (pinfunction "-IN_A_2") (pintype "input"))
    )
    (net (code "193") (name "Net-(U20-VREFNF)") (class "Default")
      (node (ref "U20") (pin "16") (pinfunction "VREFNF_16") (pintype "input"))
      (node (ref "U21") (pin "7") (pinfunction "OUT_B_7") (pintype "output"))
    )
    (net (code "194") (name "Net-(U20-VREFNS)") (class "Default")
      (node (ref "U20") (pin "17") (pinfunction "VREFNS_17") (pintype "input"))
      (node (ref "U21") (pin "6") (pinfunction "-IN_B_6") (pintype "input"))
    )
    (net (code "195") (name "Net-(U20-VREFPF)") (class "Default")
      (node (ref "U20") (pin "4") (pinfunction "VREFPF_4") (pintype "input"))
      (node (ref "U21") (pin "1") (pinfunction "OUT_A_1") (pintype "output"))
    )
    (net (code "196") (name "Net-(U20-VREFPS)") (class "Default")
      (node (ref "U20") (pin "3") (pinfunction "VREFPS_3") (pintype "input"))
      (node (ref "U21") (pin "2") (pinfunction "-IN_A_2") (pintype "input"))
    )
    (net (code "197") (name "Net-(U22-VREFNF)") (class "Default")
      (node (ref "U22") (pin "16") (pinfunction "VREFNF_16") (pintype "input"))
      (node (ref "U23") (pin "7") (pinfunction "OUT_B_7") (pintype "output"))
    )
    (net (code "198") (name "Net-(U22-VREFNS)") (class "Default")
      (node (ref "U22") (pin "17") (pinfunction "VREFNS_17") (pintype "input"))
      (node (ref "U23") (pin "6") (pinfunction "-IN_B_6") (pintype "input"))
    )
    (net (code "199") (name "Net-(U22-VREFPF)") (class "Default")
      (node (ref "U22") (pin "4") (pinfunction "VREFPF_4") (pintype "input"))
      (node (ref "U23") (pin "1") (pinfunction "OUT_A_1") (pintype "output"))
    )
    (net (code "200") (name "Net-(U22-VREFPS)") (class "Default")
      (node (ref "U22") (pin "3") (pinfunction "VREFPS_3") (pintype "input"))
      (node (ref "U23") (pin "2") (pinfunction "-IN_A_2") (pintype "input"))
    )
    (net (code "201") (name "Net-(U24-VREFNF)") (class "Default")
      (node (ref "U24") (pin "16") (pinfunction "VREFNF_16") (pintype "input"))
      (node (ref "U25") (pin "7") (pinfunction "OUT_B_7") (pintype "output"))
    )
    (net (code "202") (name "Net-(U24-VREFNS)") (class "Default")
      (node (ref "U24") (pin "17") (pinfunction "VREFNS_17") (pintype "input"))
      (node (ref "U25") (pin "6") (pinfunction "-IN_B_6") (pintype "input"))
    )
    (net (code "203") (name "Net-(U24-VREFPF)") (class "Default")
      (node (ref "U24") (pin "4") (pinfunction "VREFPF_4") (pintype "input"))
      (node (ref "U25") (pin "1") (pinfunction "OUT_A_1") (pintype "output"))
    )
    (net (code "204") (name "Net-(U24-VREFPS)") (class "Default")
      (node (ref "U24") (pin "3") (pinfunction "VREFPS_3") (pintype "input"))
      (node (ref "U25") (pin "2") (pinfunction "-IN_A_2") (pintype "input"))
    )
    (net (code "205") (name "Net-(U26-VREFNF)") (class "Default")
      (node (ref "U26") (pin "16") (pinfunction "VREFNF_16") (pintype "input"))
      (node (ref "U27") (pin "7") (pinfunction "OUT_B_7") (pintype "output"))
    )
    (net (code "206") (name "Net-(U26-VREFNS)") (class "Default")
      (node (ref "U26") (pin "17") (pinfunction "VREFNS_17") (pintype "input"))
      (node (ref "U27") (pin "6") (pinfunction "-IN_B_6") (pintype "input"))
    )
    (net (code "207") (name "Net-(U26-VREFPF)") (class "Default")
      (node (ref "U26") (pin "4") (pinfunction "VREFPF_4") (pintype "input"))
      (node (ref "U27") (pin "1") (pinfunction "OUT_A_1") (pintype "output"))
    )
    (net (code "208") (name "Net-(U26-VREFPS)") (class "Default")
      (node (ref "U26") (pin "3") (pinfunction "VREFPS_3") (pintype "input"))
      (node (ref "U27") (pin "2") (pinfunction "-IN_A_2") (pintype "input"))
    )
    (net (code "209") (name "Net-(U30-OUTA)") (class "Default")
      (node (ref "R18") (pin "1") (pinfunction "1_1") (pintype "passive"))
      (node (ref "U30") (pin "1") (pinfunction "OUTA_1") (pintype "output"))
    )
    (net (code "210") (name "Net-(U30-OUTB)") (class "Default")
      (node (ref "R20") (pin "1") (pinfunction "1_1") (pintype "passive"))
      (node (ref "U30") (pin "7") (pinfunction "OUTB_7") (pintype "output"))
    )
    (net (code "211") (name "Net-(U31-OUTA)") (class "Default")
      (node (ref "R22") (pin "1") (pinfunction "1_1") (pintype "passive"))
      (node (ref "U31") (pin "1") (pinfunction "OUTA_1") (pintype "output"))
    )
    (net (code "212") (name "Net-(U31-OUTB)") (class "Default")
      (node (ref "R23") (pin "1") (pinfunction "1_1") (pintype "passive"))
      (node (ref "U31") (pin "7") (pinfunction "OUTB_7") (pintype "output"))
    )
    (net (code "213") (name "Net-(U32-OUTA)") (class "Default")
      (node (ref "R26") (pin "1") (pinfunction "1_1") (pintype "passive"))
      (node (ref "U32") (pin "1") (pinfunction "OUTA_1") (pintype "output"))
    )
    (net (code "214") (name "Net-(U32-OUTB)") (class "Default")
      (node (ref "R27") (pin "1") (pinfunction "1_1") (pintype "passive"))
      (node (ref "U32") (pin "7") (pinfunction "OUTB_7") (pintype "output"))
    )
    (net (code "215") (name "OUT0") (class "Default")
      (node (ref "ISO9") (pin "3") (pinfunction "A1_3") (pintype "bidirectional"))
    )
    (net (code "216") (name "OUT1") (class "Default")
      (node (ref "ISO9") (pin "4") (pinfunction "A2_4") (pintype "bidirectional"))
    )
    (net (code "217") (name "OUT2") (class "Default")
      (node (ref "ISO9") (pin "5") (pinfunction "A3_5") (pintype "bidirectional"))
    )
    (net (code "218") (name "OUT3") (class "Default")
      (node (ref "ISO9") (pin "6") (pinfunction "A4_6") (pintype "bidirectional"))
    )
    (net (code "219") (name "OUT4") (class "Default")
      (node (ref "ISO9") (pin "7") (pinfunction "A5_7") (pintype "bidirectional"))
    )
    (net (code "220") (name "OUT5") (class "Default")
      (node (ref "ISO10") (pin "3") (pinfunction "A1_3") (pintype "bidirectional"))
    )
    (net (code "221") (name "OUT6") (class "Default")
      (node (ref "ISO10") (pin "4") (pinfunction "A2_4") (pintype "bidirectional"))
    )
    (net (code "222") (name "OUT7") (class "Default")
      (node (ref "ISO10") (pin "5") (pinfunction "A3_5") (pintype "bidirectional"))
    )
    (net (code "223") (name "OUTCLK-IN") (class "Default")
      (node (ref "ISO1") (pin "10") (pinfunction "B5_10") (pintype "bidirectional"))
    )
    (net (code "224") (name "OUTCLK-OUT") (class "Default")
      (node (ref "ISO10") (pin "6") (pinfunction "A4_6") (pintype "bidirectional"))
    )
    (net (code "225") (name "RFB_1") (class "Default")
      (node (ref "C34") (pin "2") (pinfunction "2_2") (pintype "passive"))
      (node (ref "R20") (pin "2") (pinfunction "2_2") (pintype "passive"))
      (node (ref "R5") (pin "1") (pinfunction "1_1") (pintype "passive"))
      (node (ref "U4") (pin "20") (pinfunction "RFB_20") (pintype "input"))
    )
    (net (code "226") (name "RFB_2") (class "Default")
      (node (ref "C46") (pin "2") (pinfunction "2_2") (pintype "passive"))
      (node (ref "R23") (pin "2") (pinfunction "2_2") (pintype "passive"))
      (node (ref "R9") (pin "1") (pinfunction "1_1") (pintype "passive"))
      (node (ref "U6") (pin "20") (pinfunction "RFB_20") (pintype "input"))
    )
    (net (code "227") (name "RFB_3") (class "Default")
      (node (ref "C58") (pin "2") (pinfunction "2_2") (pintype "passive"))
      (node (ref "R11") (pin "1") (pinfunction "1_1") (pintype "passive"))
      (node (ref "R27") (pin "2") (pinfunction "2_2") (pintype "passive"))
      (node (ref "U8") (pin "20") (pinfunction "RFB_20") (pintype "input"))
    )
    (net (code "228") (name "RFB_4") (class "Default")
      (node (ref "C70") (pin "2") (pinfunction "2_2") (pintype "passive"))
      (node (ref "R13") (pin "1") (pinfunction "1_1") (pintype "passive"))
      (node (ref "U10") (pin "20") (pinfunction "RFB_20") (pintype "input"))
      (node (ref "U33") (pin "7") (pinfunction "OUTB_7") (pintype "output"))
    )
    (net (code "229") (name "RFB_5") (class "Default")
      (node (ref "C82") (pin "2") (pinfunction "2_2") (pintype "passive"))
      (node (ref "R15") (pin "1") (pinfunction "1_1") (pintype "passive"))
      (node (ref "U12") (pin "20") (pinfunction "RFB_20") (pintype "input"))
      (node (ref "U34") (pin "7") (pinfunction "OUTB_7") (pintype "output"))
    )
    (net (code "230") (name "RFB_6") (class "Default")
      (node (ref "C94") (pin "2") (pinfunction "2_2") (pintype "passive"))
      (node (ref "R17") (pin "1") (pinfunction "1_1") (pintype "passive"))
      (node (ref "U14") (pin "20") (pinfunction "RFB_20") (pintype "input"))
      (node (ref "U35") (pin "7") (pinfunction "OUTB_7") (pintype "output"))
    )
    (net (code "231") (name "RFB_7") (class "Default")
      (node (ref "C106") (pin "2") (pinfunction "2_2") (pintype "passive"))
      (node (ref "R18") (pin "2") (pinfunction "2_2") (pintype "passive"))
      (node (ref "R4") (pin "1") (pinfunction "1_1") (pintype "passive"))
      (node (ref "U16") (pin "20") (pinfunction "RFB_20") (pintype "input"))
    )
    (net (code "232") (name "RFB_8") (class "Default")
      (node (ref "C118") (pin "2") (pinfunction "2_2") (pintype "passive"))
      (node (ref "R22") (pin "2") (pinfunction "2_2") (pintype "passive"))
      (node (ref "R8") (pin "1") (pinfunction "1_1") (pintype "passive"))
      (node (ref "U18") (pin "20") (pinfunction "RFB_20") (pintype "input"))
    )
    (net (code "233") (name "RFB_9") (class "Default")
      (node (ref "C130") (pin "2") (pinfunction "2_2") (pintype "passive"))
      (node (ref "R10") (pin "1") (pinfunction "1_1") (pintype "passive"))
      (node (ref "R26") (pin "2") (pinfunction "2_2") (pintype "passive"))
      (node (ref "U20") (pin "20") (pinfunction "RFB_20") (pintype "input"))
    )
    (net (code "234") (name "RFB_10") (class "Default")
      (node (ref "C142") (pin "2") (pinfunction "2_2") (pintype "passive"))
      (node (ref "R12") (pin "1") (pinfunction "1_1") (pintype "passive"))
      (node (ref "U22") (pin "20") (pinfunction "RFB_20") (pintype "input"))
      (node (ref "U33") (pin "1") (pinfunction "OUTA_1") (pintype "output"))
    )
    (net (code "235") (name "RFB_11") (class "Default")
      (node (ref "C154") (pin "2") (pinfunction "2_2") (pintype "passive"))
      (node (ref "R14") (pin "1") (pinfunction "1_1") (pintype "passive"))
      (node (ref "U24") (pin "20") (pinfunction "RFB_20") (pintype "input"))
      (node (ref "U34") (pin "1") (pinfunction "OUTA_1") (pintype "output"))
    )
    (net (code "236") (name "RFB_12") (class "Default")
      (node (ref "C166") (pin "2") (pinfunction "2_2") (pintype "passive"))
      (node (ref "R16") (pin "1") (pinfunction "1_1") (pintype "passive"))
      (node (ref "U26") (pin "20") (pinfunction "RFB_20") (pintype "input"))
      (node (ref "U35") (pin "1") (pinfunction "OUTA_1") (pintype "output"))
    )
    (net (code "237") (name "SCLK_1") (class "Default")
      (node (ref "ISO8") (pin "12") (pinfunction "B3_12") (pintype "bidirectional"))
      (node (ref "U4") (pin "13") (pinfunction "SCLK_13") (pintype "input"))
    )
    (net (code "238") (name "SCLK_2") (class "Default")
      (node (ref "ISO7") (pin "14") (pinfunction "B1_14") (pintype "bidirectional"))
      (node (ref "U6") (pin "13") (pinfunction "SCLK_13") (pintype "input"))
    )
    (net (code "239") (name "SCLK_3") (class "Default")
      (node (ref "ISO7") (pin "11") (pinfunction "B4_11") (pintype "bidirectional"))
      (node (ref "U8") (pin "13") (pinfunction "SCLK_13") (pintype "input"))
    )
    (net (code "240") (name "SCLK_4") (class "Default")
      (node (ref "ISO6") (pin "13") (pinfunction "B2_13") (pintype "bidirectional"))
      (node (ref "U10") (pin "13") (pinfunction "SCLK_13") (pintype "input"))
    )
    (net (code "241") (name "SCLK_5") (class "Default")
      (node (ref "ISO6") (pin "10") (pinfunction "B5_10") (pintype "bidirectional"))
      (node (ref "U12") (pin "13") (pinfunction "SCLK_13") (pintype "input"))
    )
    (net (code "242") (name "SCLK_6") (class "Default")
      (node (ref "ISO5") (pin "12") (pinfunction "B3_12") (pintype "bidirectional"))
      (node (ref "U14") (pin "13") (pinfunction "SCLK_13") (pintype "input"))
    )
    (net (code "243") (name "SCLK_7") (class "Default")
      (node (ref "ISO4") (pin "11") (pinfunction "B4_11") (pintype "bidirectional"))
      (node (ref "U16") (pin "13") (pinfunction "SCLK_13") (pintype "input"))
    )
    (net (code "244") (name "SCLK_8") (class "Default")
      (node (ref "ISO4") (pin "14") (pinfunction "B1_14") (pintype "bidirectional"))
      (node (ref "U18") (pin "13") (pinfunction "SCLK_13") (pintype "input"))
    )
    (net (code "245") (name "SCLK_9") (class "Default")
      (node (ref "ISO3") (pin "13") (pinfunction "B2_13") (pintype "bidirectional"))
      (node (ref "U20") (pin "13") (pinfunction "SCLK_13") (pintype "input"))
    )
    (net (code "246") (name "SCLK_10") (class "Default")
      (node (ref "ISO3") (pin "10") (pinfunction "B5_10") (pintype "bidirectional"))
      (node (ref "U22") (pin "13") (pinfunction "SCLK_13") (pintype "input"))
    )
    (net (code "247") (name "SCLK_11") (class "Default")
      (node (ref "ISO2") (pin "12") (pinfunction "B3_12") (pintype "bidirectional"))
      (node (ref "U24") (pin "13") (pinfunction "SCLK_13") (pintype "input"))
    )
    (net (code "248") (name "SCLK_12") (class "Default")
      (node (ref "ISO1") (pin "14") (pinfunction "B1_14") (pintype "bidirectional"))
      (node (ref "U26") (pin "13") (pinfunction "SCLK_13") (pintype "input"))
    )
    (net (code "249") (name "SDIN_1") (class "Default")
      (node (ref "ISO8") (pin "13") (pinfunction "B2_13") (pintype "bidirectional"))
      (node (ref "U4") (pin "12") (pinfunction "SDIN_12") (pintype "input"))
    )
    (net (code "250") (name "SDIN_2") (class "Default")
      (node (ref "ISO8") (pin "10") (pinfunction "B5_10") (pintype "bidirectional"))
      (node (ref "U6") (pin "12") (pinfunction "SDIN_12") (pintype "input"))
    )
    (net (code "251") (name "SDIN_3") (class "Default")
      (node (ref "ISO7") (pin "12") (pinfunction "B3_12") (pintype "bidirectional"))
      (node (ref "U8") (pin "12") (pinfunction "SDIN_12") (pintype "input"))
    )
    (net (code "252") (name "SDIN_4") (class "Default")
      (node (ref "ISO6") (pin "14") (pinfunction "B1_14") (pintype "bidirectional"))
      (node (ref "U10") (pin "12") (pinfunction "SDIN_12") (pintype "input"))
    )
    (net (code "253") (name "SDIN_5") (class "Default")
      (node (ref "ISO6") (pin "11") (pinfunction "B4_11") (pintype "bidirectional"))
      (node (ref "U12") (pin "12") (pinfunction "SDIN_12") (pintype "input"))
    )
    (net (code "254") (name "SDIN_6") (class "Default")
      (node (ref "ISO5") (pin "13") (pinfunction "B2_13") (pintype "bidirectional"))
      (node (ref "U14") (pin "12") (pinfunction "SDIN_12") (pintype "input"))
    )
    (net (code "255") (name "SDIN_7") (class "Default")
      (node (ref "ISO4") (pin "12") (pinfunction "B3_12") (pintype "bidirectional"))
      (node (ref "U16") (pin "12") (pinfunction "SDIN_12") (pintype "input"))
    )
    (net (code "256") (name "SDIN_8") (class "Default")
      (node (ref "ISO5") (pin "10") (pinfunction "B5_10") (pintype "bidirectional"))
      (node (ref "U18") (pin "12") (pinfunction "SDIN_12") (pintype "input"))
    )
    (net (code "257") (name "SDIN_9") (class "Default")
      (node (ref "ISO3") (pin "14") (pinfunction "B1_14") (pintype "bidirectional"))
      (node (ref "U20") (pin "12") (pinfunction "SDIN_12") (pintype "input"))
    )
    (net (code "258") (name "SDIN_10") (class "Default")
      (node (ref "ISO3") (pin "11") (pinfunction "B4_11") (pintype "bidirectional"))
      (node (ref "U22") (pin "12") (pinfunction "SDIN_12") (pintype "input"))
    )
    (net (code "259") (name "SDIN_11") (class "Default")
      (node (ref "ISO2") (pin "13") (pinfunction "B2_13") (pintype "bidirectional"))
      (node (ref "U24") (pin "12") (pinfunction "SDIN_12") (pintype "input"))
    )
    (net (code "260") (name "SDIN_12") (class "Default")
      (node (ref "ISO2") (pin "10") (pinfunction "B5_10") (pintype "bidirectional"))
      (node (ref "U26") (pin "12") (pinfunction "SDIN_12") (pintype "input"))
    )
    (net (code "261") (name "SDO_1") (class "Default")
      (node (ref "U4") (pin "11") (pinfunction "SDO_11") (pintype "output"))
    )
    (net (code "262") (name "SDO_2") (class "Default")
      (node (ref "U6") (pin "11") (pinfunction "SDO_11") (pintype "output"))
    )
    (net (code "263") (name "SDO_3") (class "Default")
      (node (ref "U8") (pin "11") (pinfunction "SDO_11") (pintype "output"))
    )
    (net (code "264") (name "SDO_4") (class "Default")
      (node (ref "U10") (pin "11") (pinfunction "SDO_11") (pintype "output"))
    )
    (net (code "265") (name "SDO_5") (class "Default")
      (node (ref "U12") (pin "11") (pinfunction "SDO_11") (pintype "output"))
    )
    (net (code "266") (name "SDO_6") (class "Default")
      (node (ref "U14") (pin "11") (pinfunction "SDO_11") (pintype "output"))
    )
    (net (code "267") (name "SDO_7") (class "Default")
      (node (ref "U16") (pin "11") (pinfunction "SDO_11") (pintype "output"))
    )
    (net (code "268") (name "SDO_8") (class "Default")
      (node (ref "U18") (pin "11") (pinfunction "SDO_11") (pintype "output"))
    )
    (net (code "269") (name "SDO_9") (class "Default")
      (node (ref "U20") (pin "11") (pinfunction "SDO_11") (pintype "output"))
    )
    (net (code "270") (name "SDO_10") (class "Default")
      (node (ref "U22") (pin "11") (pinfunction "SDO_11") (pintype "output"))
    )
    (net (code "271") (name "SDO_11") (class "Default")
      (node (ref "U24") (pin "11") (pinfunction "SDO_11") (pintype "output"))
    )
    (net (code "272") (name "SDO_12") (class "Default")
      (node (ref "U26") (pin "11") (pinfunction "SDO_11") (pintype "output"))
    )
    (net (code "273") (name "SYNCLK") (class "Default")
      (node (ref "J1") (pin "A24") (pinfunction "A24_A24") (pintype "passive"))
    )
    (net (code "274") (name "SYNC_1") (class "Default")
      (node (ref "ISO8") (pin "11") (pinfunction "B4_11") (pintype "bidirectional"))
      (node (ref "U4") (pin "14") (pinfunction "~{SYNC}_14") (pintype "input"))
    )
    (net (code "275") (name "SYNC_2") (class "Default")
      (node (ref "ISO7") (pin "13") (pinfunction "B2_13") (pintype "bidirectional"))
      (node (ref "U6") (pin "14") (pinfunction "~{SYNC}_14") (pintype "input"))
    )
    (net (code "276") (name "SYNC_3") (class "Default")
      (node (ref "ISO7") (pin "10") (pinfunction "B5_10") (pintype "bidirectional"))
      (node (ref "U8") (pin "14") (pinfunction "~{SYNC}_14") (pintype "input"))
    )
    (net (code "277") (name "SYNC_4") (class "Default")
      (node (ref "ISO6") (pin "12") (pinfunction "B3_12") (pintype "bidirectional"))
      (node (ref "U10") (pin "14") (pinfunction "~{SYNC}_14") (pintype "input"))
    )
    (net (code "278") (name "SYNC_5") (class "Default")
      (node (ref "ISO5") (pin "14") (pinfunction "B1_14") (pintype "bidirectional"))
      (node (ref "U12") (pin "14") (pinfunction "~{SYNC}_14") (pintype "input"))
    )
    (net (code "279") (name "SYNC_6") (class "Default")
      (node (ref "ISO5") (pin "11") (pinfunction "B4_11") (pintype "bidirectional"))
      (node (ref "U14") (pin "14") (pinfunction "~{SYNC}_14") (pintype "input"))
    )
    (net (code "280") (name "SYNC_7") (class "Default")
      (node (ref "ISO4") (pin "10") (pinfunction "B5_10") (pintype "bidirectional"))
      (node (ref "U16") (pin "14") (pinfunction "~{SYNC}_14") (pintype "input"))
    )
    (net (code "281") (name "SYNC_8") (class "Default")
      (node (ref "ISO4") (pin "13") (pinfunction "B2_13") (pintype "bidirectional"))
      (node (ref "U18") (pin "14") (pinfunction "~{SYNC}_14") (pintype "input"))
    )
    (net (code "282") (name "SYNC_9") (class "Default")
      (node (ref "ISO3") (pin "12") (pinfunction "B3_12") (pintype "bidirectional"))
      (node (ref "U20") (pin "14") (pinfunction "~{SYNC}_14") (pintype "input"))
    )
    (net (code "283") (name "SYNC_10") (class "Default")
      (node (ref "ISO2") (pin "14") (pinfunction "B1_14") (pintype "bidirectional"))
      (node (ref "U22") (pin "14") (pinfunction "~{SYNC}_14") (pintype "input"))
    )
    (net (code "284") (name "SYNC_11") (class "Default")
      (node (ref "ISO2") (pin "11") (pinfunction "B4_11") (pintype "bidirectional"))
      (node (ref "U24") (pin "14") (pinfunction "~{SYNC}_14") (pintype "input"))
    )
    (net (code "285") (name "SYNC_12") (class "Default")
      (node (ref "ISO1") (pin "13") (pinfunction "B2_13") (pintype "bidirectional"))
      (node (ref "U26") (pin "14") (pinfunction "~{SYNC}_14") (pintype "input"))
    )
    (net (code "286") (name "SYSCLK") (class "Default")
      (node (ref "J1") (pin "B23") (pinfunction "B23_B23") (pintype "passive"))
    )
    (net (code "287") (name "VOUT_1") (class "Default")
      (node (ref "R5") (pin "2") (pinfunction "2_2") (pintype "passive"))
      (node (ref "X1") (pin "8") (pinfunction "8_8") (pintype "passive"))
    )
    (net (code "288") (name "VOUT_2") (class "Default")
      (node (ref "R9") (pin "2") (pinfunction "2_2") (pintype "passive"))
      (node (ref "X1") (pin "41") (pinfunction "41_41") (pintype "passive"))
    )
    (net (code "289") (name "VOUT_3") (class "Default")
      (node (ref "R11") (pin "2") (pinfunction "2_2") (pintype "passive"))
      (node (ref "X1") (pin "6") (pinfunction "6_6") (pintype "passive"))
    )
    (net (code "290") (name "VOUT_4") (class "Default")
      (node (ref "R13") (pin "2") (pinfunction "2_2") (pintype "passive"))
      (node (ref "X1") (pin "39") (pinfunction "39_39") (pintype "passive"))
    )
    (net (code "291") (name "VOUT_5") (class "Default")
      (node (ref "R15") (pin "2") (pinfunction "2_2") (pintype "passive"))
      (node (ref "X1") (pin "37") (pinfunction "37_37") (pintype "passive"))
    )
    (net (code "292") (name "VOUT_6") (class "Default")
      (node (ref "R17") (pin "2") (pinfunction "2_2") (pintype "passive"))
      (node (ref "X1") (pin "4") (pinfunction "4_4") (pintype "passive"))
    )
    (net (code "293") (name "VOUT_7") (class "Default")
      (node (ref "R4") (pin "2") (pinfunction "2_2") (pintype "passive"))
      (node (ref "X1") (pin "14") (pinfunction "14_14") (pintype "passive"))
    )
    (net (code "294") (name "VOUT_8") (class "Default")
      (node (ref "R8") (pin "2") (pinfunction "2_2") (pintype "passive"))
      (node (ref "X1") (pin "47") (pinfunction "47_47") (pintype "passive"))
    )
    (net (code "295") (name "VOUT_9") (class "Default")
      (node (ref "R10") (pin "2") (pinfunction "2_2") (pintype "passive"))
      (node (ref "X1") (pin "45") (pinfunction "45_45") (pintype "passive"))
    )
    (net (code "296") (name "VOUT_10") (class "Default")
      (node (ref "R12") (pin "2") (pinfunction "2_2") (pintype "passive"))
      (node (ref "X1") (pin "12") (pinfunction "12_12") (pintype "passive"))
    )
    (net (code "297") (name "VOUT_11") (class "Default")
      (node (ref "R14") (pin "2") (pinfunction "2_2") (pintype "passive"))
      (node (ref "X1") (pin "43") (pinfunction "43_43") (pintype "passive"))
    )
    (net (code "298") (name "VOUT_12") (class "Default")
      (node (ref "R16") (pin "2") (pinfunction "2_2") (pintype "passive"))
      (node (ref "X1") (pin "10") (pinfunction "10_10") (pintype "passive"))
    )
    (net (code "299") (name "VREF") (class "Default")
      (node (ref "C23") (pin "1") (pinfunction "1_1") (pintype "passive"))
      (node (ref "C24") (pin "1") (pinfunction "1_1") (pintype "passive"))
      (node (ref "C25") (pin "1") (pinfunction "1_1") (pintype "passive"))
      (node (ref "R6") (pin "1") (pinfunction "1_1") (pintype "passive"))
      (node (ref "R7") (pin "2") (pinfunction "2_2") (pintype "passive"))
      (node (ref "U1") (pin "12") (pinfunction "VREF_12") (pintype "bidirectional"))
      (node (ref "U2") (pin "35") (pinfunction "VREF_35") (pintype "bidirectional"))
      (node (ref "U3") (pin "35") (pinfunction "VREF_35") (pintype "bidirectional"))
      (node (ref "U40") (pin "41") (pinfunction "VREF_41") (pintype "bidirectional"))
    )
    (net (code "300") (name "unconnected-(ISO9-GND1-Pad2)") (class "Default")
      (node (ref "ISO9") (pin "2") (pinfunction "GND1_2") (pintype "bidirectional"))
    )
    (net (code "301") (name "unconnected-(ISO9-GND1-Pad8)") (class "Default")
      (node (ref "ISO9") (pin "8") (pinfunction "GND1_8") (pintype "bidirectional"))
    )
    (net (code "302") (name "unconnected-(ISO9-VDD1-Pad1)") (class "Default")
      (node (ref "ISO9") (pin "1") (pinfunction "VDD1_1") (pintype "bidirectional"))
    )
    (net (code "303") (name "unconnected-(ISO10-A5-Pad7)") (class "Default")
      (node (ref "ISO10") (pin "7") (pinfunction "A5_7") (pintype "bidirectional"))
    )
    (net (code "304") (name "unconnected-(ISO10-B5-Pad10)") (class "Default")
      (node (ref "ISO10") (pin "10") (pinfunction "B5_10") (pintype "bidirectional"))
    )
    (net (code "305") (name "unconnected-(ISO10-GND1-Pad2)") (class "Default")
      (node (ref "ISO10") (pin "2") (pinfunction "GND1_2") (pintype "bidirectional"))
    )
    (net (code "306") (name "unconnected-(ISO10-GND1-Pad8)") (class "Default")
      (node (ref "ISO10") (pin "8") (pinfunction "GND1_8") (pintype "bidirectional"))
    )
    (net (code "307") (name "unconnected-(ISO10-VDD1-Pad1)") (class "Default")
      (node (ref "ISO10") (pin "1") (pinfunction "VDD1_1") (pintype "bidirectional"))
    )
    (net (code "308") (name "unconnected-(J1-PadB30)") (class "Default")
      (node (ref "J1") (pin "B30") (pinfunction "B30_B30") (pintype "passive"))
    )
    (net (code "309") (name "unconnected-(J1-PadB32)") (class "Default")
      (node (ref "J1") (pin "B32") (pinfunction "B32_B32") (pintype "passive"))
    )
    (net (code "310") (name "unconnected-(J1-PadB39)") (class "Default")
      (node (ref "J1") (pin "B39") (pinfunction "B39_B39") (pintype "passive"))
    )
    (net (code "311") (name "unconnected-(J1-PadC30)") (class "Default")
      (node (ref "J1") (pin "C30") (pinfunction "C30_C30") (pintype "passive"))
    )
    (net (code "312") (name "unconnected-(J1-PadD30)") (class "Default")
      (node (ref "J1") (pin "D30") (pinfunction "D30_D30") (pintype "passive"))
    )
    (net (code "313") (name "unconnected-(J1-PadD32)") (class "Default")
      (node (ref "J1") (pin "D32") (pinfunction "D32_D32") (pintype "passive"))
    )
    (net (code "314") (name "unconnected-(J1-PadD39)") (class "Default")
      (node (ref "J1") (pin "D39") (pinfunction "D39_D39") (pintype "passive"))
    )
    (net (code "315") (name "unconnected-(U1-2Y-Pad3)") (class "Default")
      (node (ref "U1") (pin "3") (pinfunction "2Y_3") (pintype "bidirectional"))
    )
    (net (code "316") (name "unconnected-(X1-PadG1)") (class "Default")
      (node (ref "X1") (pin "G1") (pinfunction "G1_G1") (pintype "passive"))
    )
    (net (code "317") (name "unconnected-(X1-PadG2)") (class "Default")
      (node (ref "X1") (pin "G2") (pinfunction "G2_G2") (pintype "passive"))
    )
  )
)
